# oresat-backplane-2u.net
KiCad netlist of a schematic drawn in EAGLE
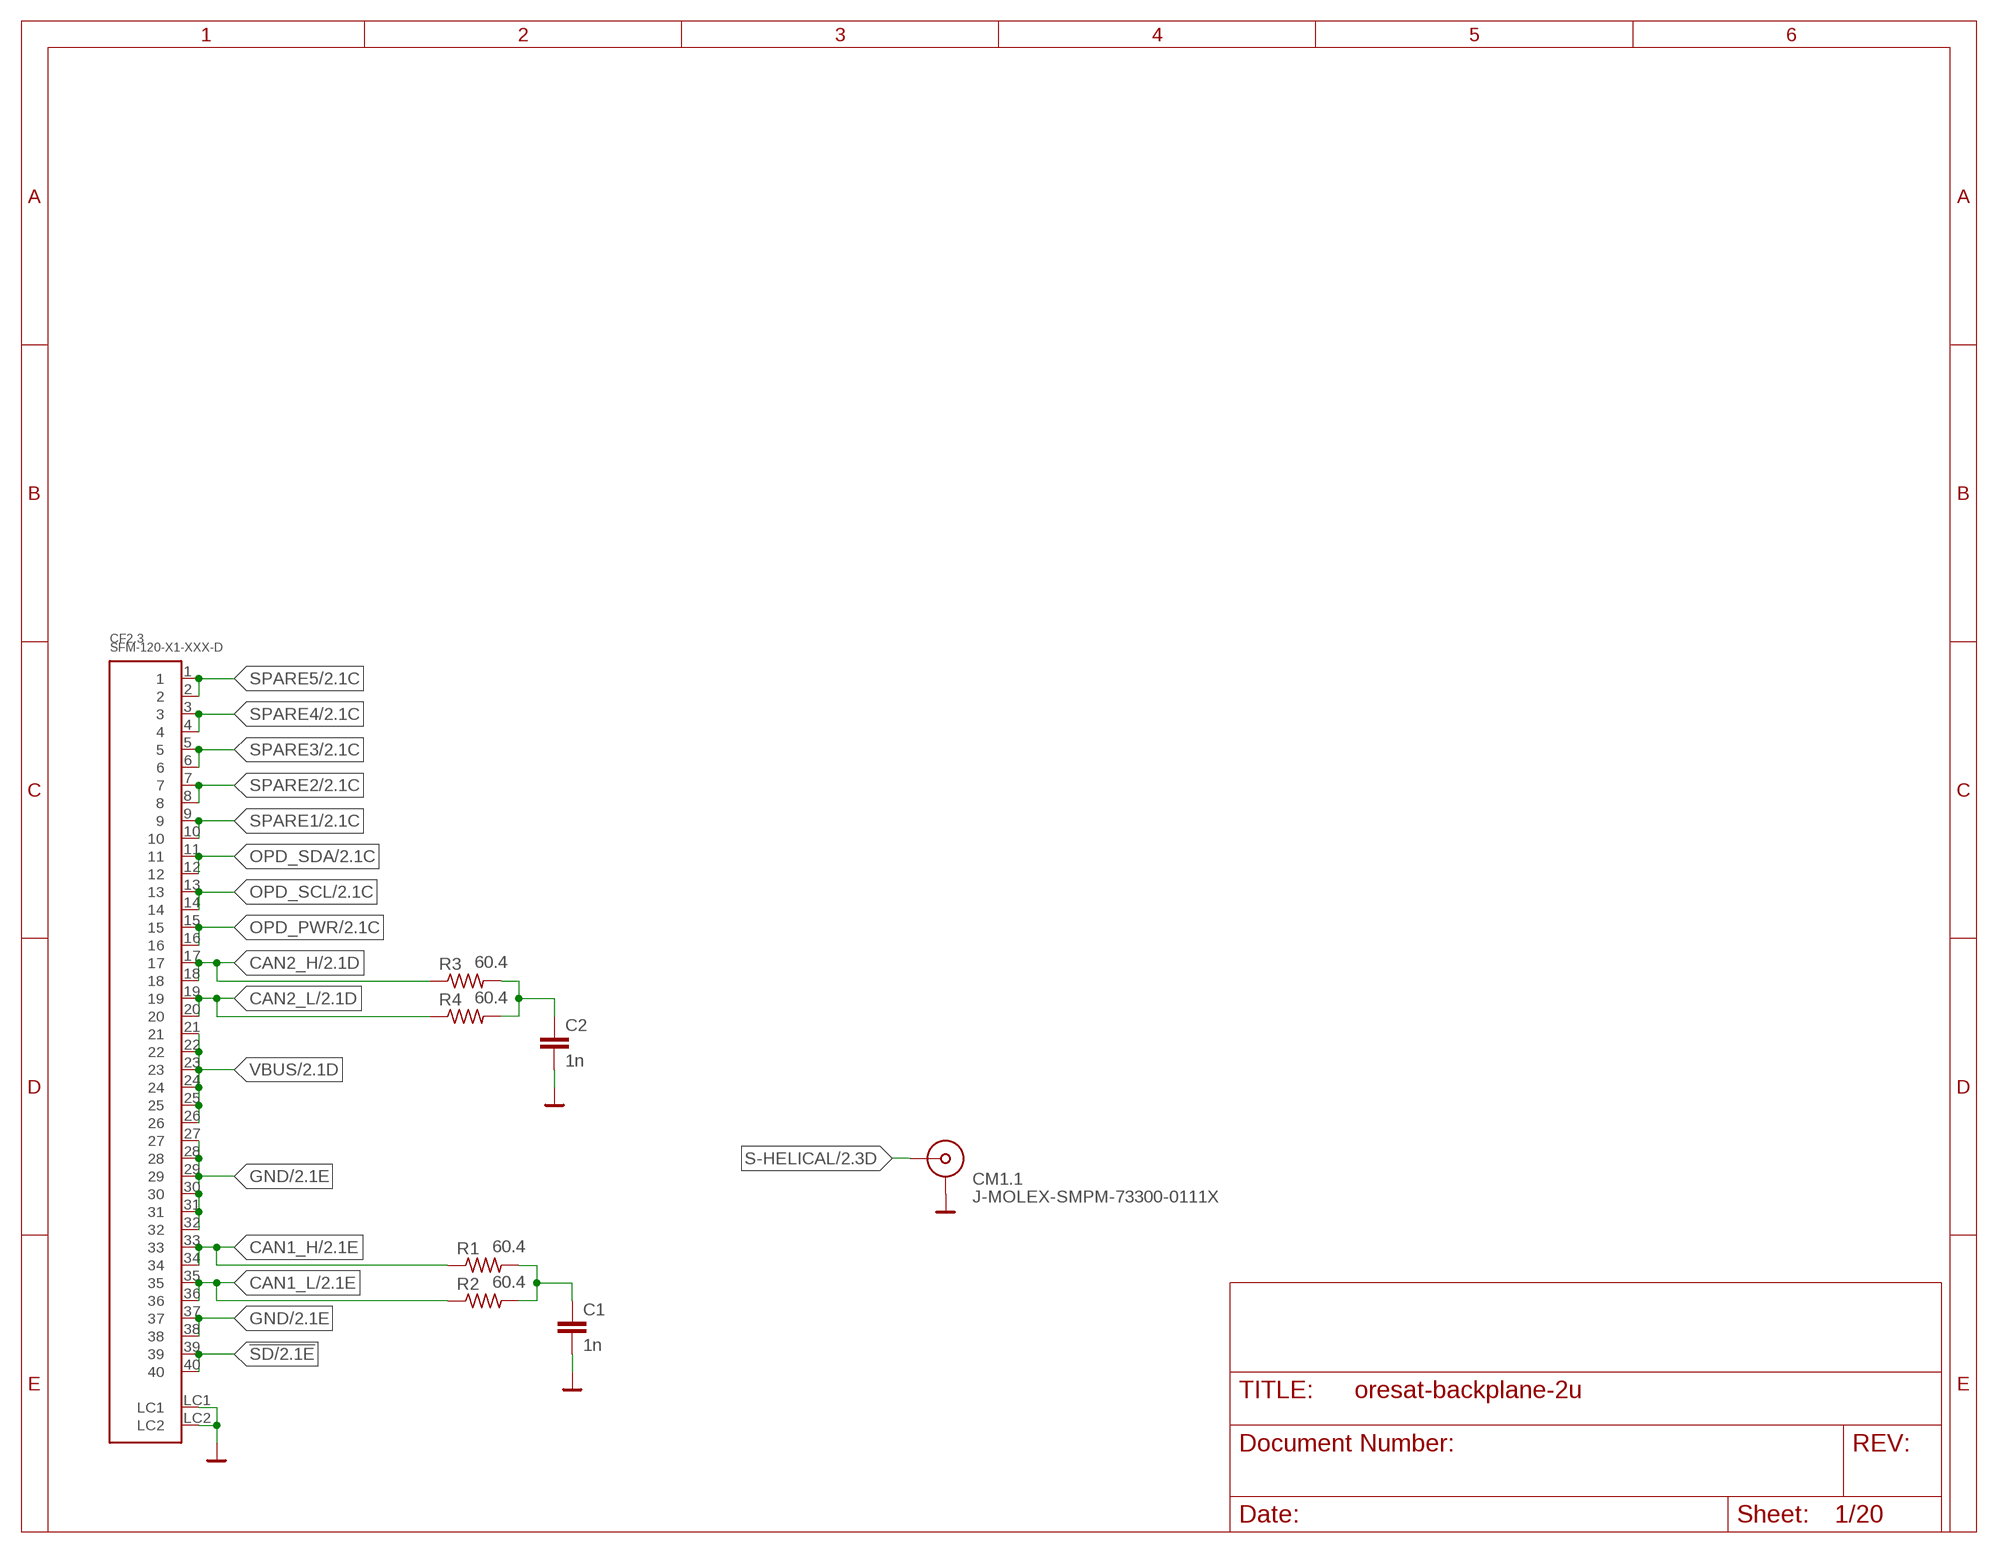
[diagram p0: schematic, sheet 1]
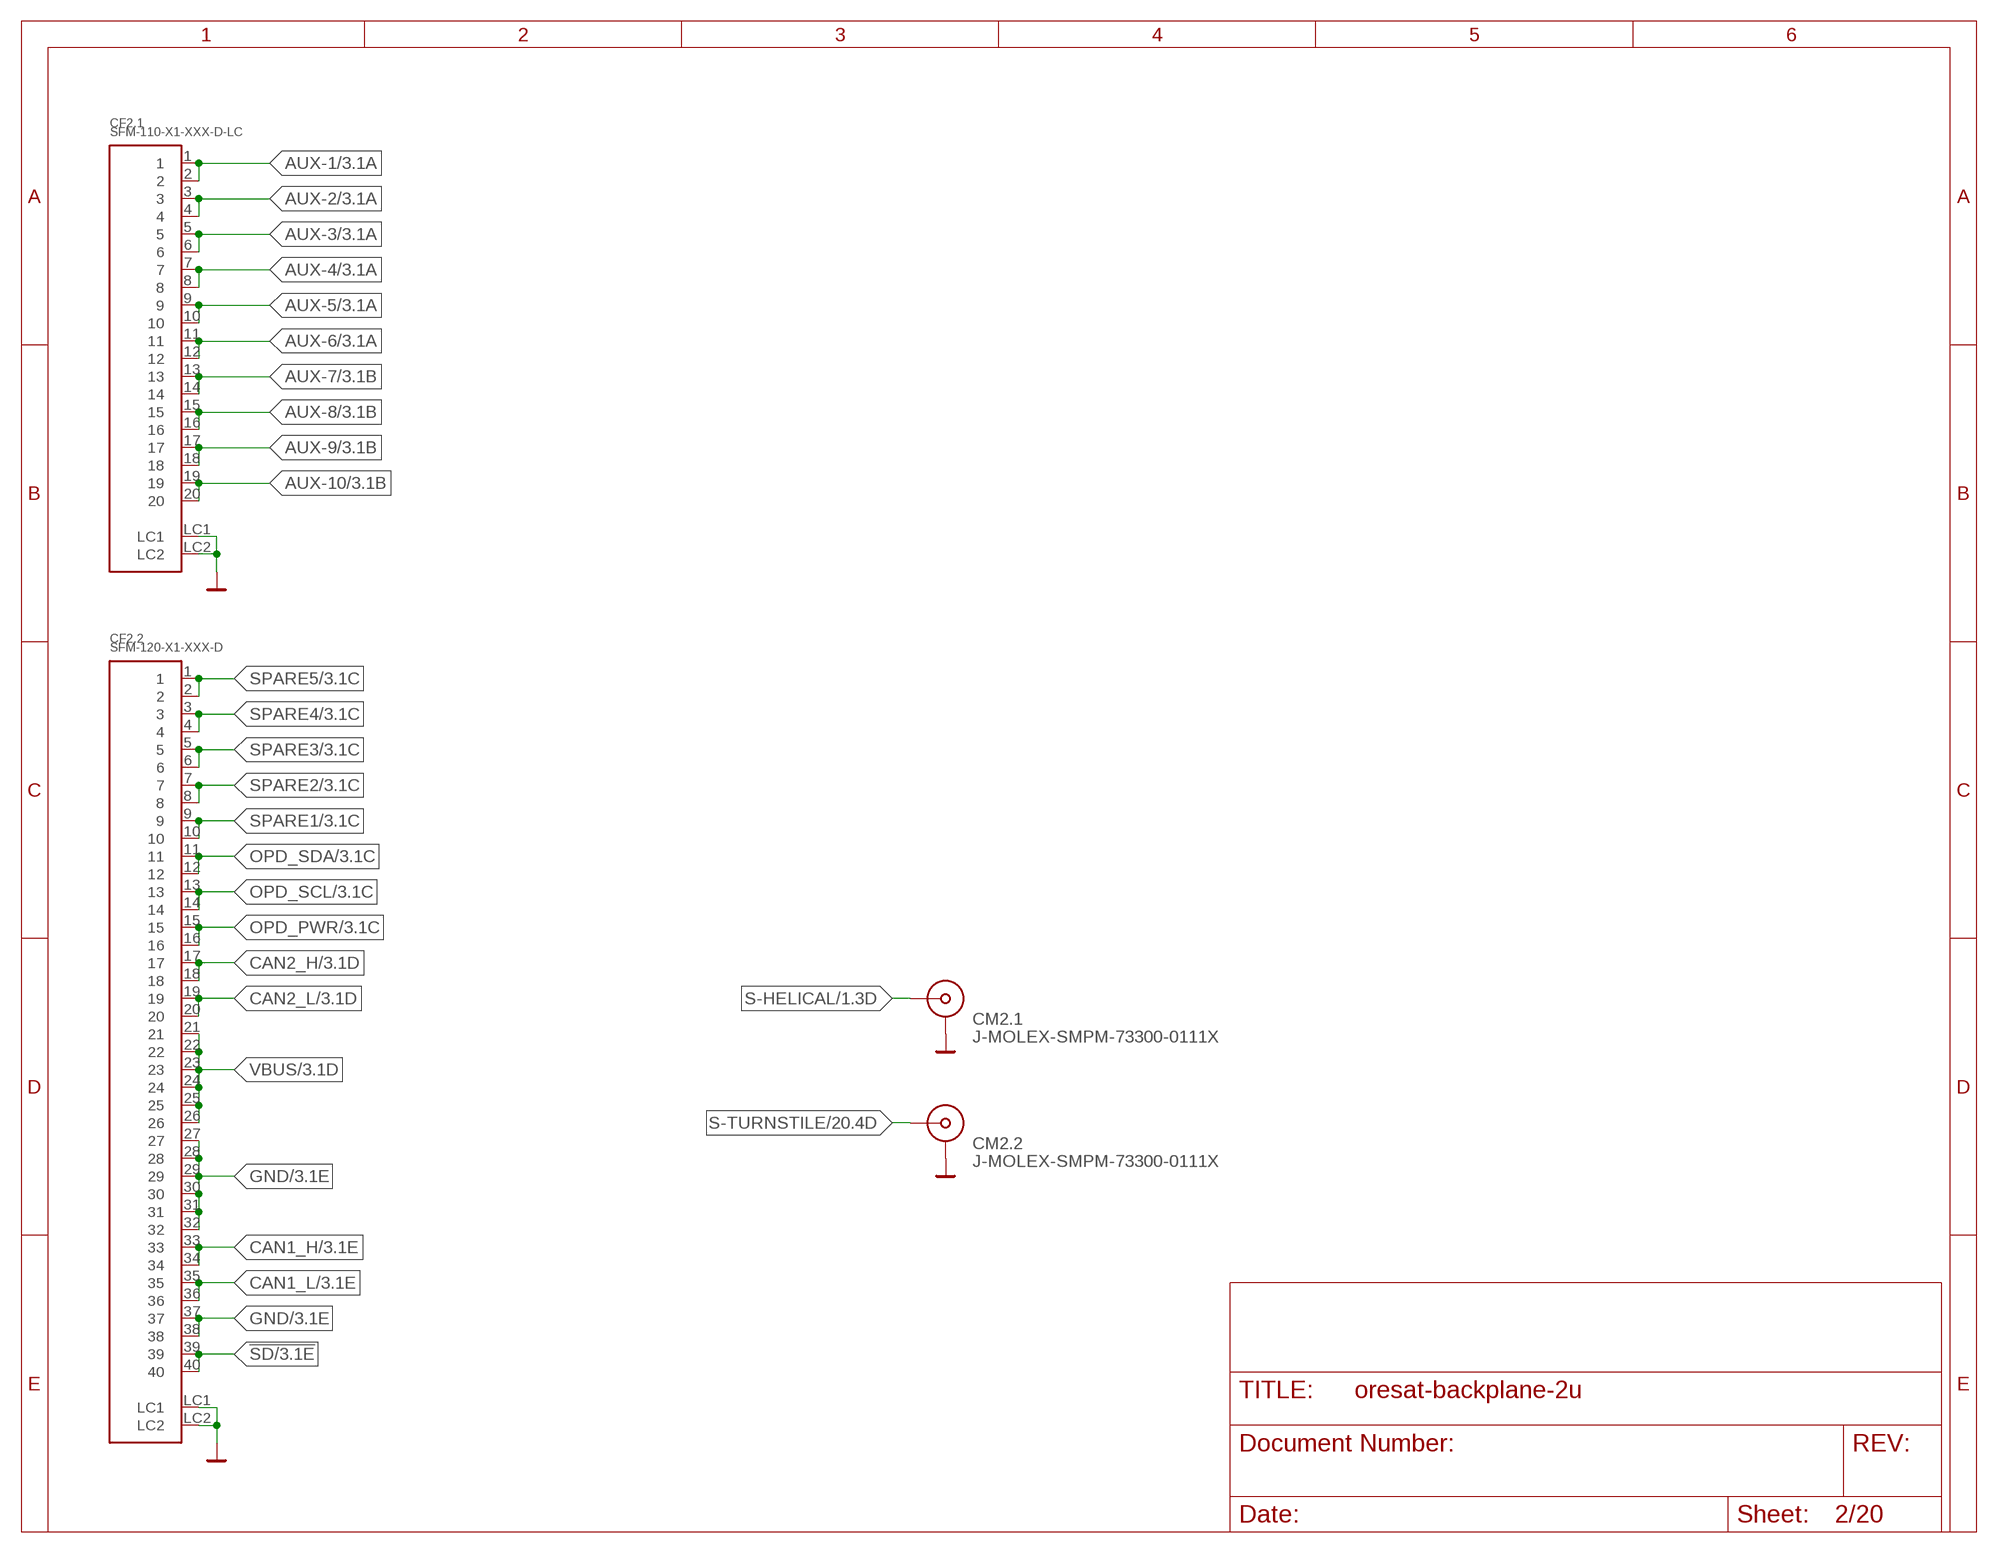
[diagram p1: schematic, sheet 2]
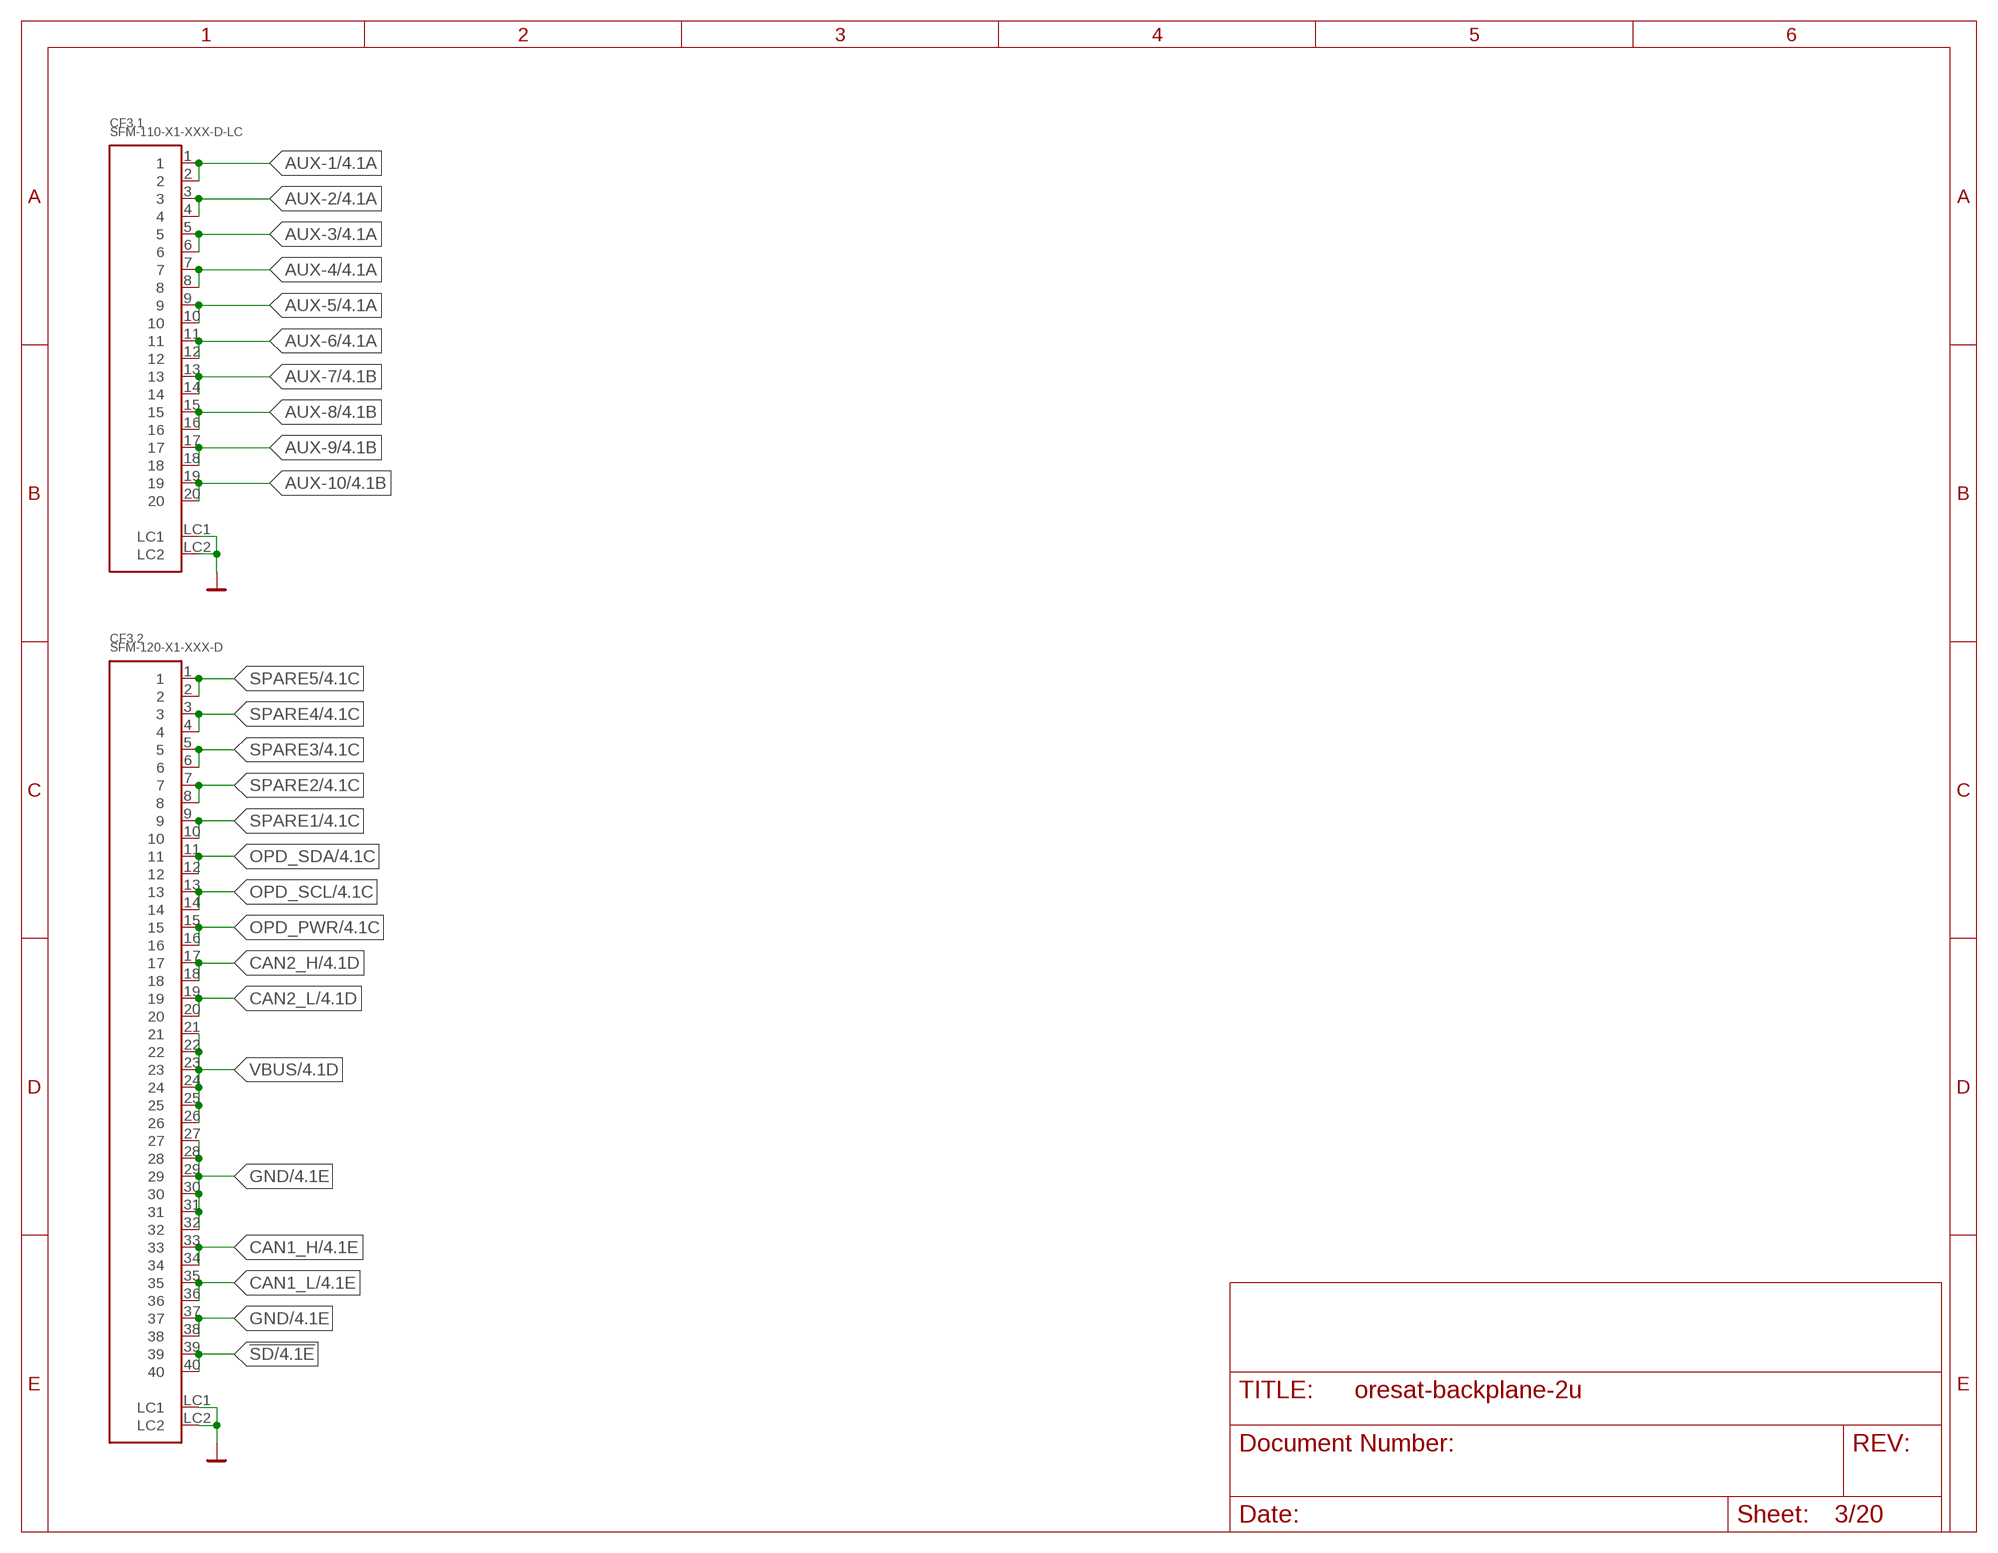
[diagram p2: schematic, sheet 3]
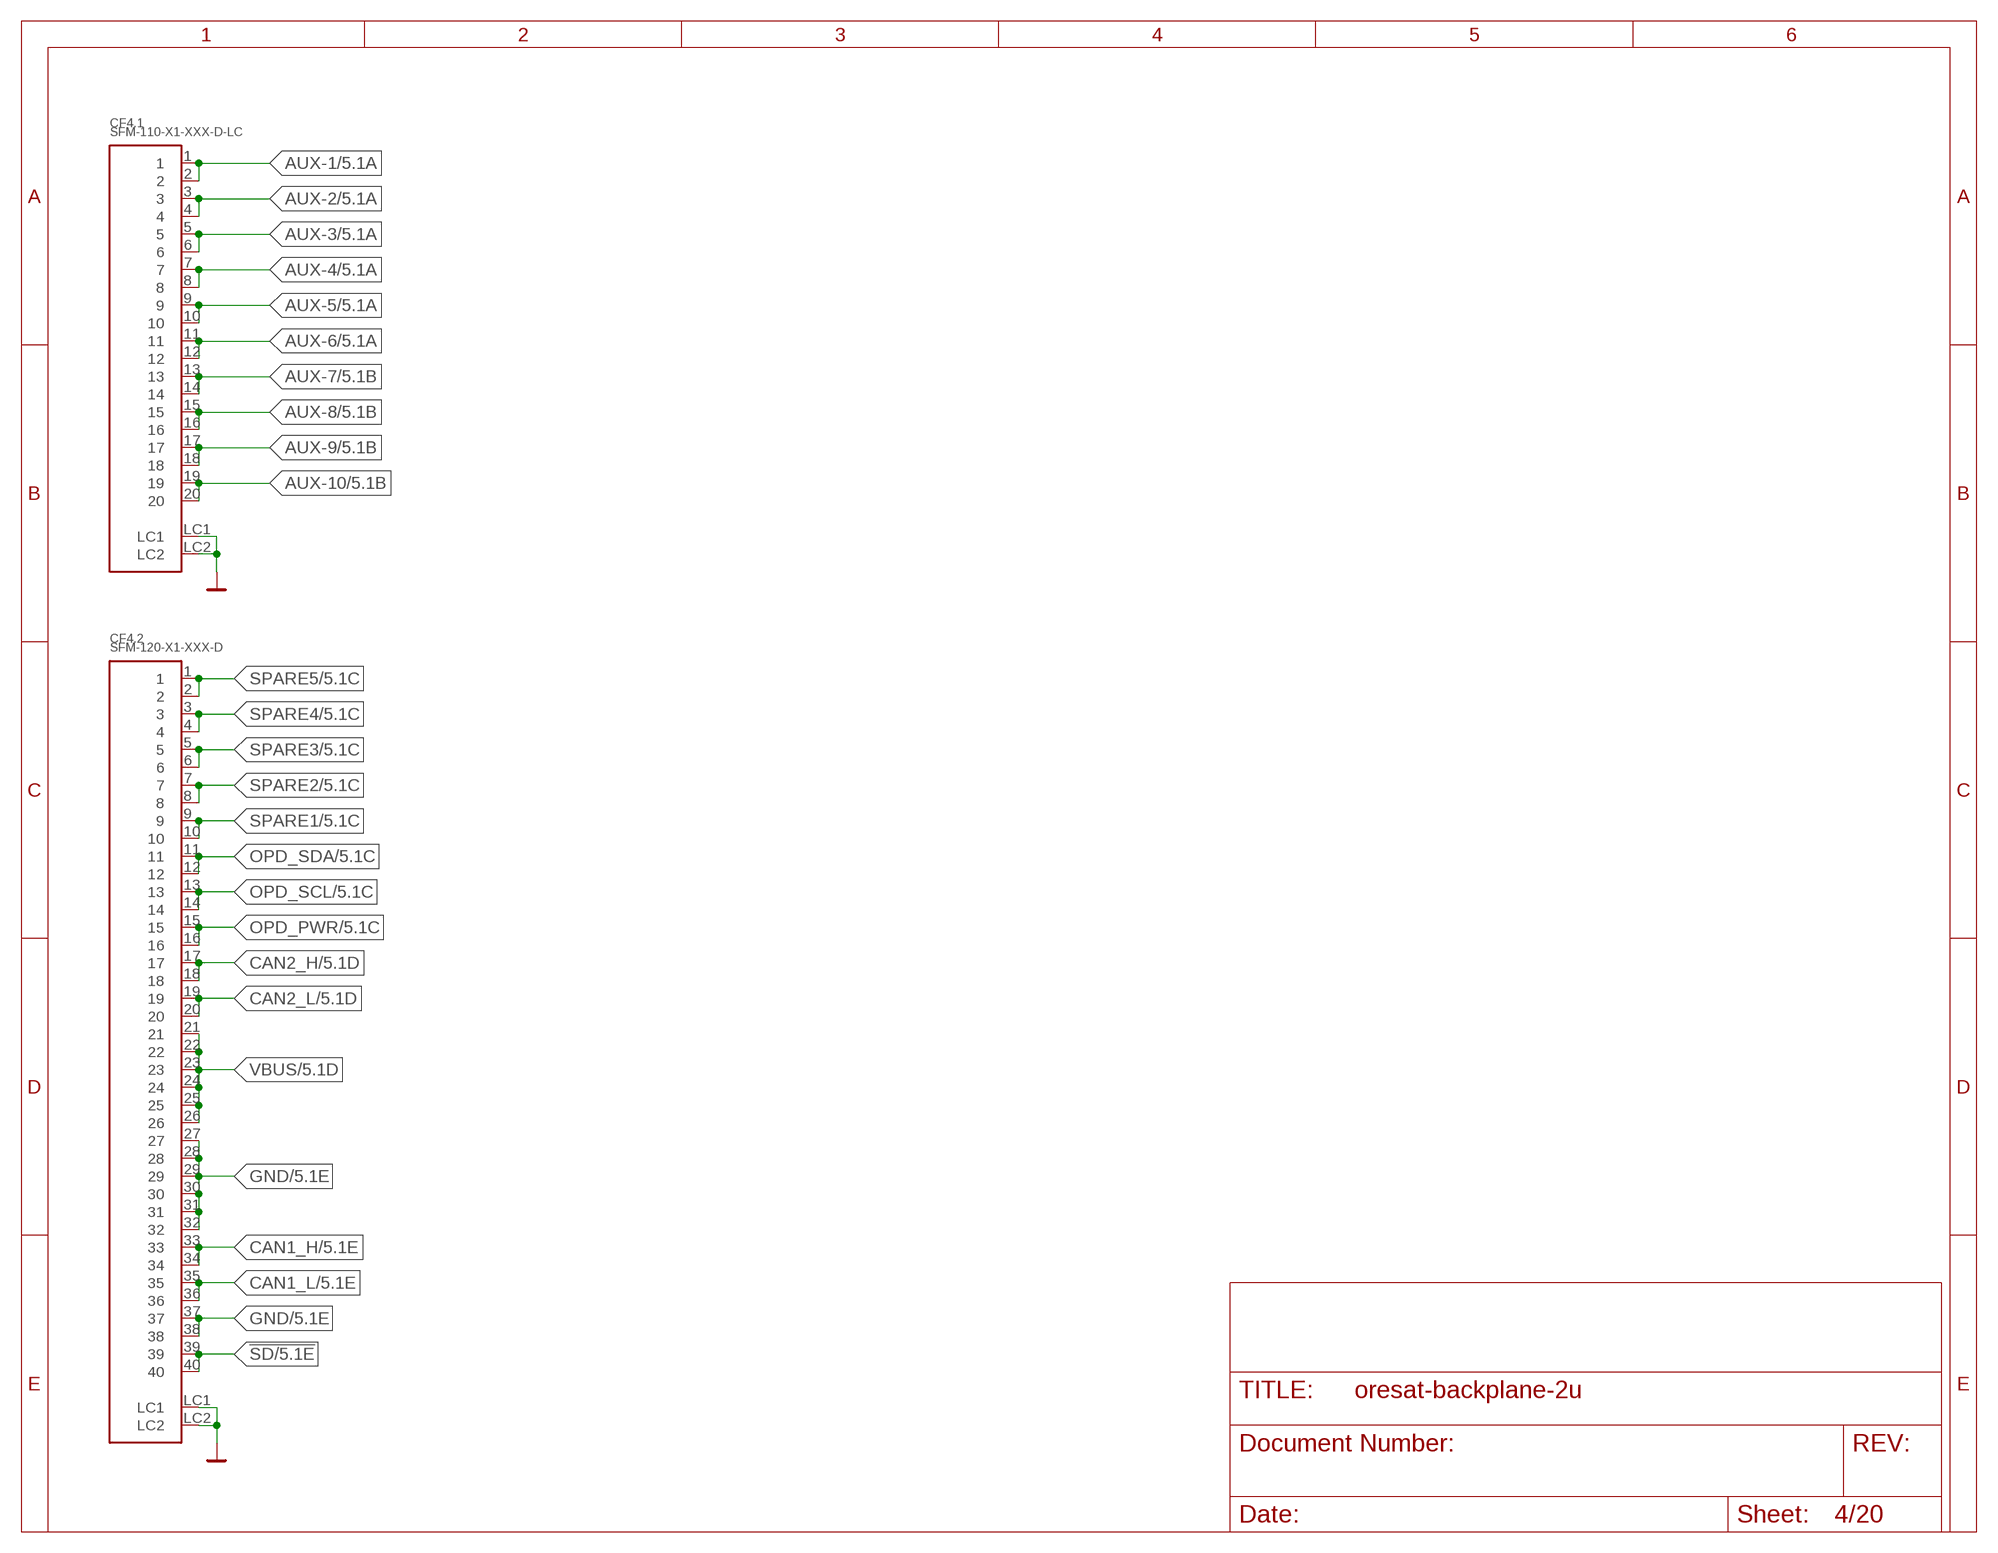
[diagram p3: schematic, sheet 4]
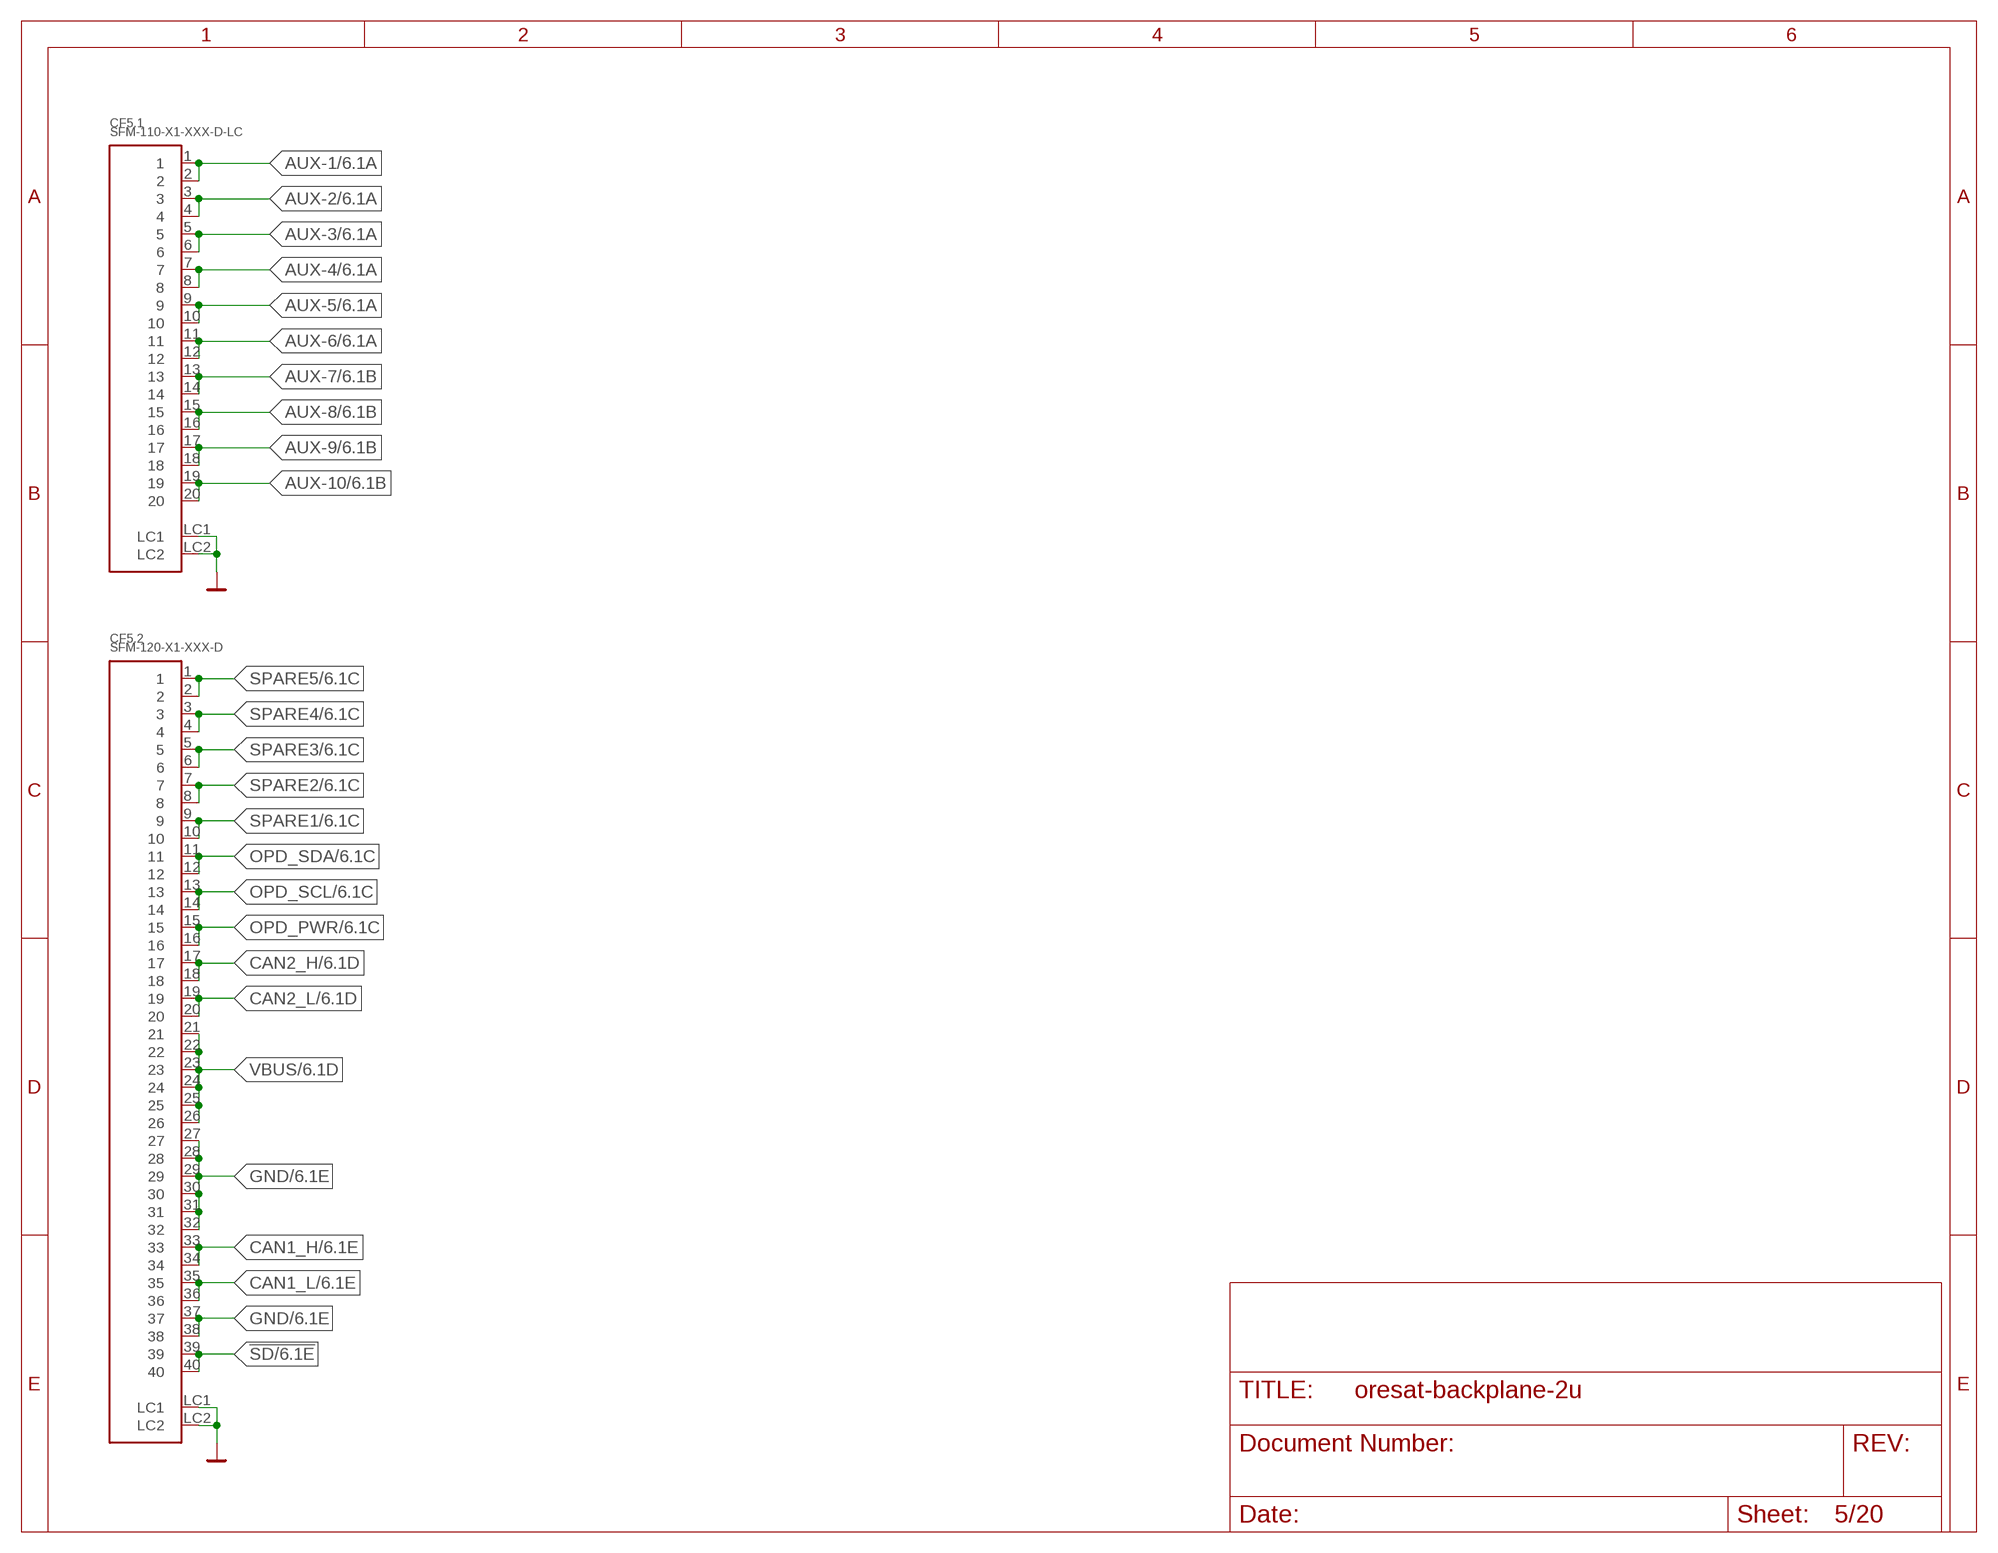
[diagram p4: schematic, sheet 5]
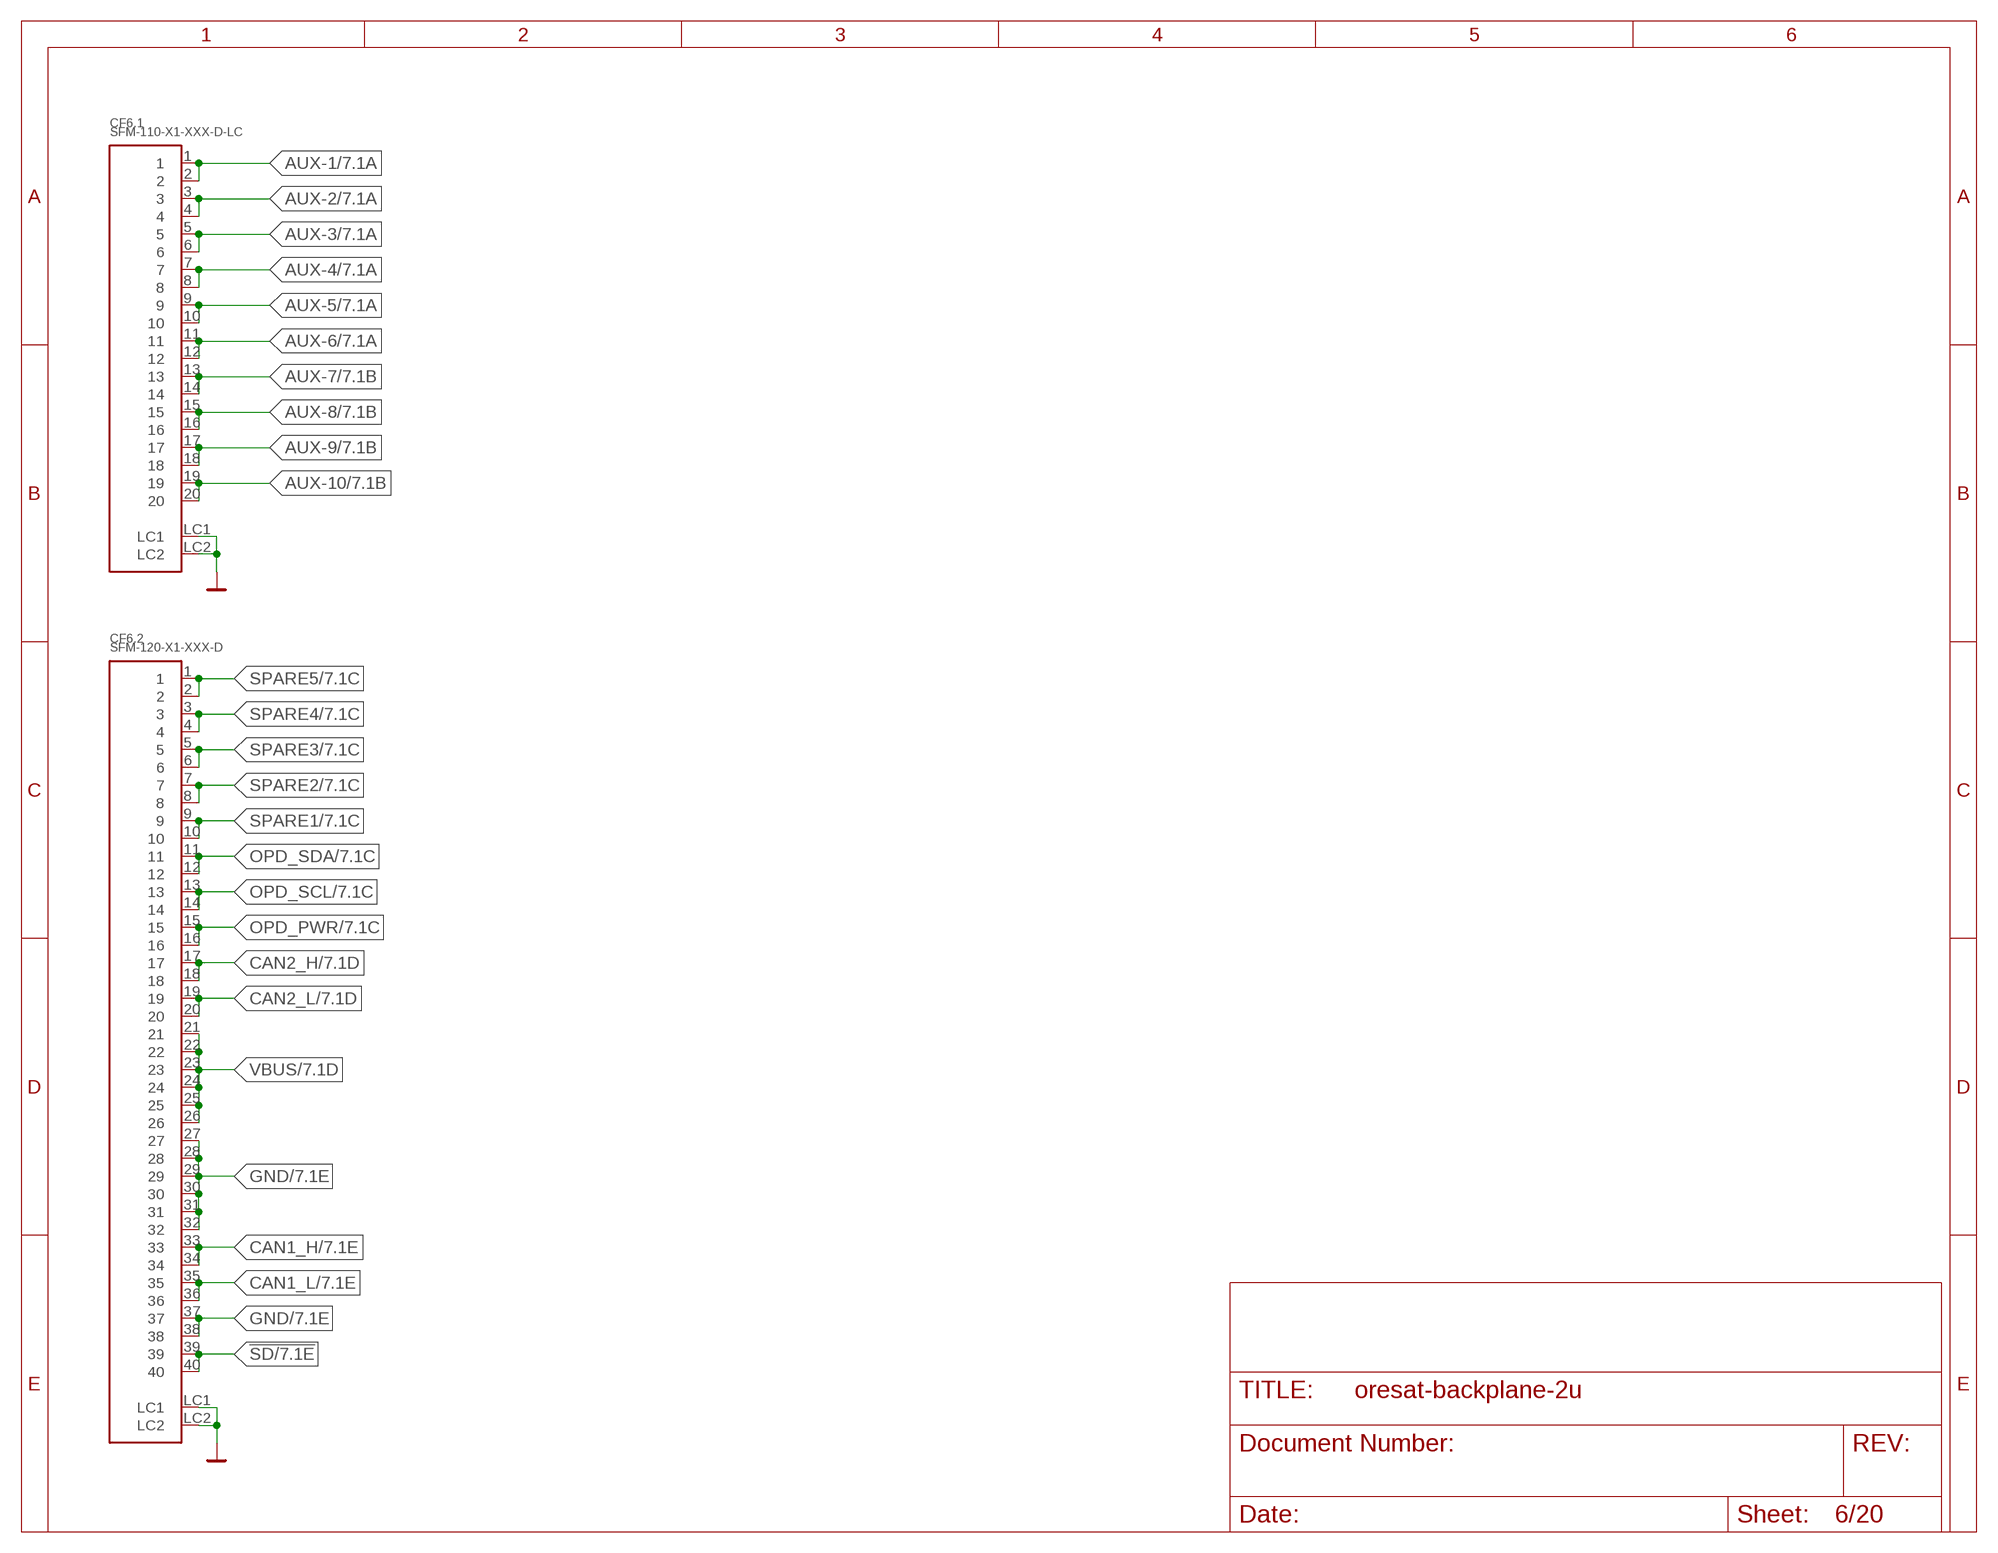
[diagram p5: schematic, sheet 6]
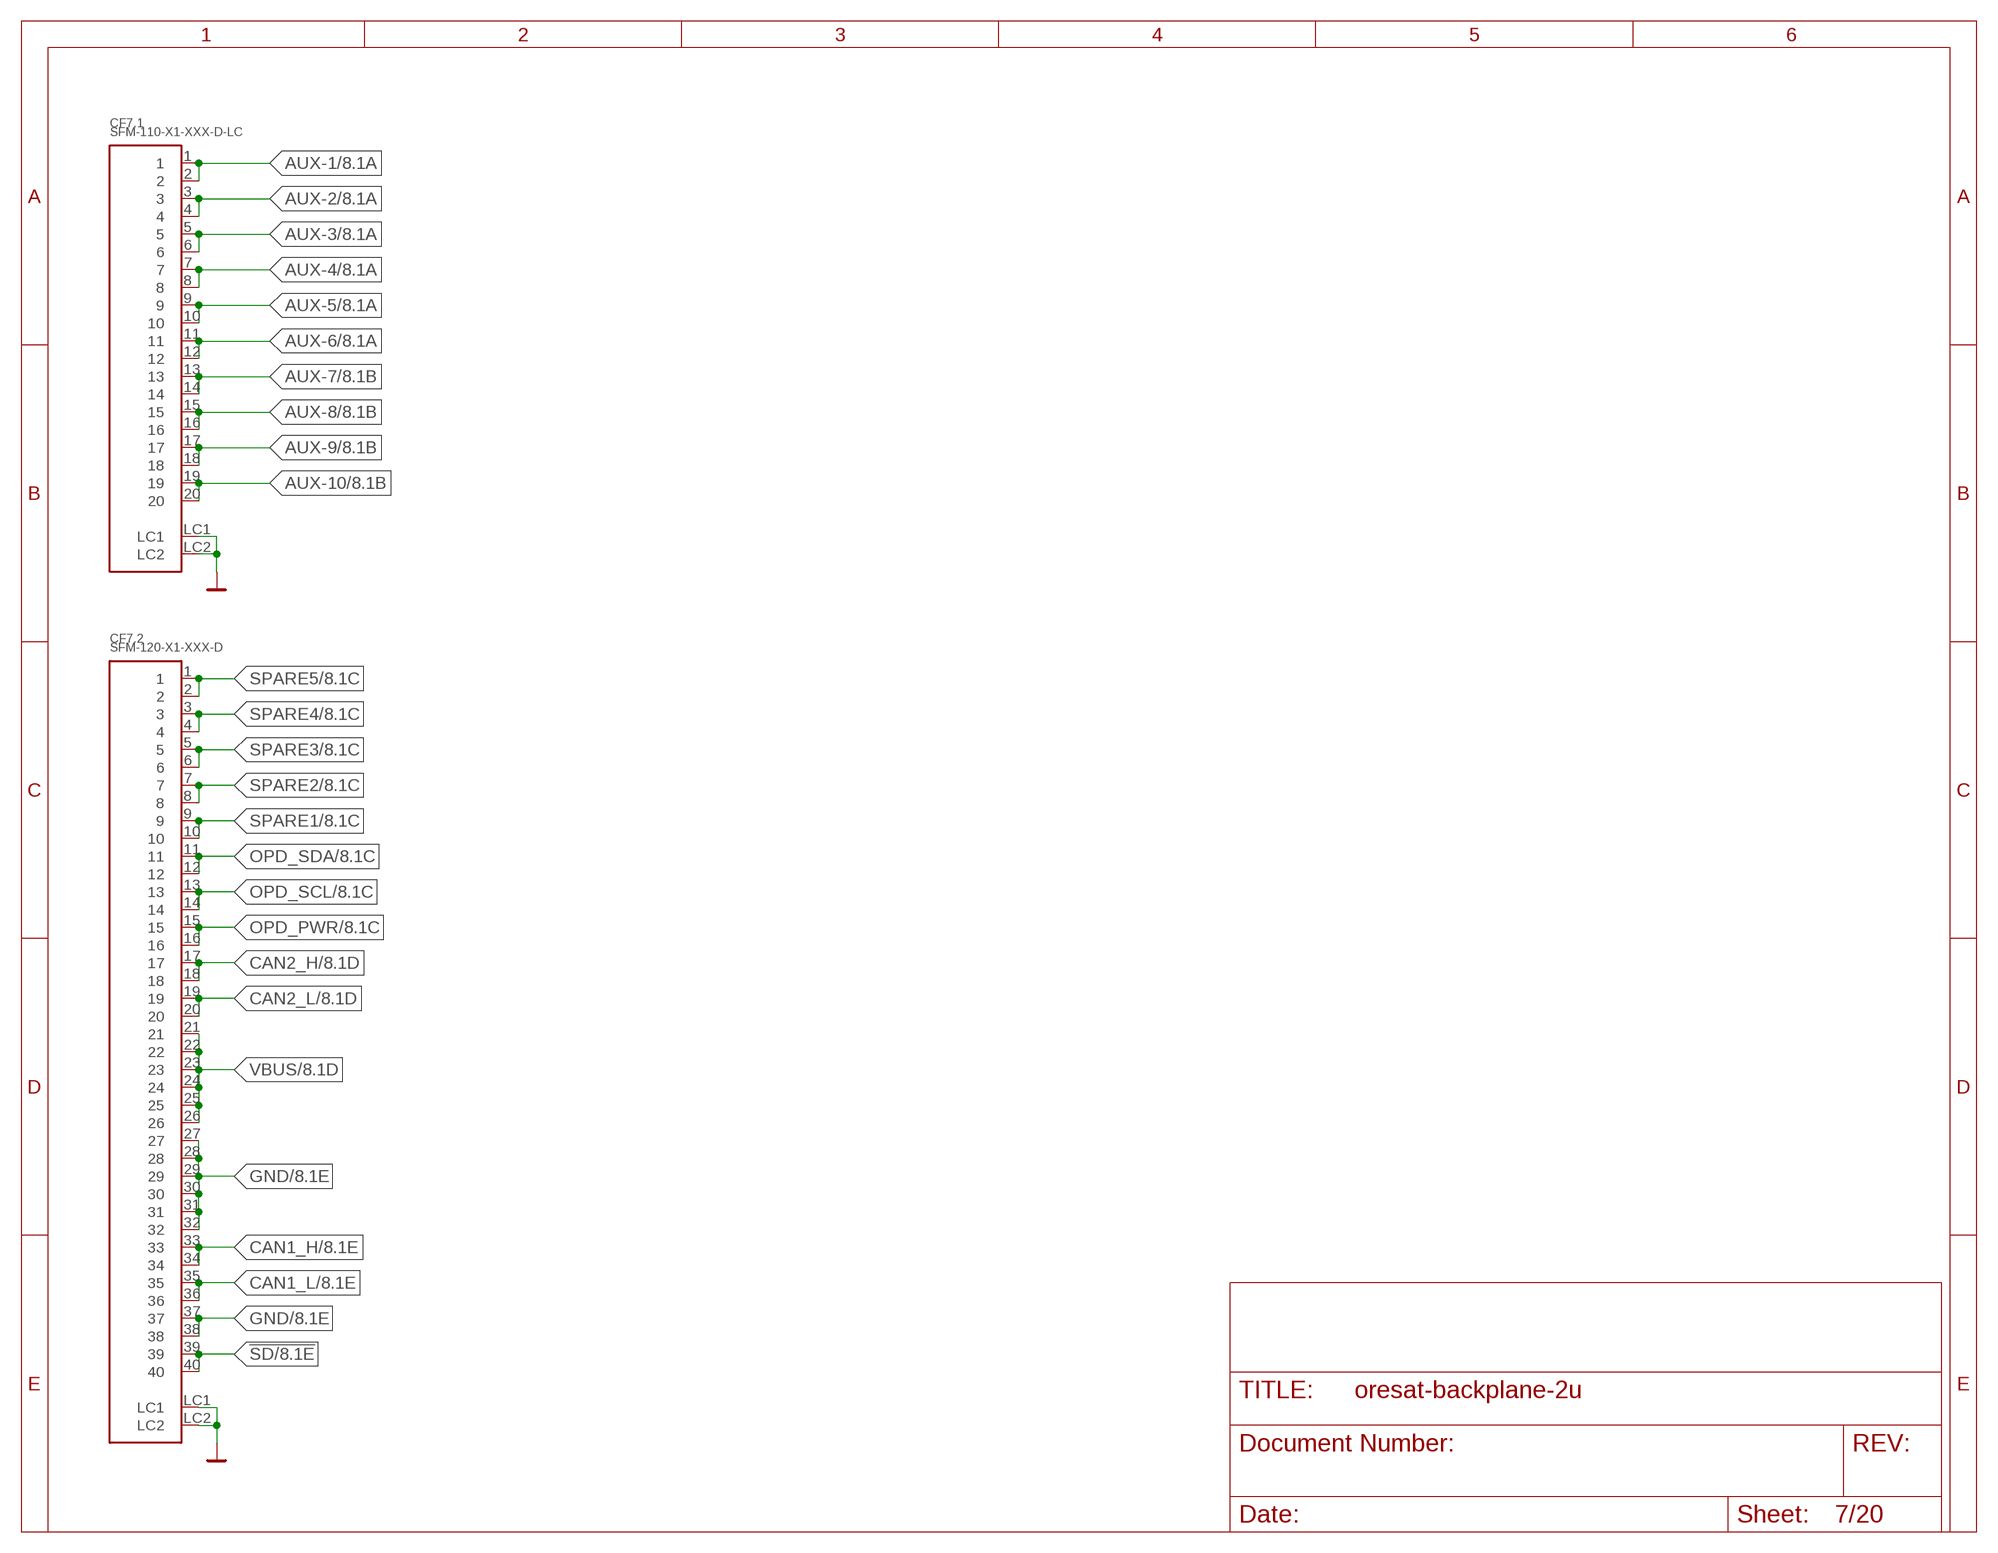
[diagram p6: schematic, sheet 7]
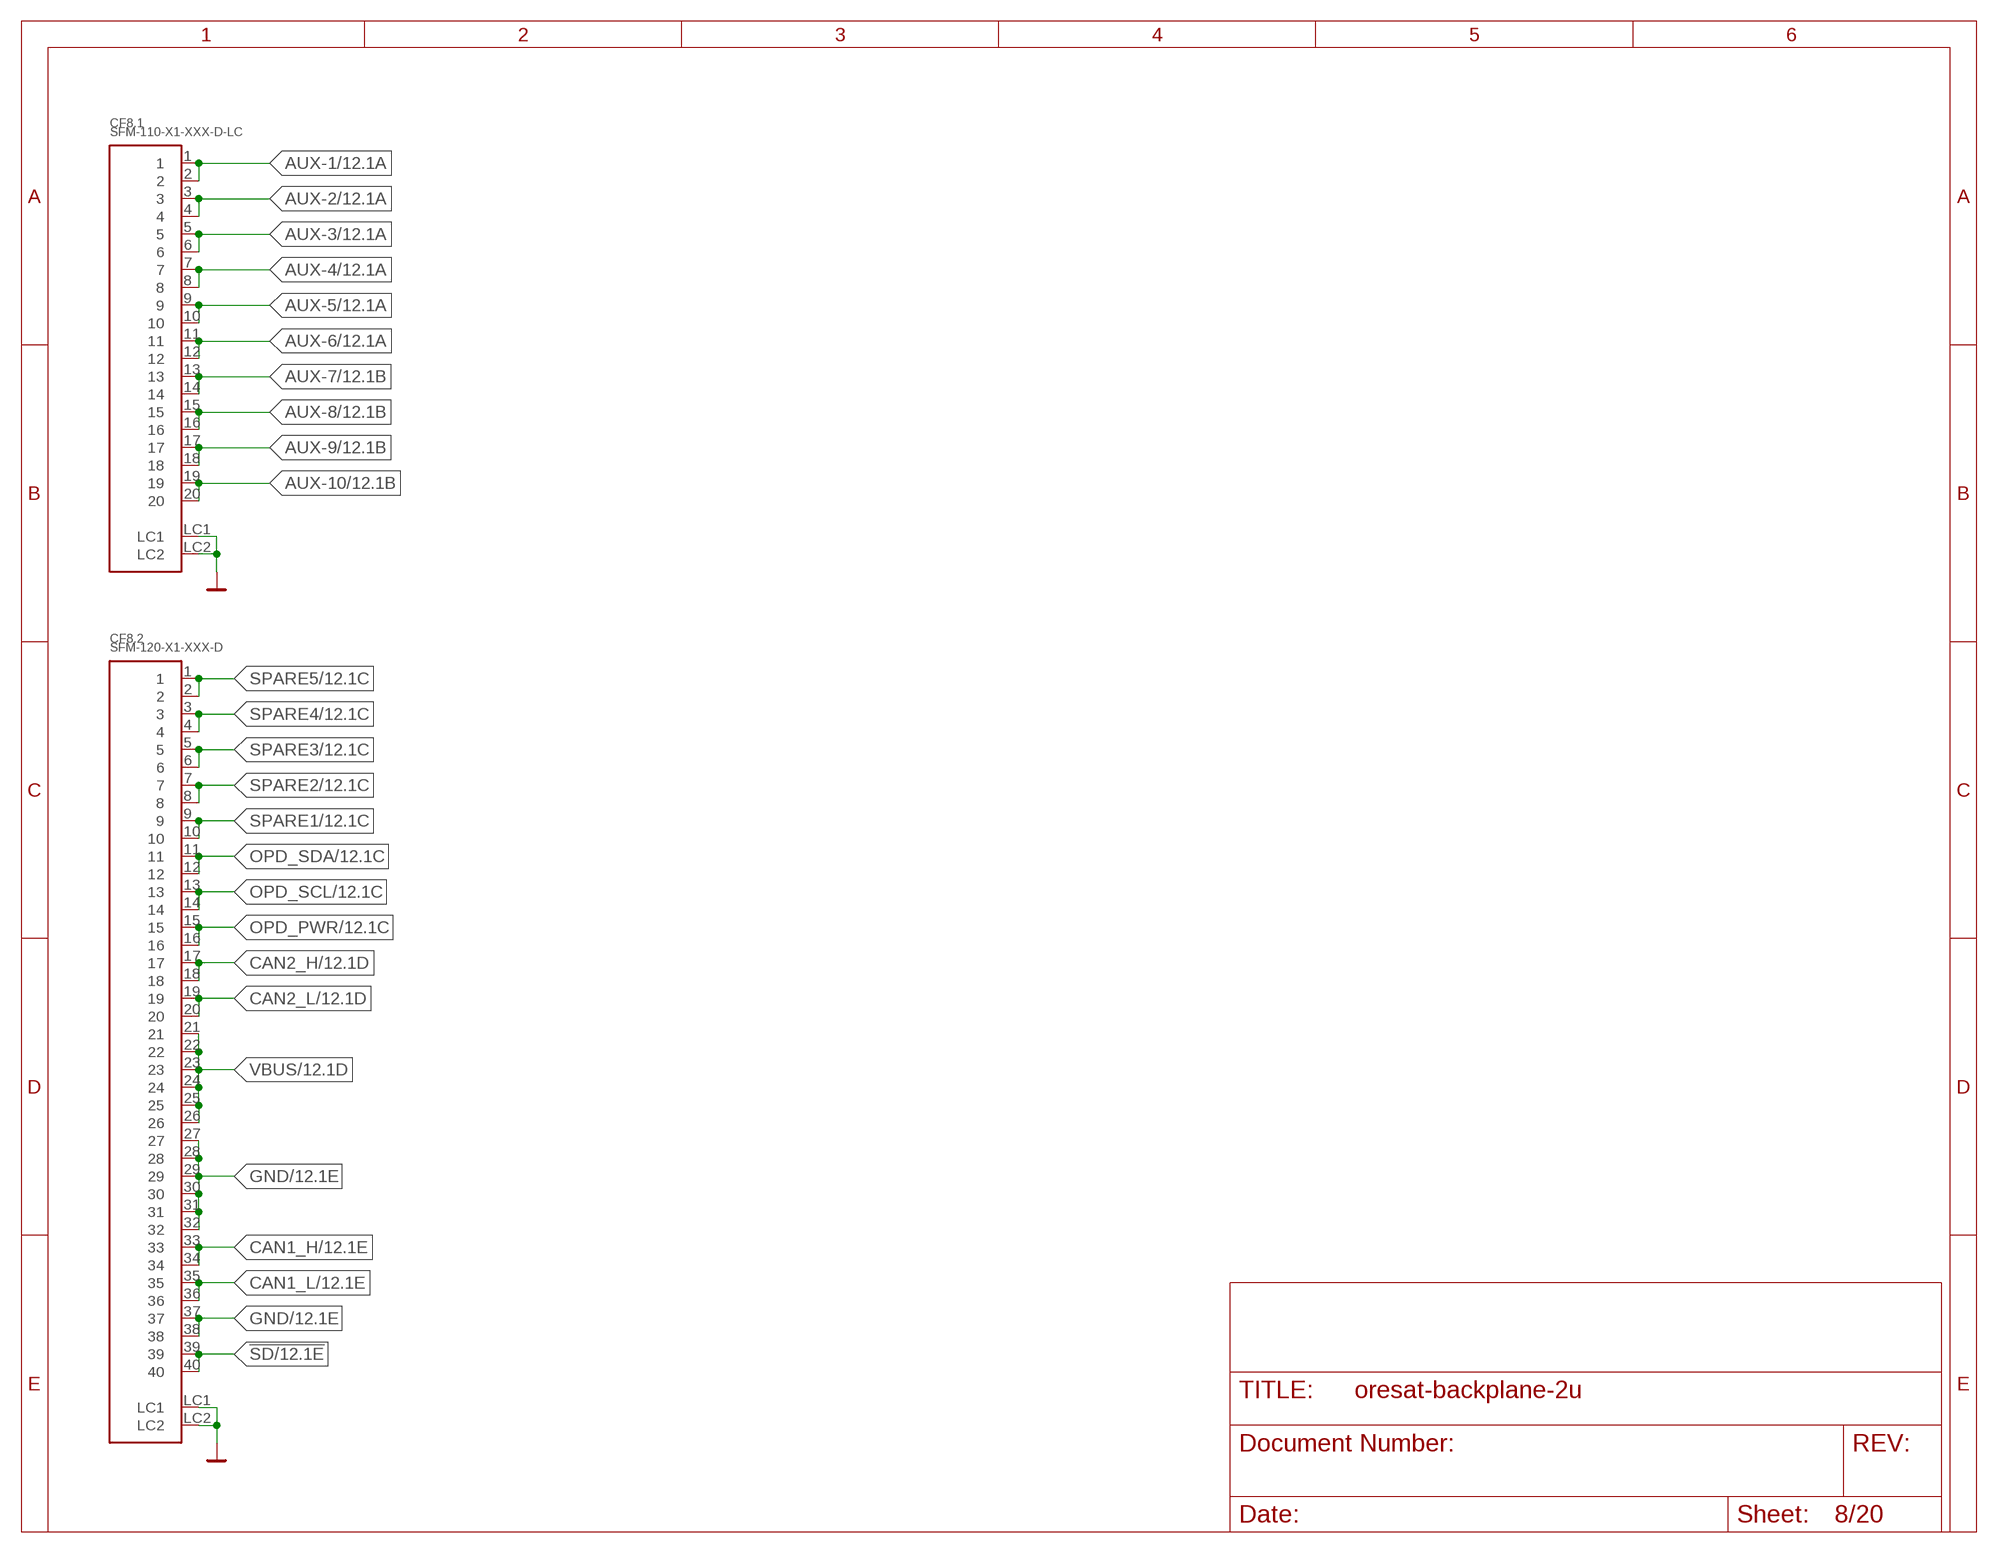
[diagram p7: schematic, sheet 8]
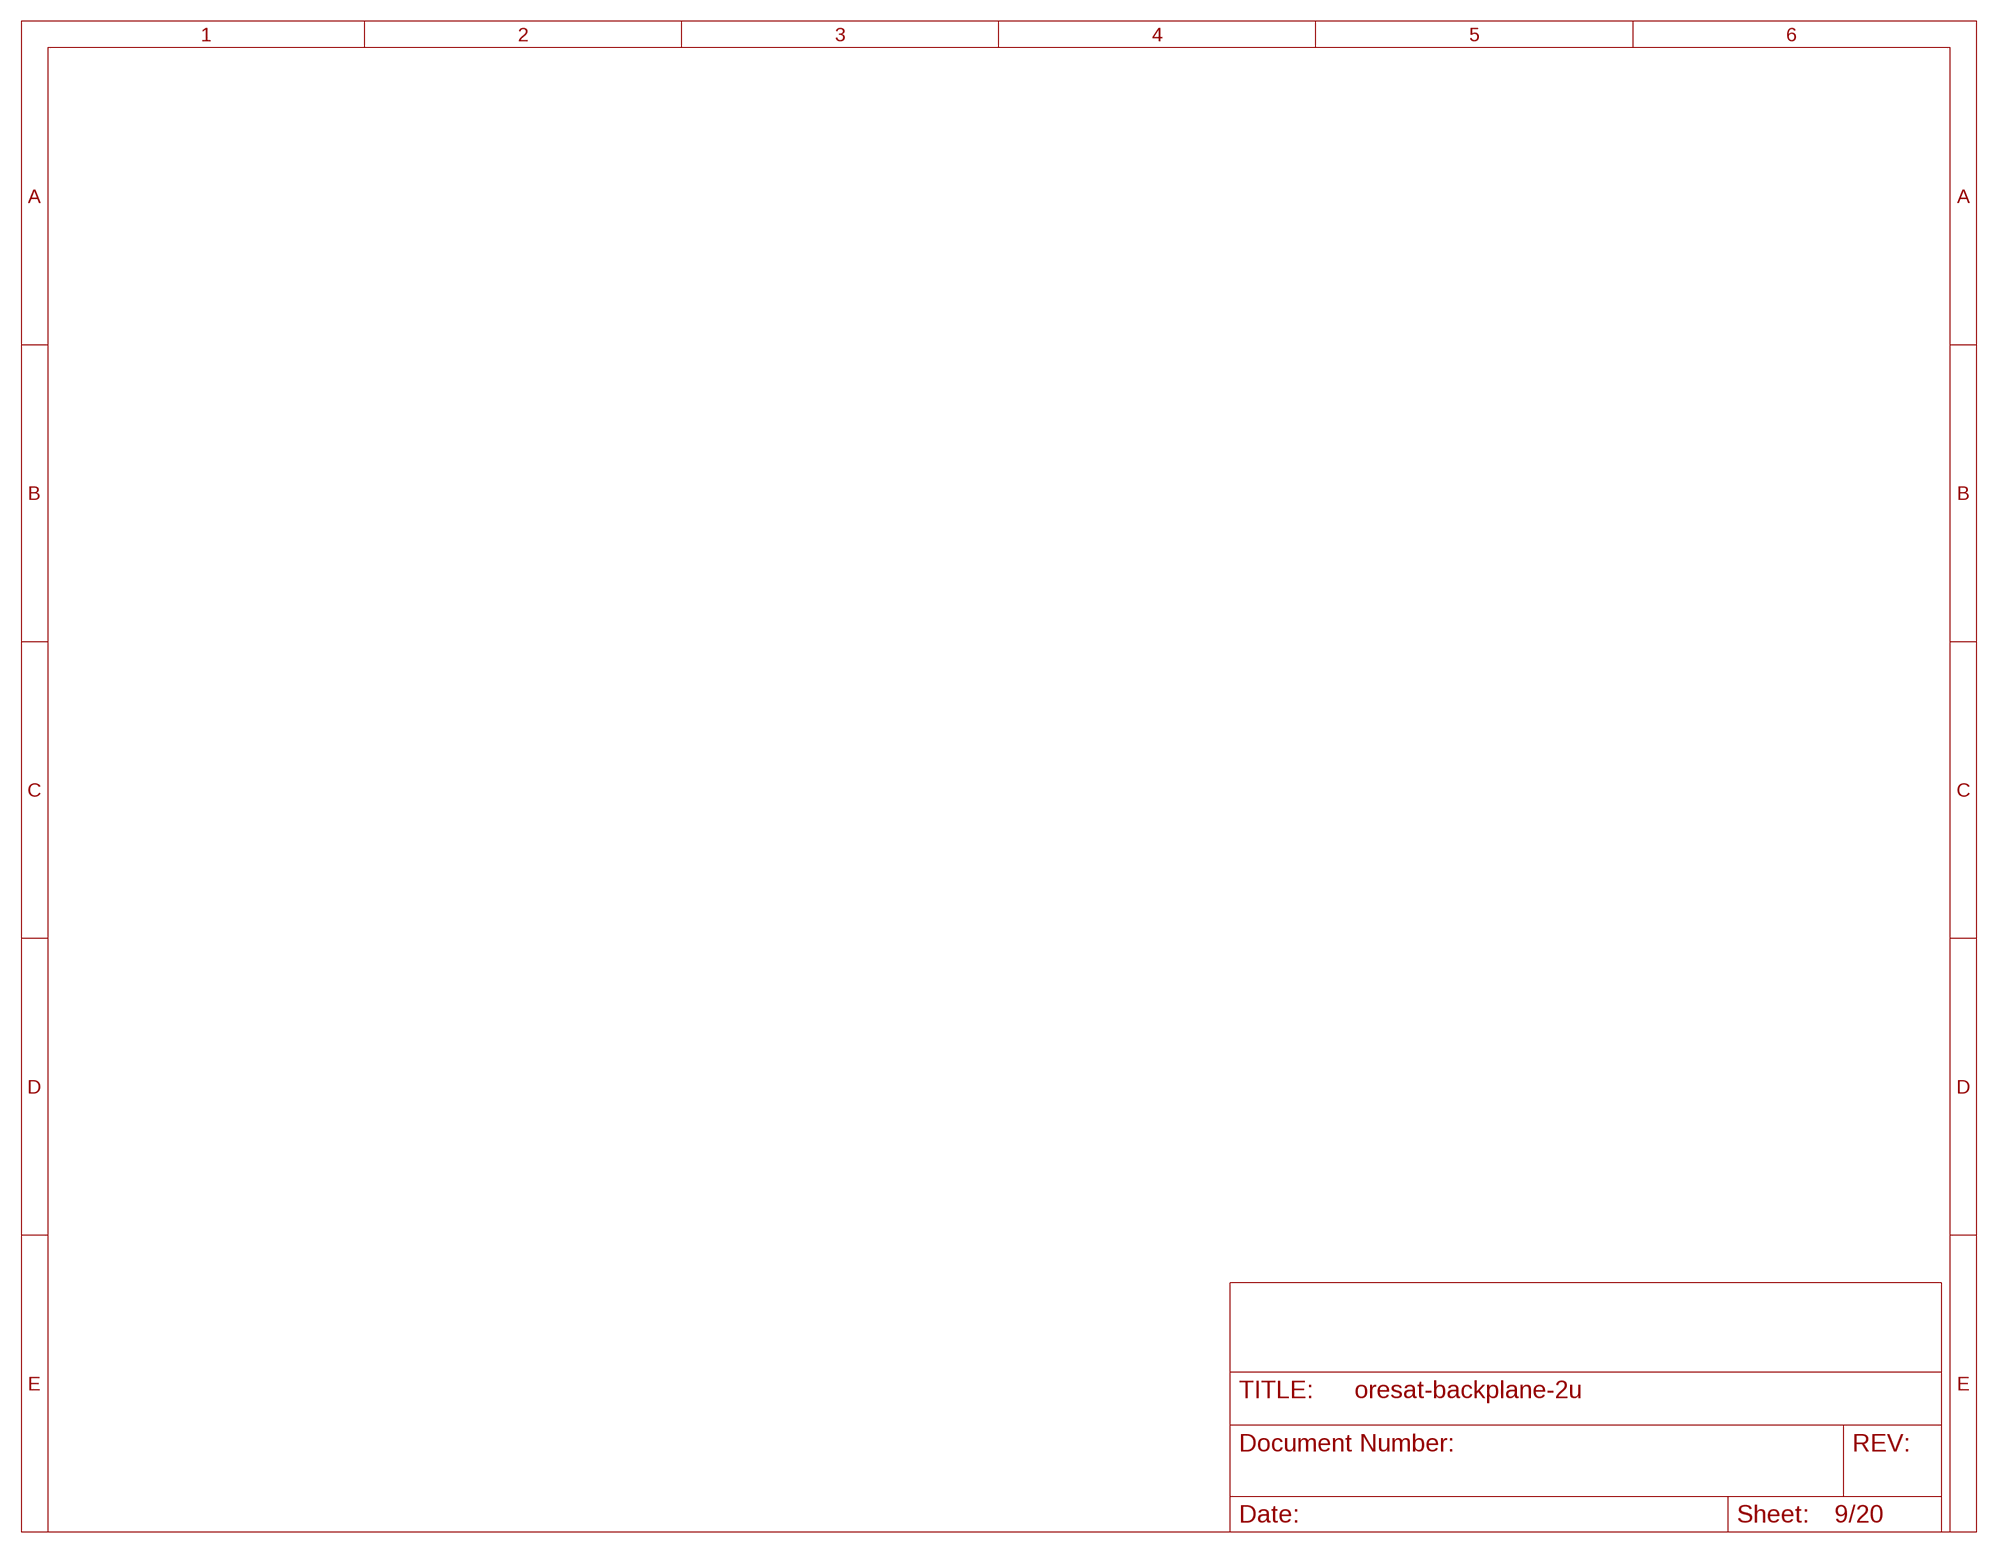
[diagram p8: schematic, sheet 9]
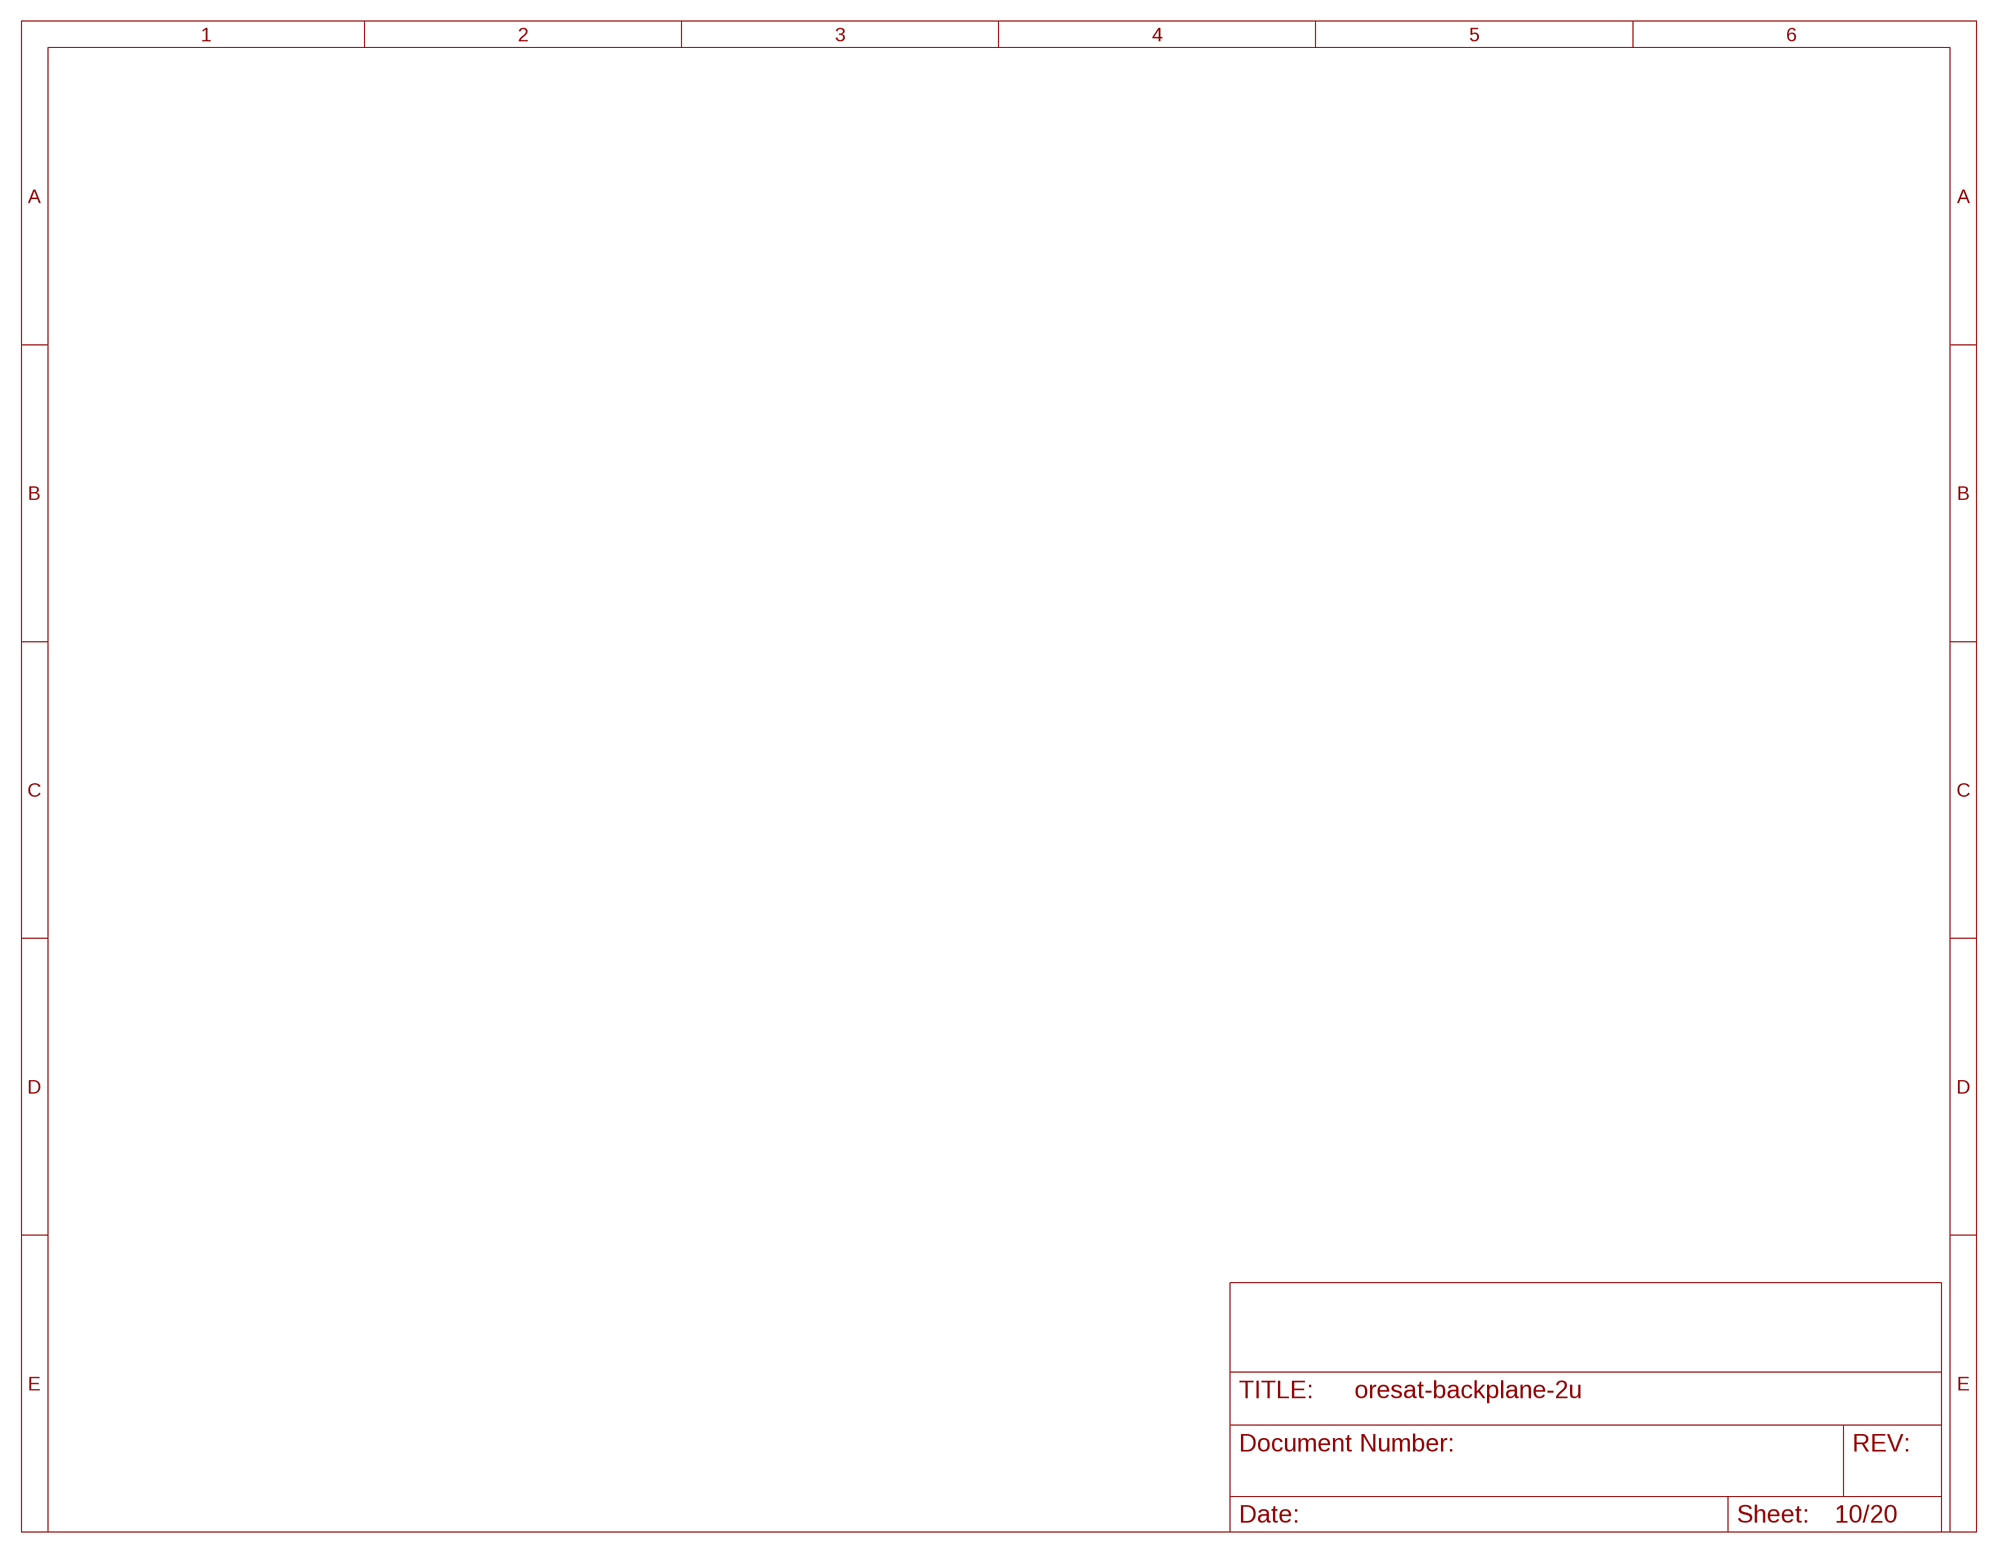
[diagram p9: schematic, sheet 10]
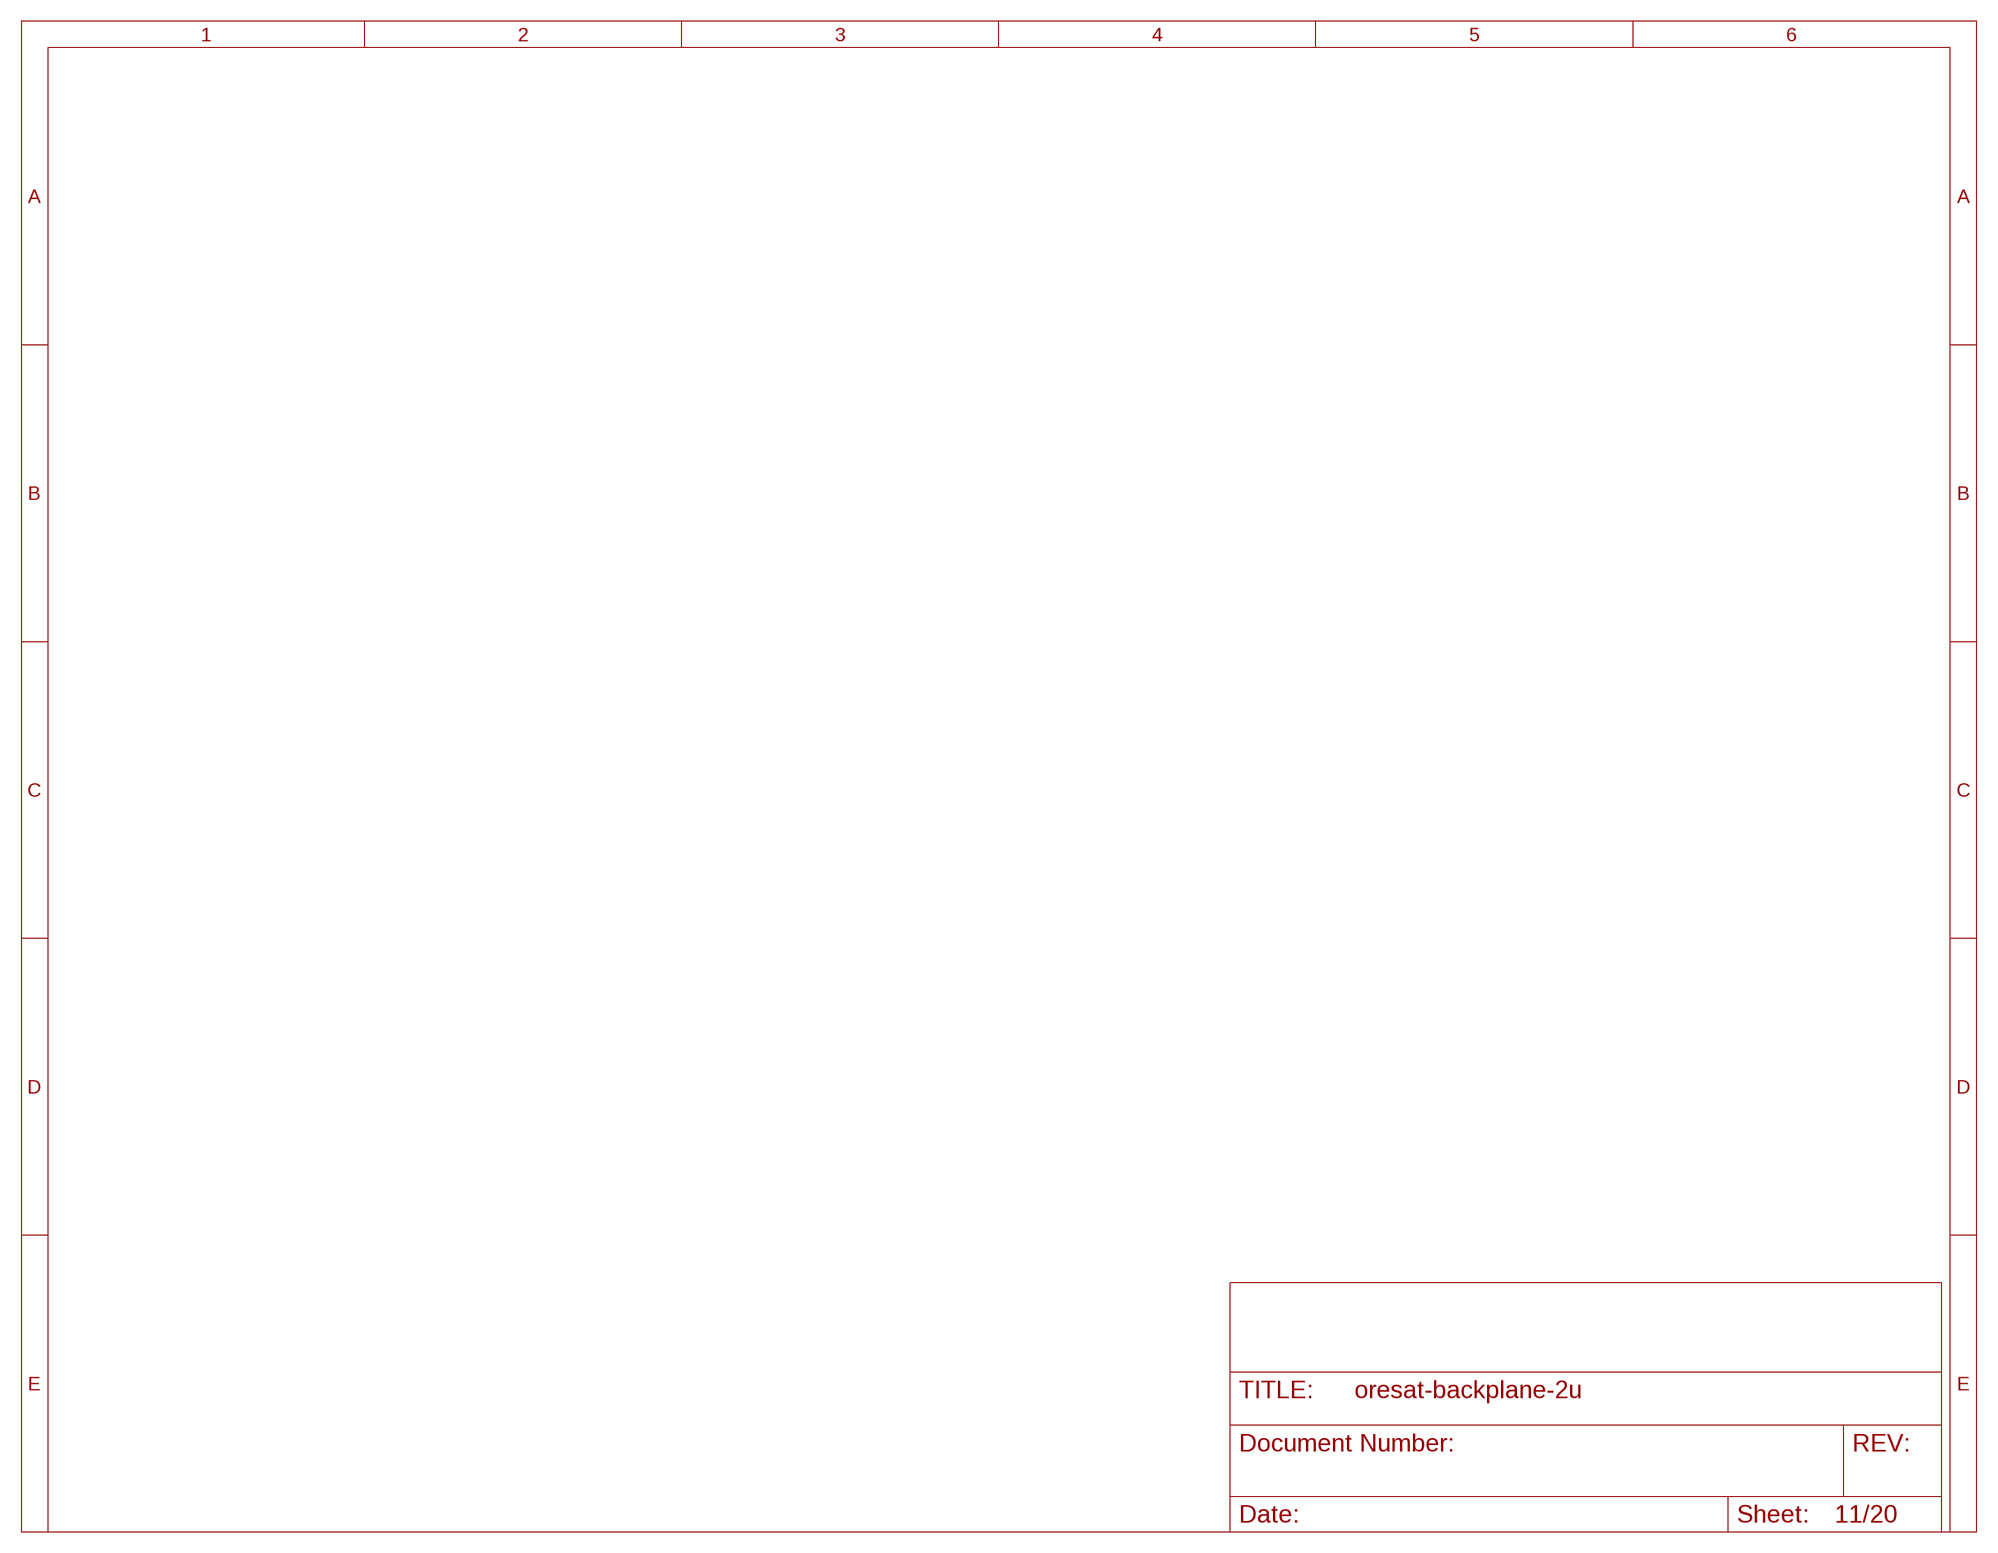
[diagram p10: schematic, sheet 11]
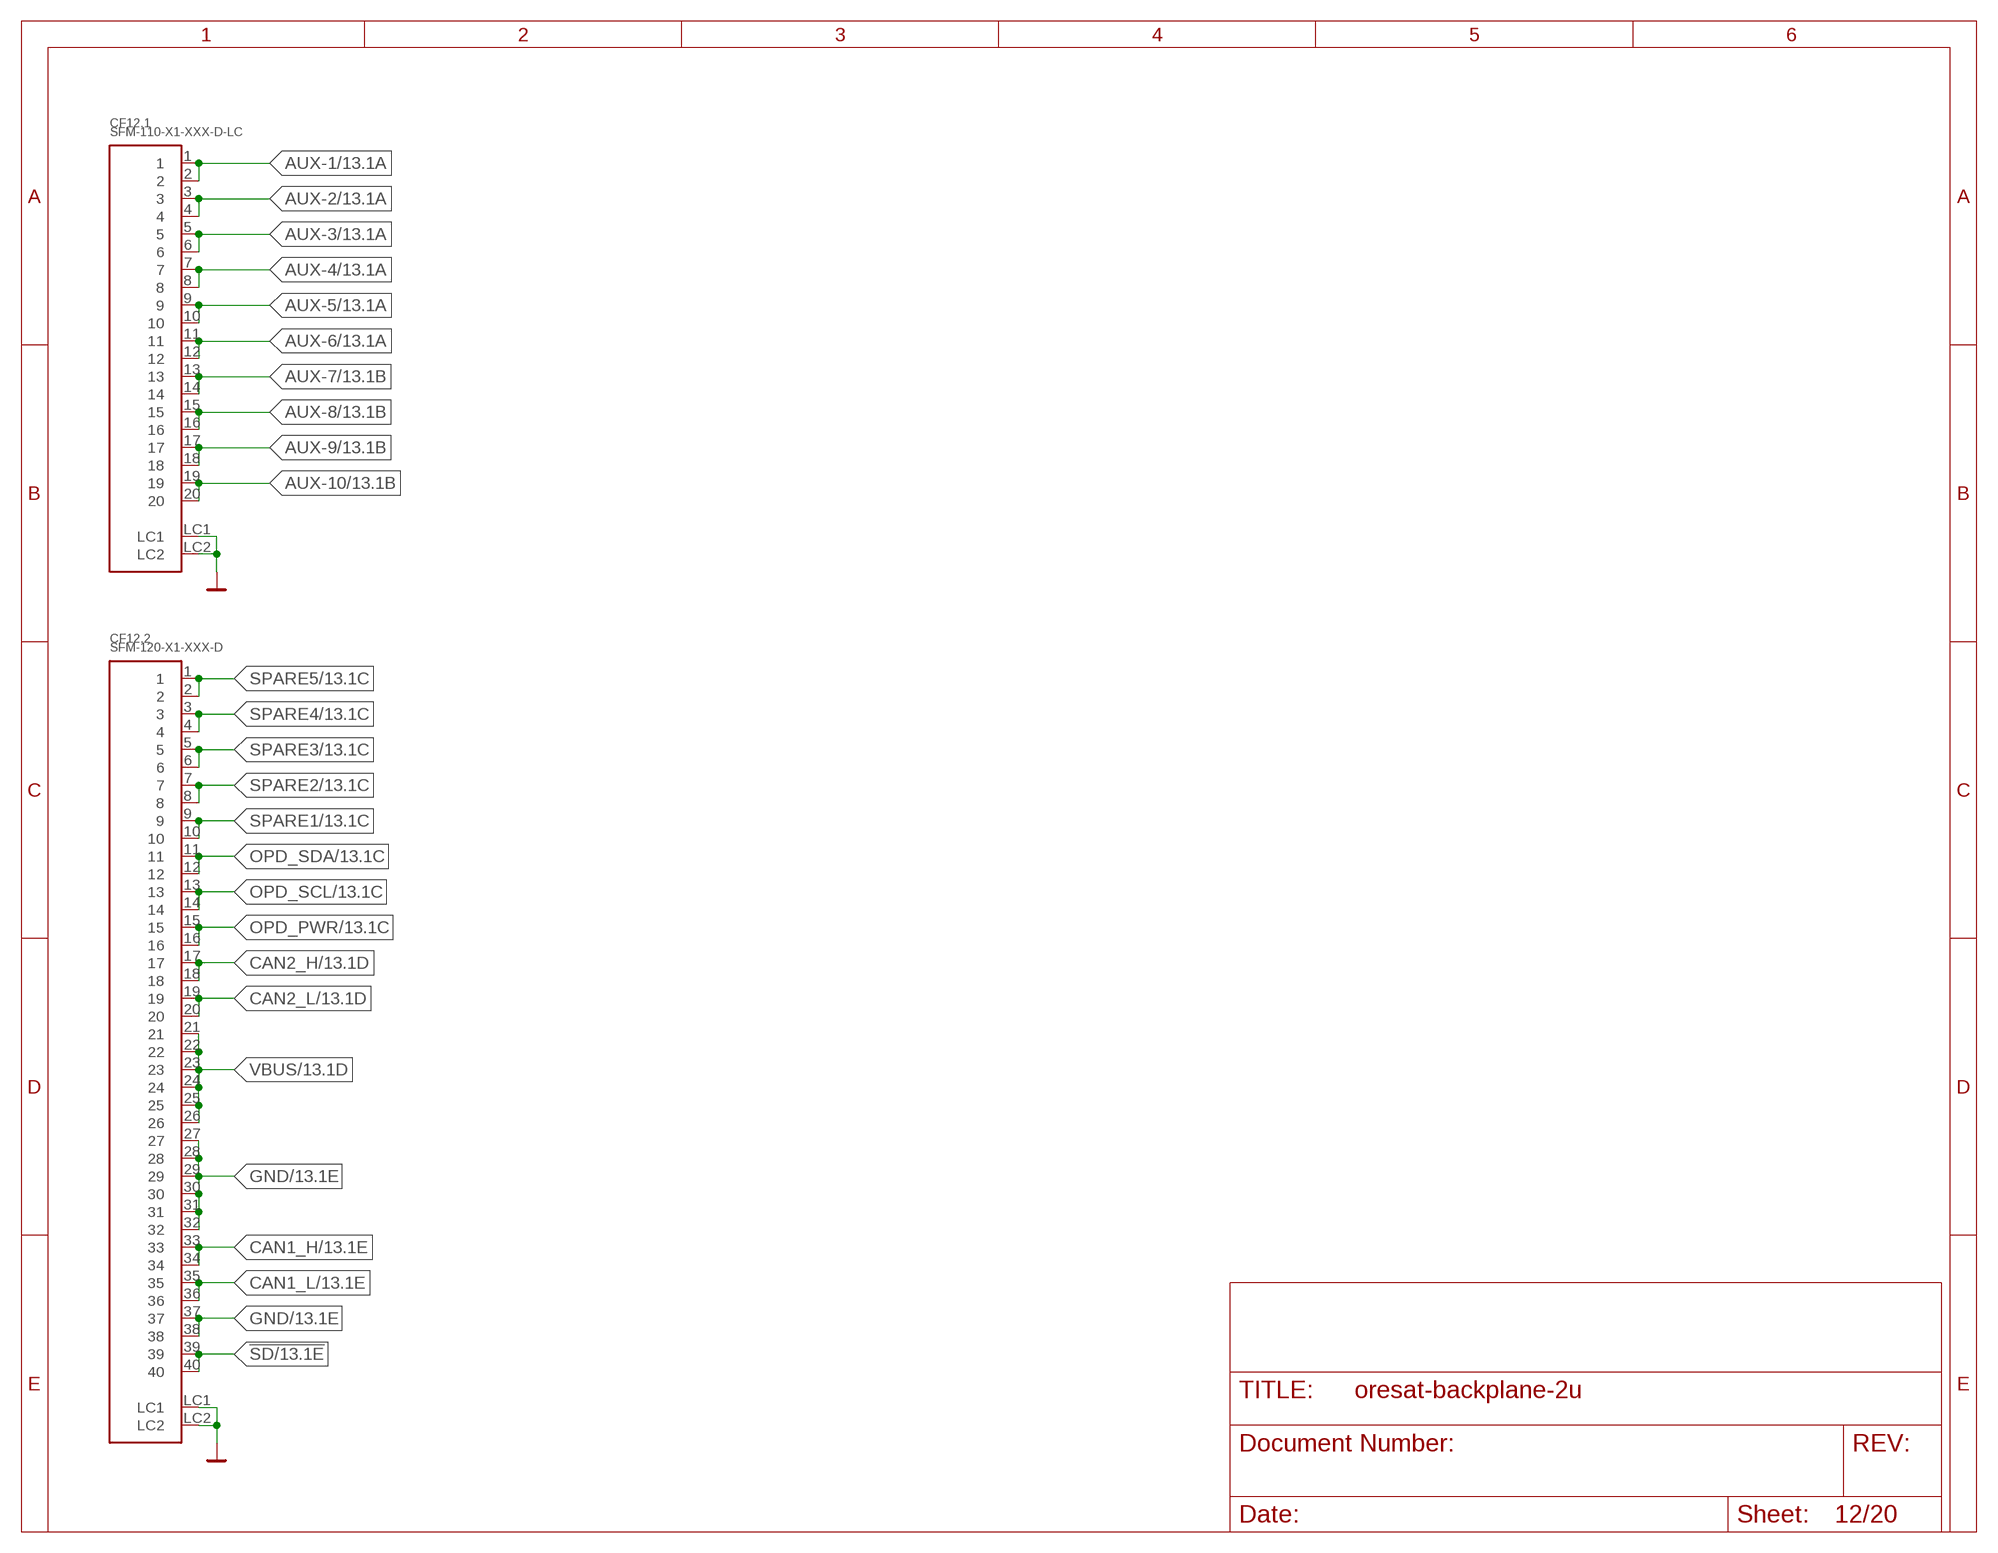
[diagram p11: schematic, sheet 12]
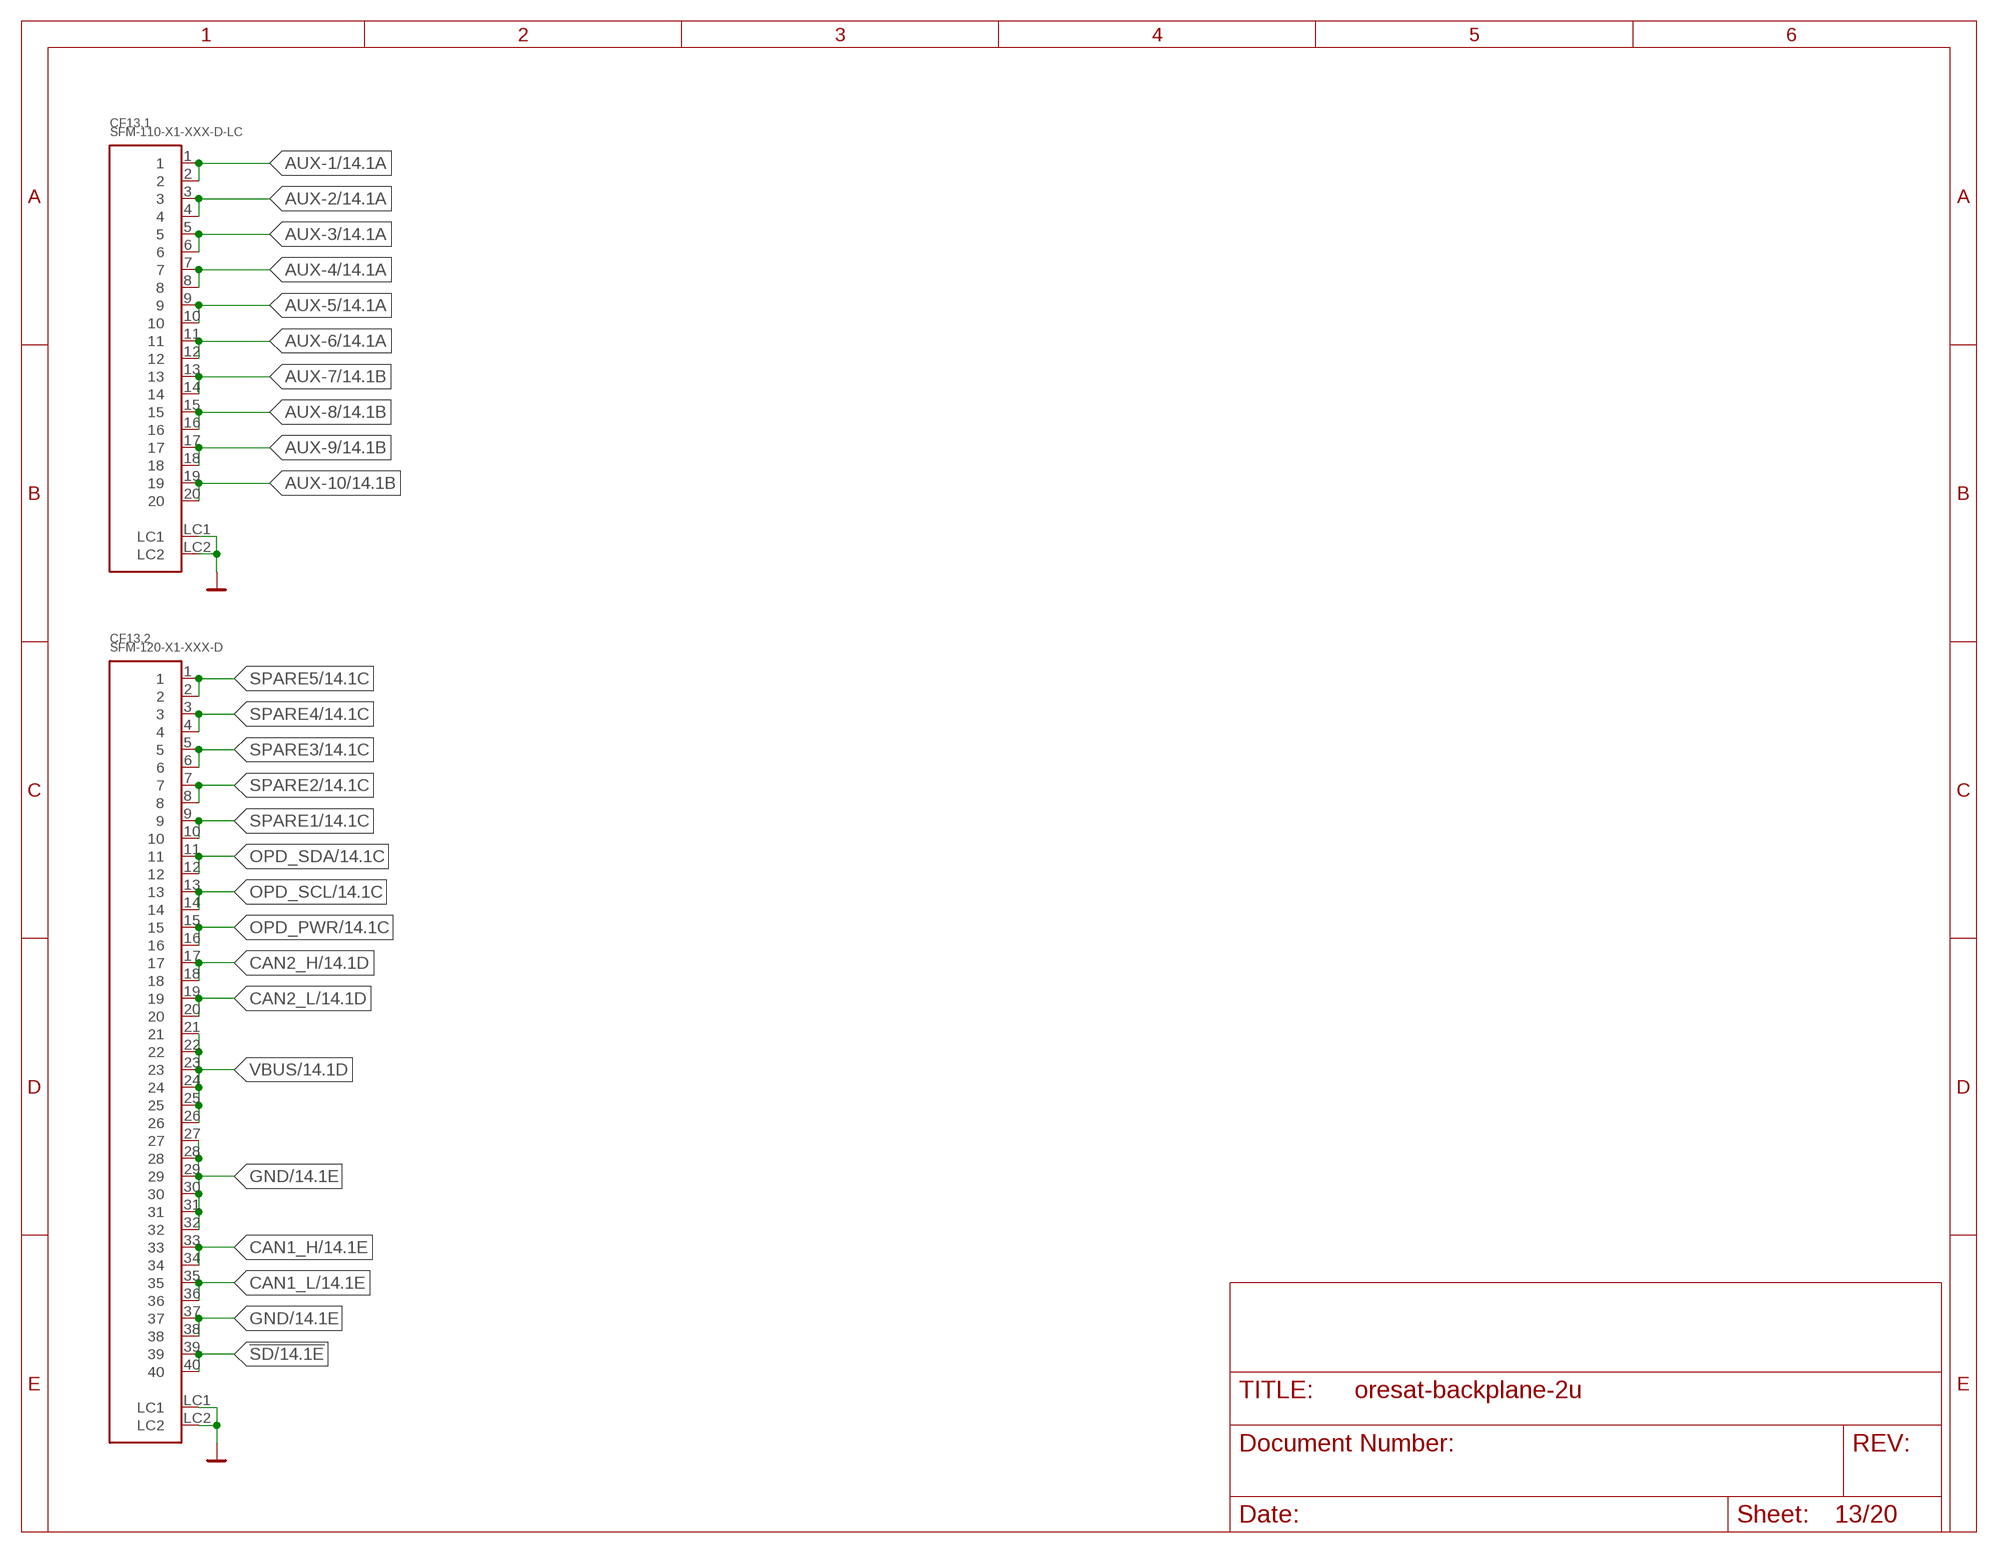
[diagram p12: schematic, sheet 13]
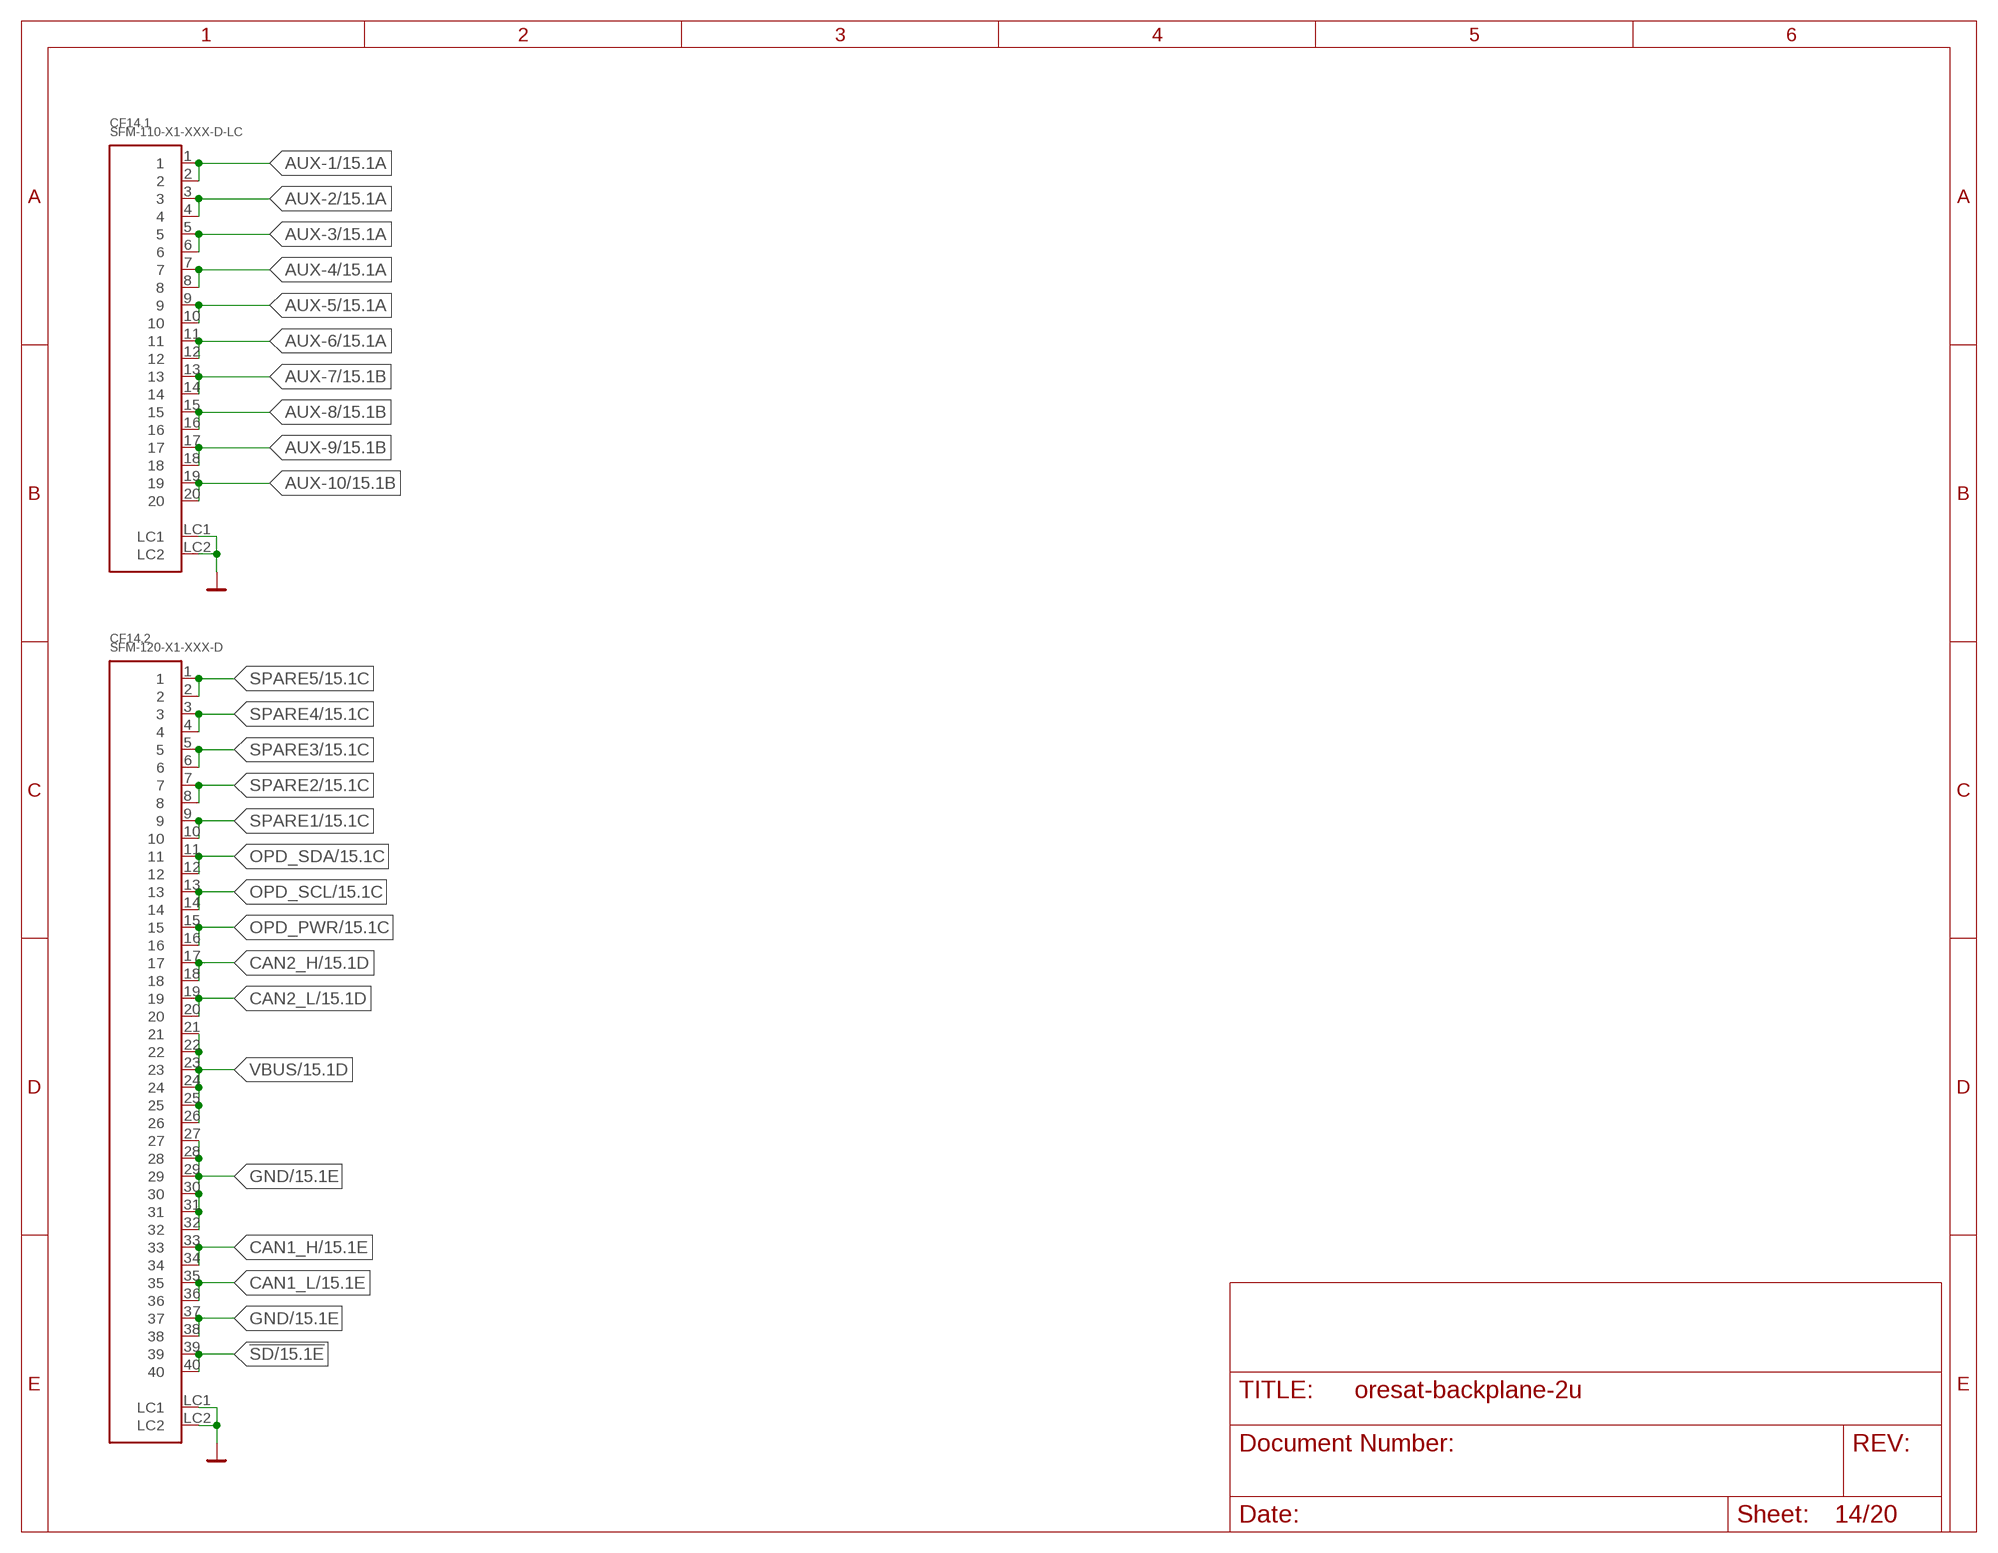
[diagram p13: schematic, sheet 14]
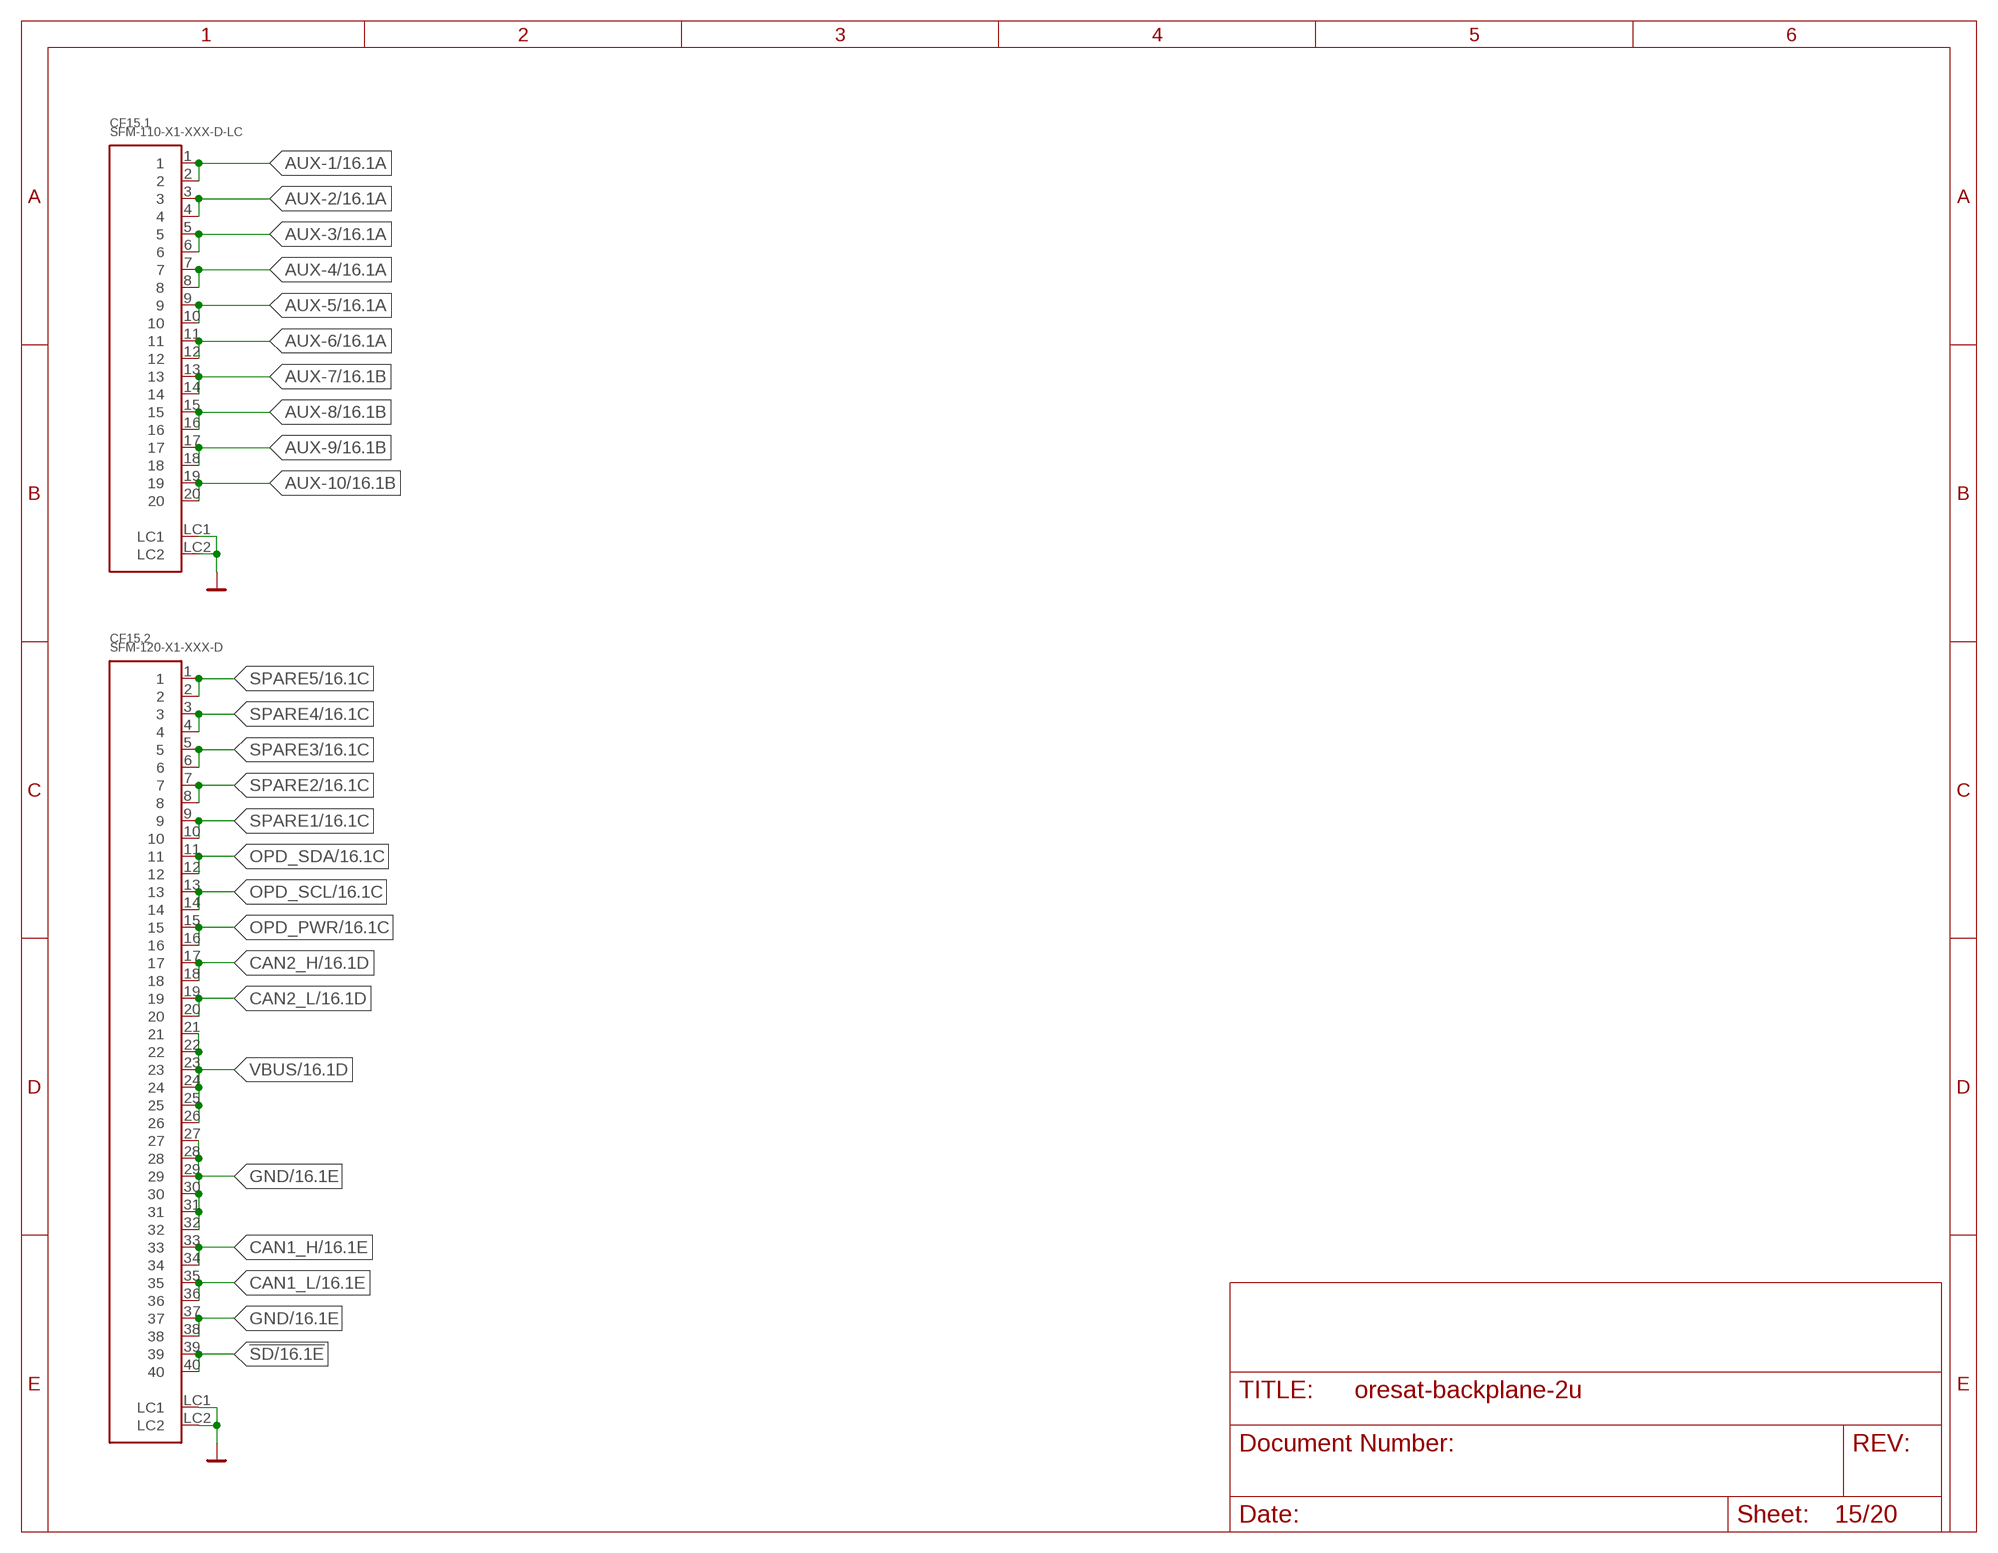
[diagram p14: schematic, sheet 15]
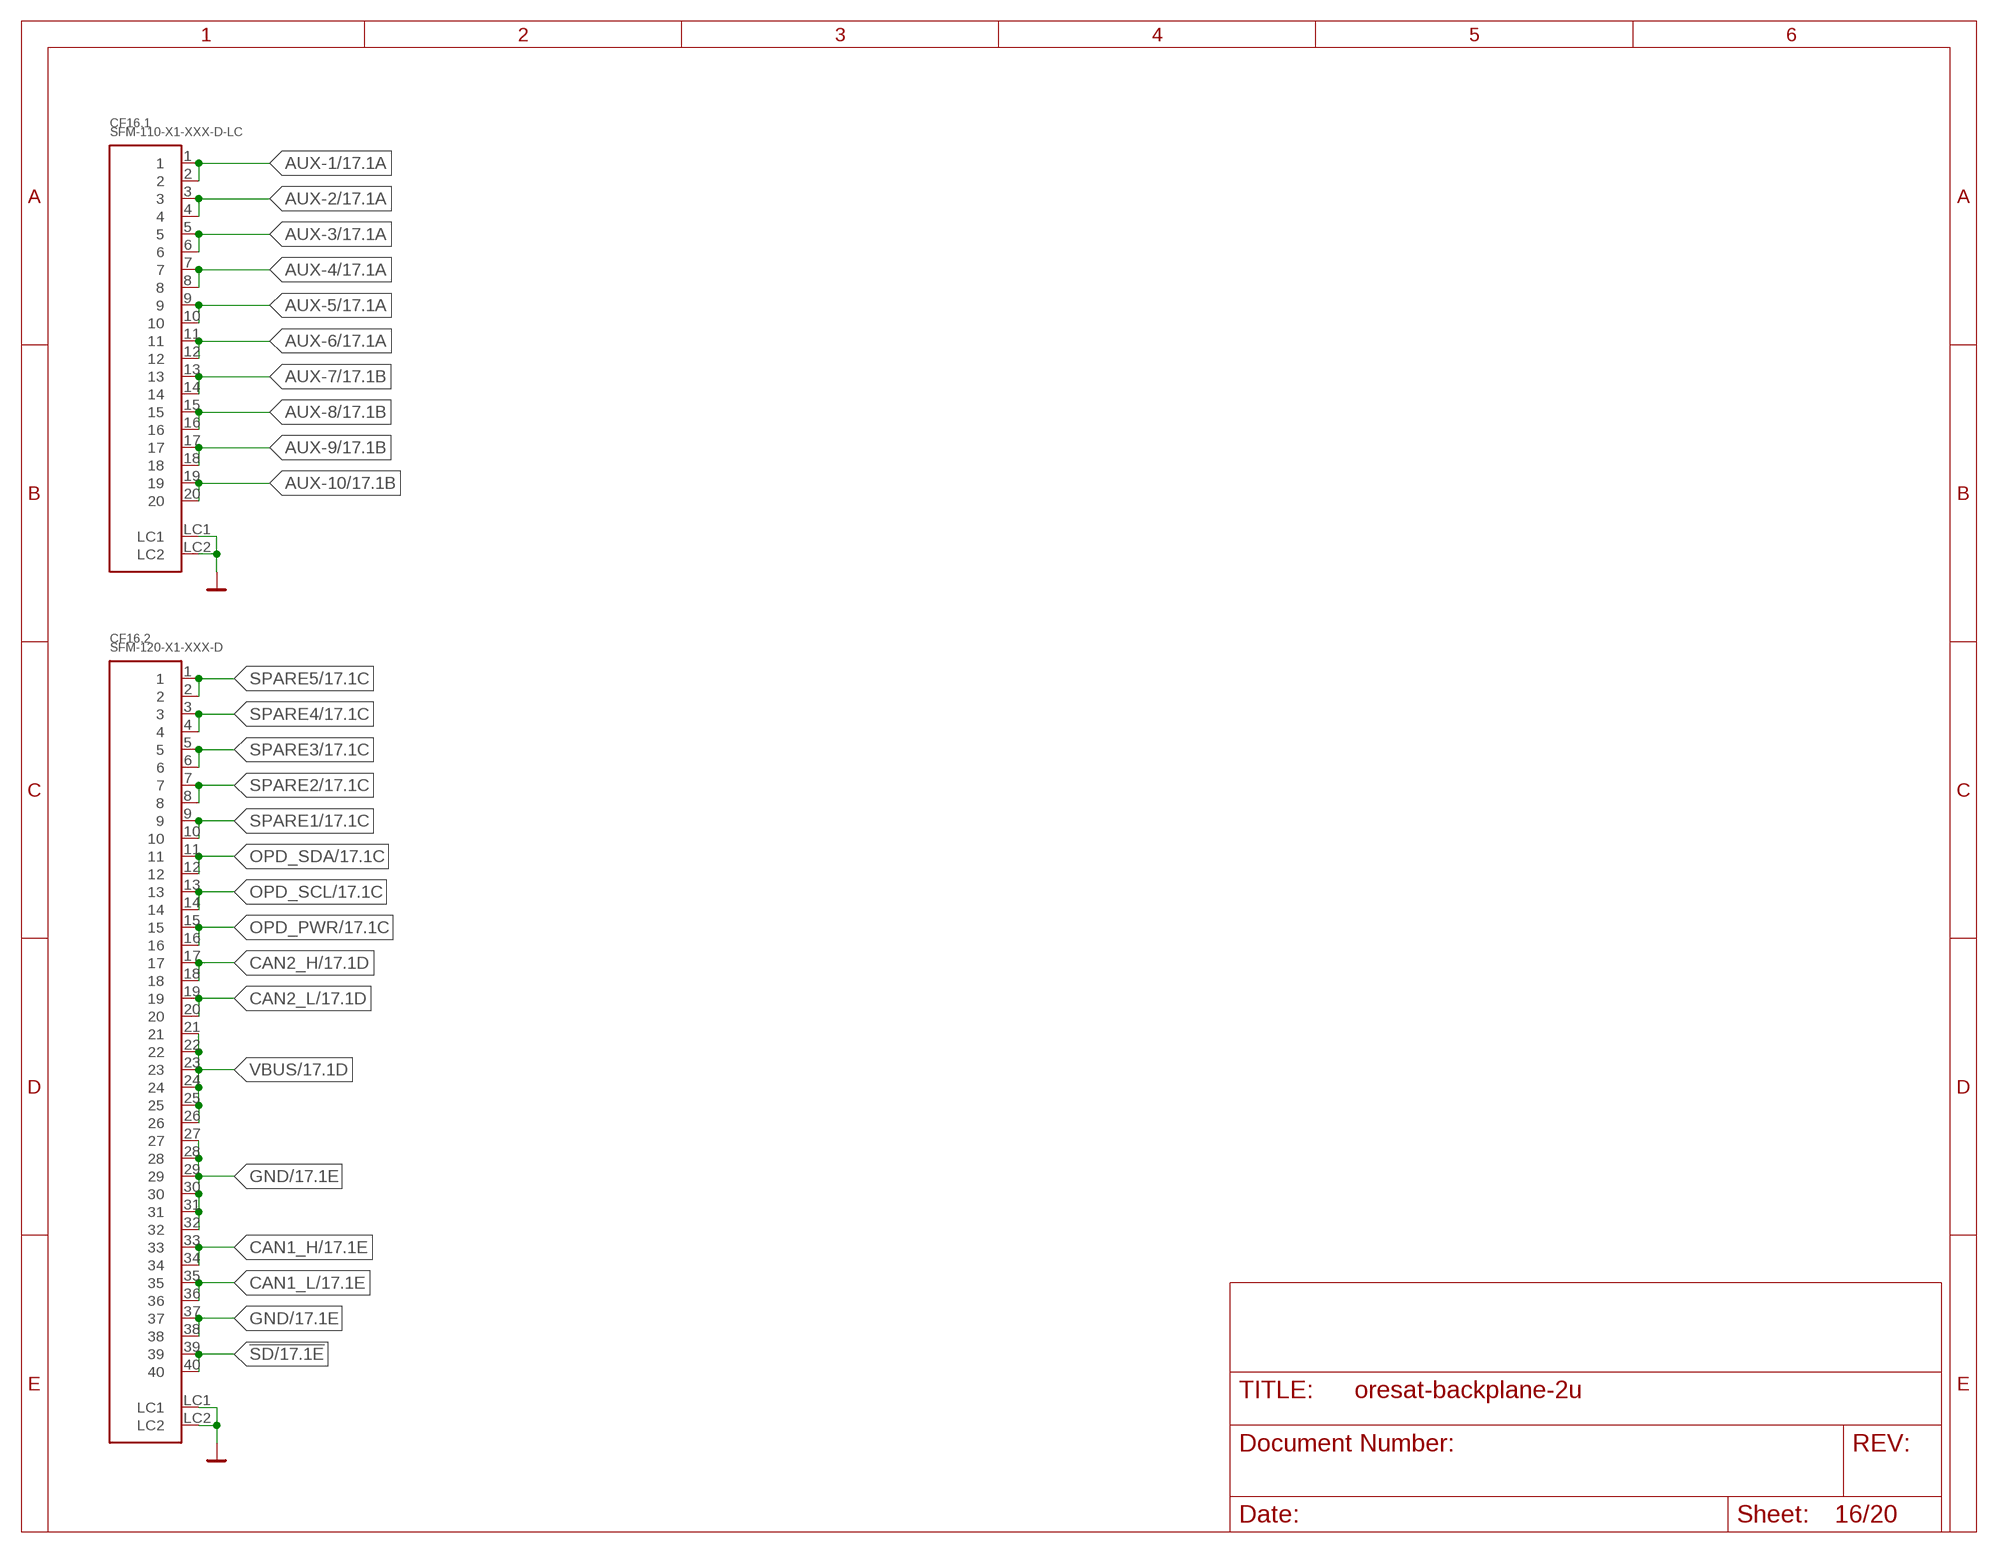
[diagram p15: schematic, sheet 16]
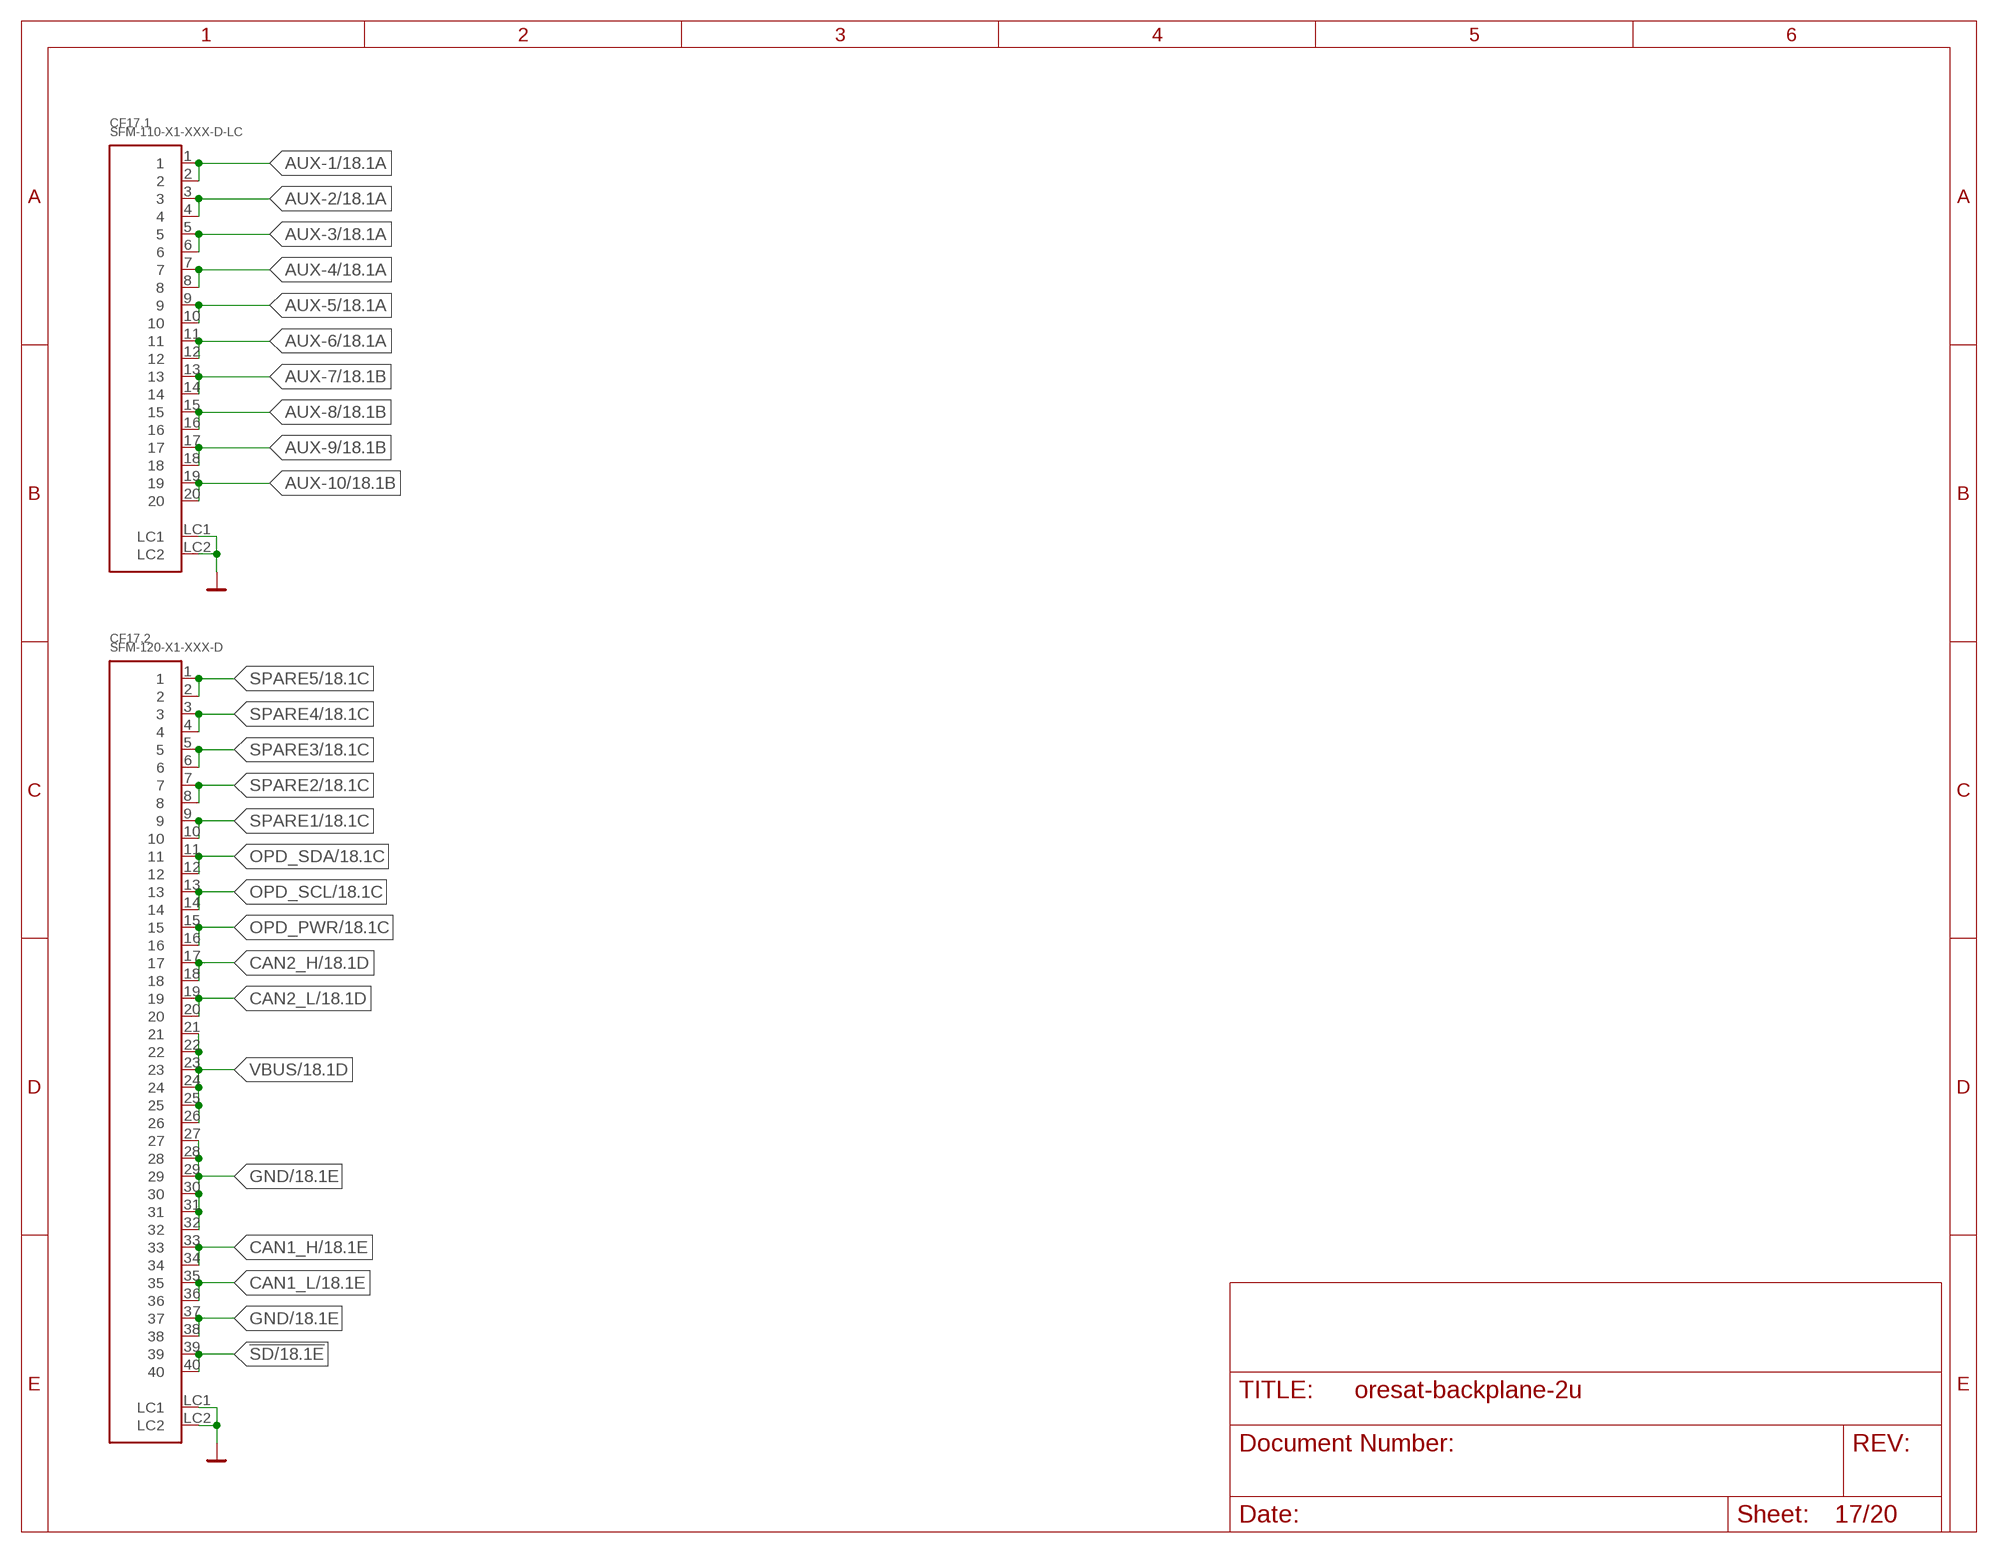
[diagram p16: schematic, sheet 17]
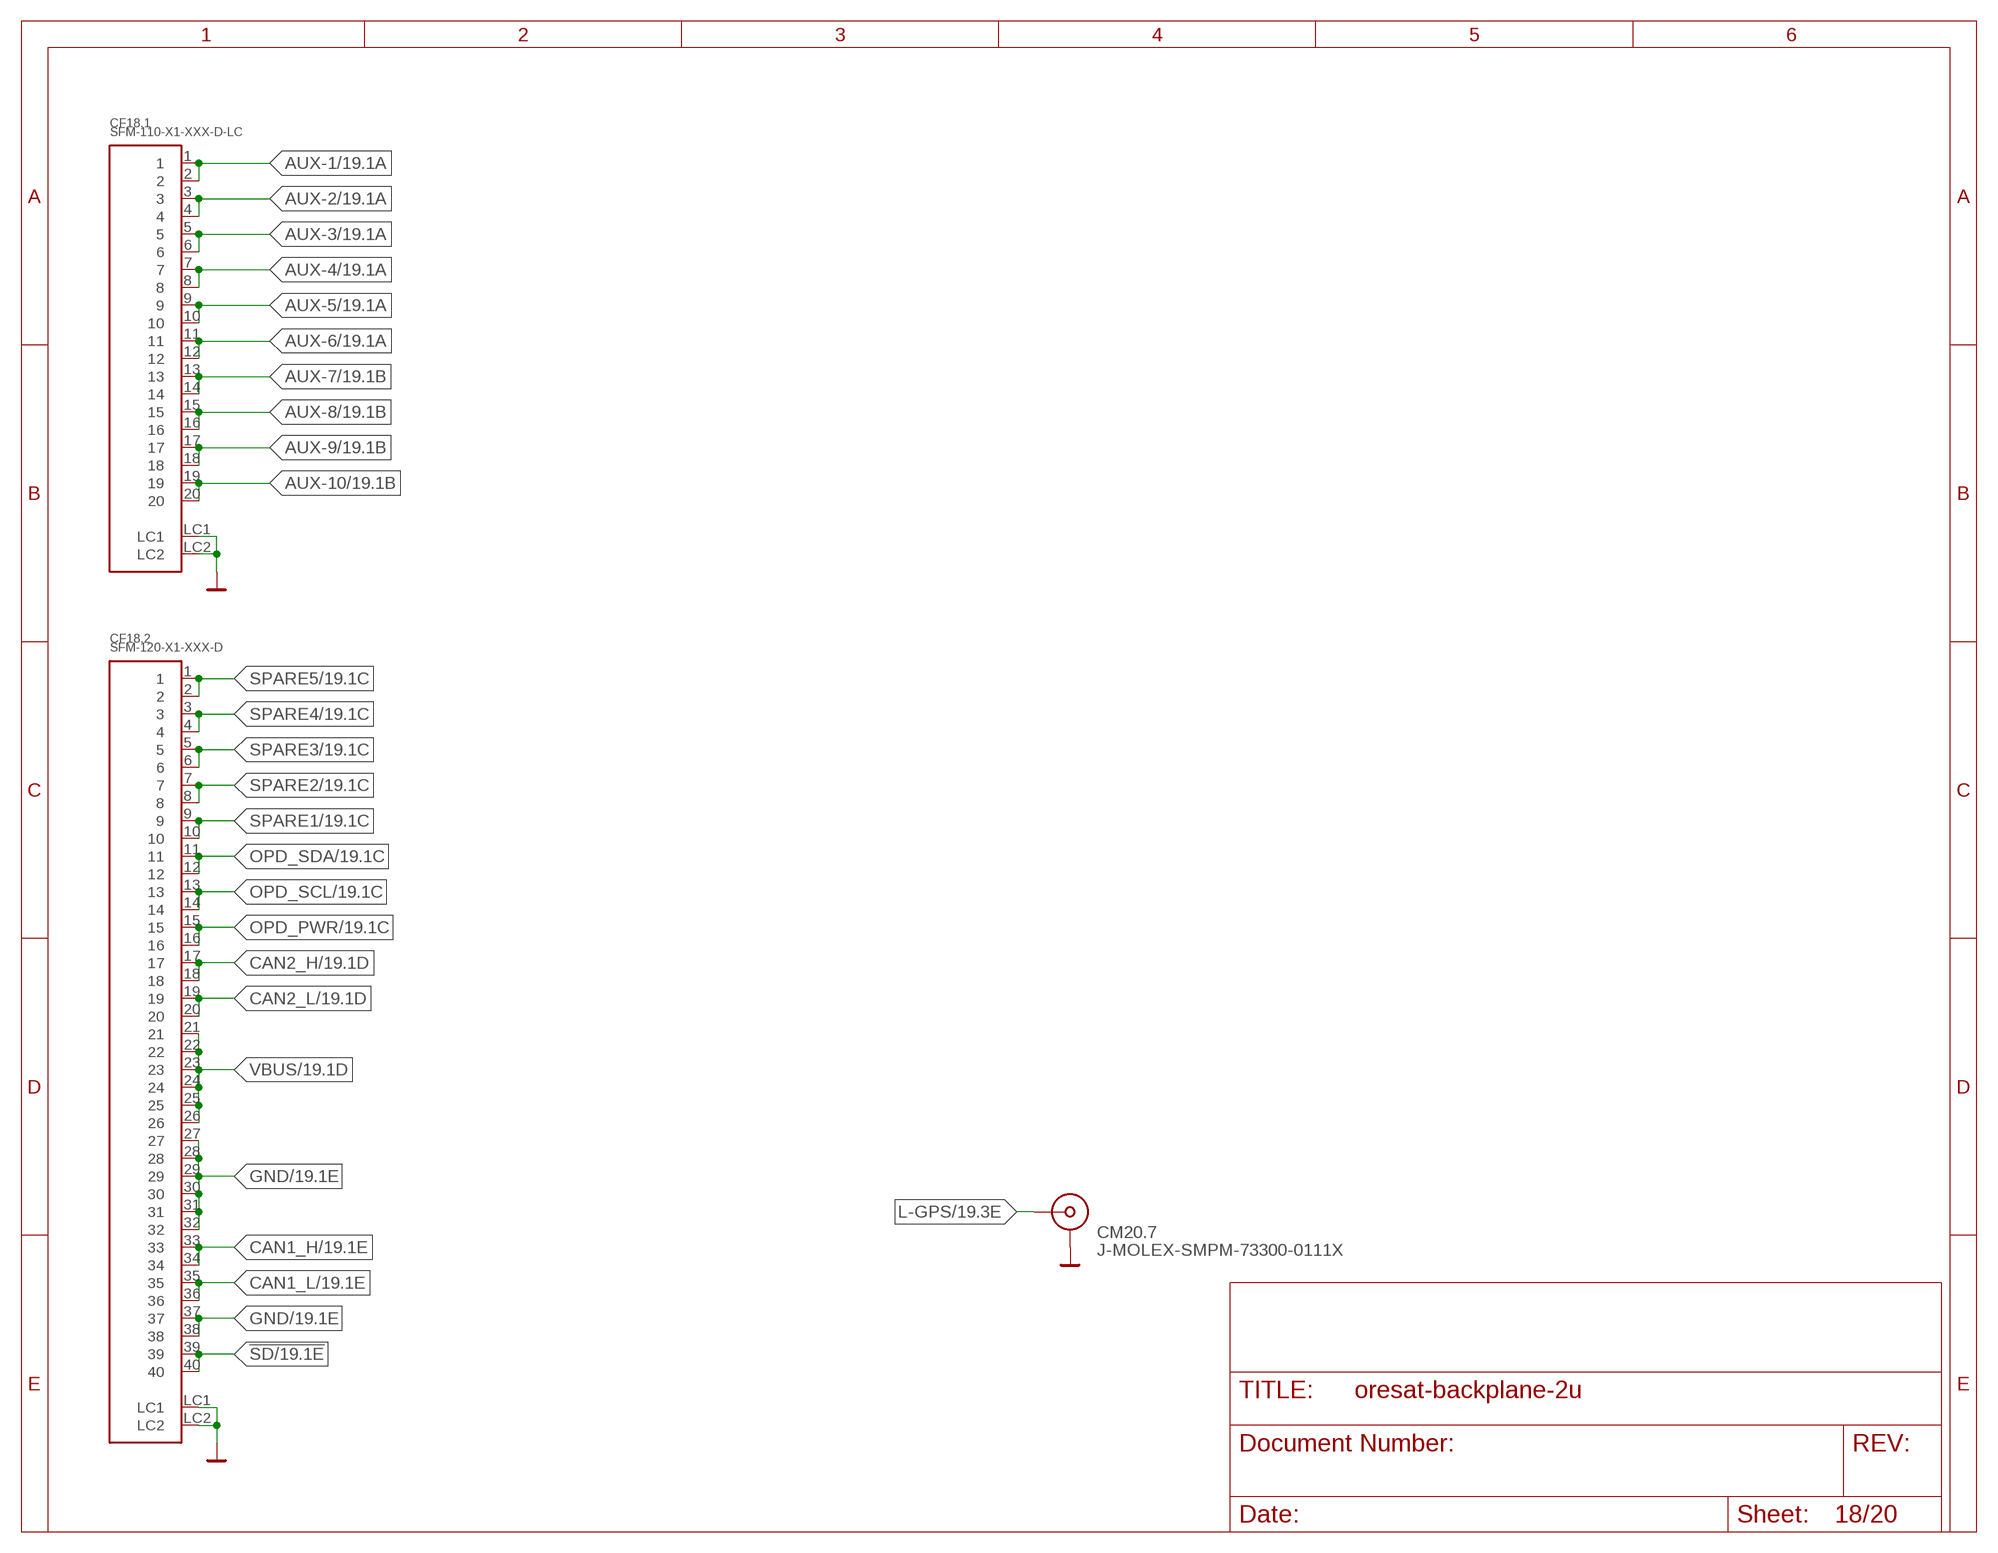
[diagram p17: schematic, sheet 18]
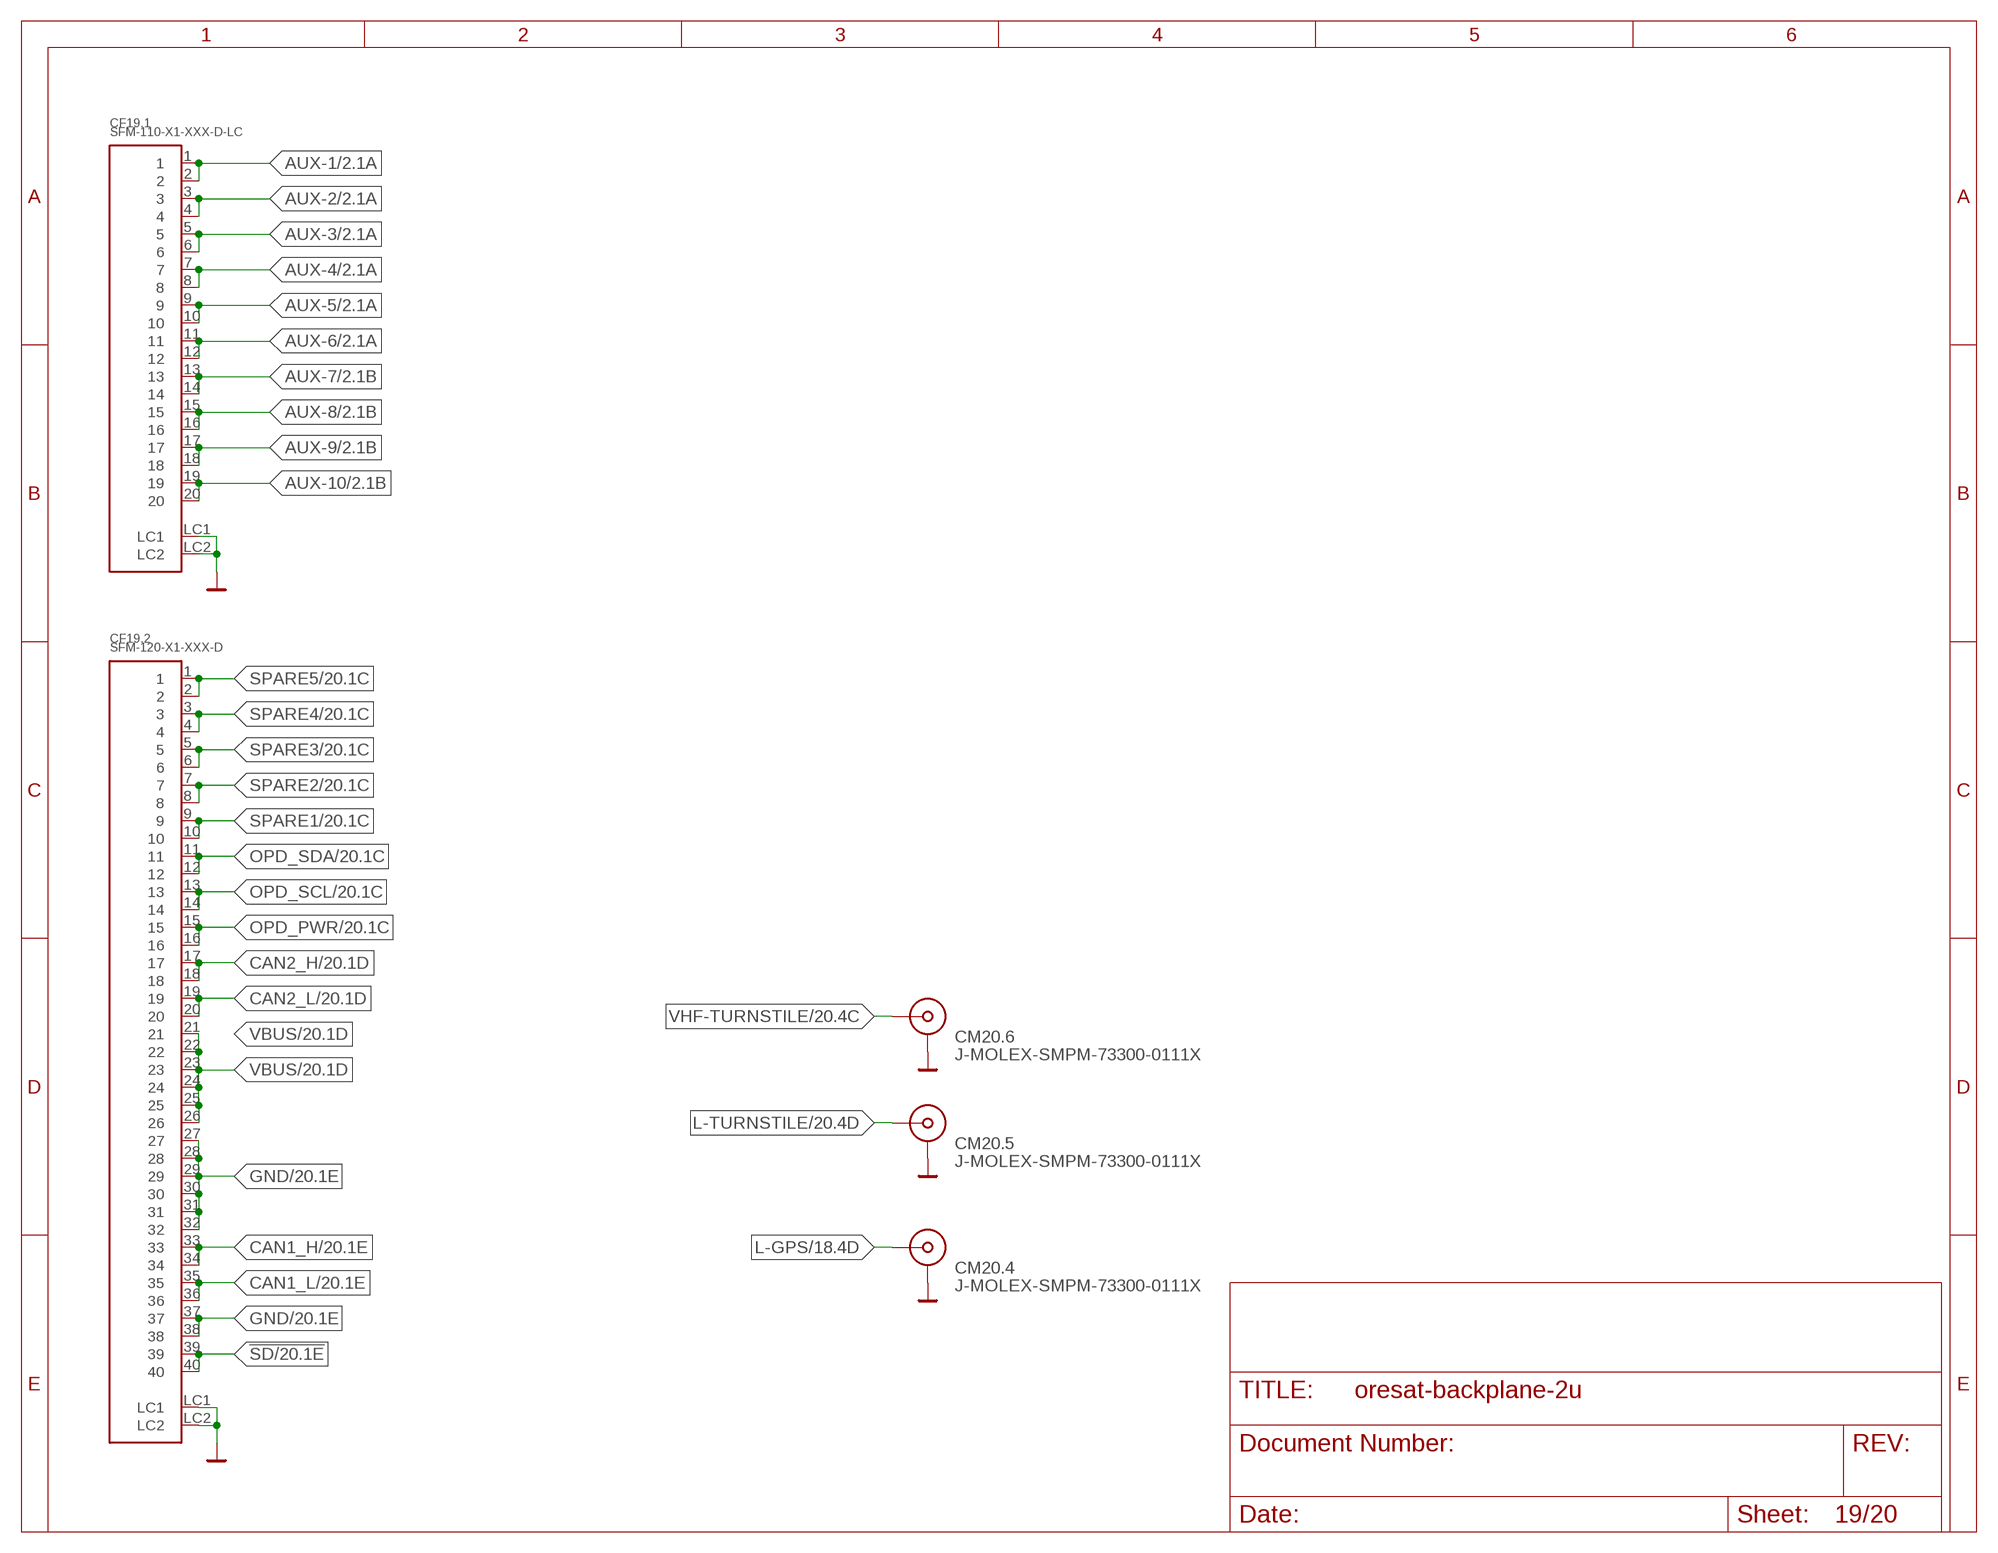
[diagram p18: schematic, sheet 19]
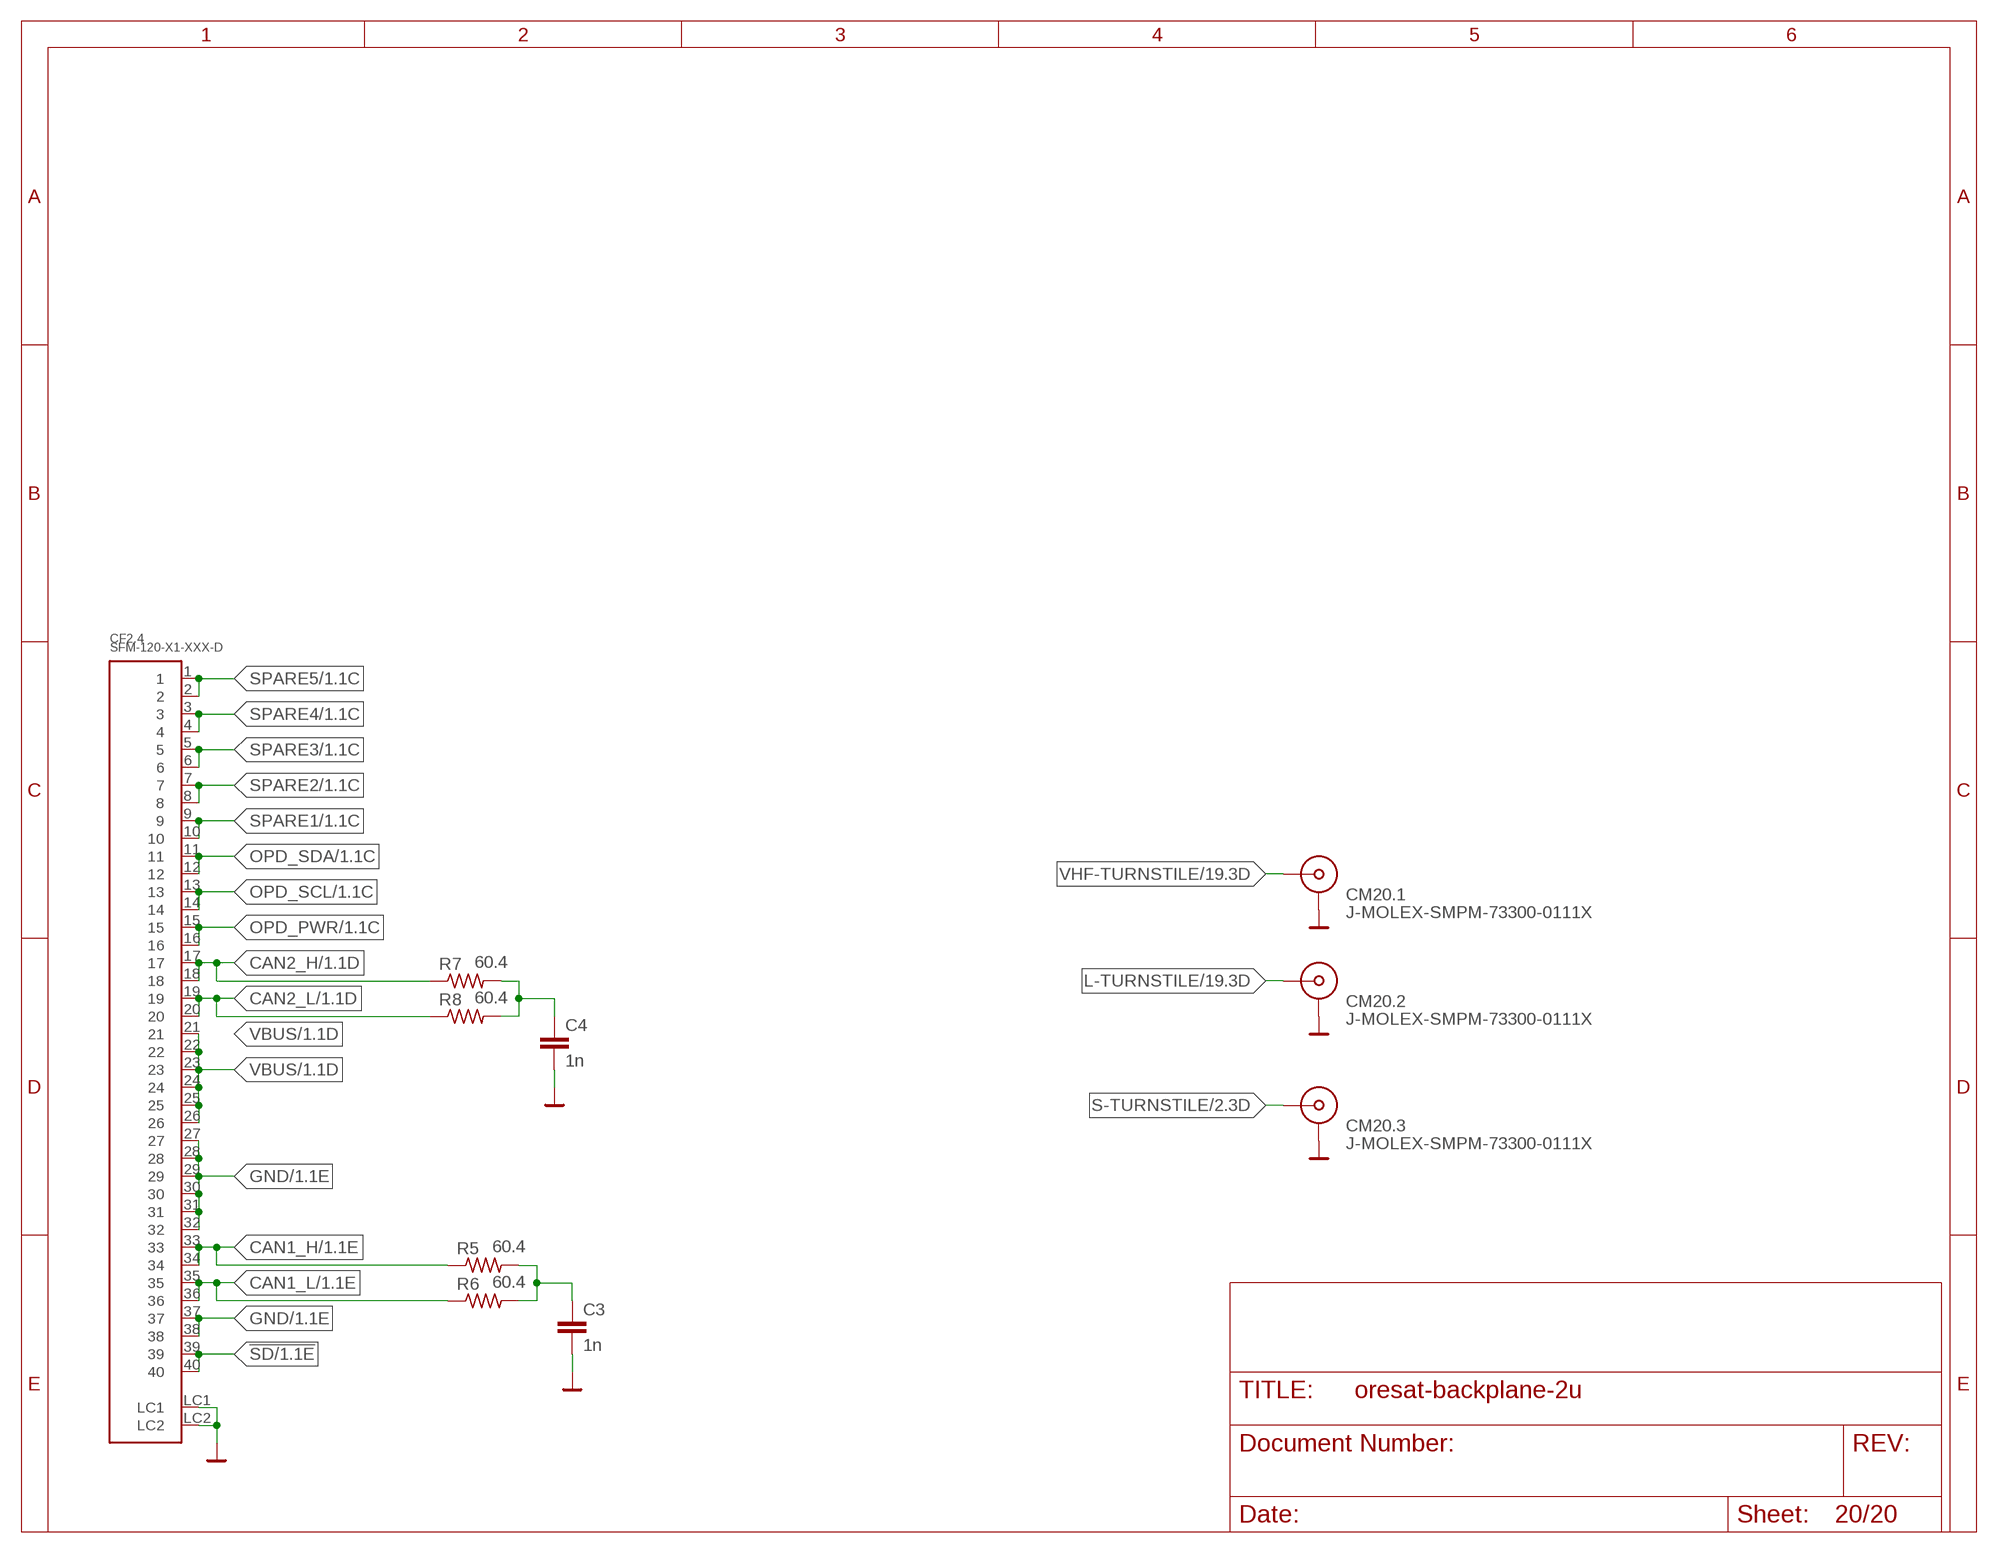
[diagram p19: schematic, sheet 20]

(export (version "E")
  (design (tool "Eeschema 10.0.6"))
  (components
    (comp (ref "CF4.1")
      (value "SFM-110-X1-XXX-D-LC")
      (footprint "eagle-import:SFM-110-X1-XXX-D-LC")
      (libsource (lib "eagle-import") (part "SFM-110-X1-XXX-D-LC"))
    )
    (comp (ref "CF4.2")
      (value "SFM-120-X1-XXX-D")
      (footprint "eagle-import:SFM-120-X1-XXX-D")
      (libsource (lib "eagle-import") (part "SFM-120-X1-XXX-D"))
    )
    (comp (ref "CF18.1")
      (value "SFM-110-X1-XXX-D-LC")
      (footprint "eagle-import:SFM-110-X1-XXX-D-LC")
      (libsource (lib "eagle-import") (part "SFM-110-X1-XXX-D-LC"))
    )
    (comp (ref "CF18.2")
      (value "SFM-120-X1-XXX-D")
      (footprint "eagle-import:SFM-120-X1-XXX-D")
      (libsource (lib "eagle-import") (part "SFM-120-X1-XXX-D"))
    )
    (comp (ref "CM20.7")
      (value "J-MOLEX-SMPM-73300-0111X")
      (footprint "eagle-import:J-MOLEX-SMPM-73300-0111X")
      (libsource (lib "eagle-import") (part "J-MOLEX-SMPM-73300-0111X"))
    )
    (comp (ref "CF17.1")
      (value "SFM-110-X1-XXX-D-LC")
      (footprint "eagle-import:SFM-110-X1-XXX-D-LC")
      (libsource (lib "eagle-import") (part "SFM-110-X1-XXX-D-LC"))
    )
    (comp (ref "CF17.2")
      (value "SFM-120-X1-XXX-D")
      (footprint "eagle-import:SFM-120-X1-XXX-D")
      (libsource (lib "eagle-import") (part "SFM-120-X1-XXX-D"))
    )
    (comp (ref "CF8.1")
      (value "SFM-110-X1-XXX-D-LC")
      (footprint "eagle-import:SFM-110-X1-XXX-D-LC")
      (libsource (lib "eagle-import") (part "SFM-110-X1-XXX-D-LC"))
    )
    (comp (ref "CF8.2")
      (value "SFM-120-X1-XXX-D")
      (footprint "eagle-import:SFM-120-X1-XXX-D")
      (libsource (lib "eagle-import") (part "SFM-120-X1-XXX-D"))
    )
    (comp (ref "CF16.1")
      (value "SFM-110-X1-XXX-D-LC")
      (footprint "eagle-import:SFM-110-X1-XXX-D-LC")
      (libsource (lib "eagle-import") (part "SFM-110-X1-XXX-D-LC"))
    )
    (comp (ref "CF16.2")
      (value "SFM-120-X1-XXX-D")
      (footprint "eagle-import:SFM-120-X1-XXX-D")
      (libsource (lib "eagle-import") (part "SFM-120-X1-XXX-D"))
    )
    (comp (ref "CF12.1")
      (value "SFM-110-X1-XXX-D-LC")
      (footprint "eagle-import:SFM-110-X1-XXX-D-LC")
      (libsource (lib "eagle-import") (part "SFM-110-X1-XXX-D-LC"))
    )
    (comp (ref "CF12.2")
      (value "SFM-120-X1-XXX-D")
      (footprint "eagle-import:SFM-120-X1-XXX-D")
      (libsource (lib "eagle-import") (part "SFM-120-X1-XXX-D"))
    )
    (comp (ref "CF15.1")
      (value "SFM-110-X1-XXX-D-LC")
      (footprint "eagle-import:SFM-110-X1-XXX-D-LC")
      (libsource (lib "eagle-import") (part "SFM-110-X1-XXX-D-LC"))
    )
    (comp (ref "CF15.2")
      (value "SFM-120-X1-XXX-D")
      (footprint "eagle-import:SFM-120-X1-XXX-D")
      (libsource (lib "eagle-import") (part "SFM-120-X1-XXX-D"))
    )
    (comp (ref "C1")
      (value "1n")
      (footprint "eagle-import:.0603-C-NOSILK")
      (libsource (lib "eagle-import") (part "C-EU0603-C-NOSILK"))
    )
    (comp (ref "C2")
      (value "1n")
      (footprint "eagle-import:.0603-C-NOSILK")
      (libsource (lib "eagle-import") (part "C-EU0603-C-NOSILK"))
    )
    (comp (ref "CF2.3")
      (value "SFM-120-X1-XXX-D")
      (footprint "eagle-import:SFM-120-X1-XXX-D")
      (libsource (lib "eagle-import") (part "SFM-120-X1-XXX-D"))
    )
    (comp (ref "CM1.1")
      (value "J-MOLEX-SMPM-73300-0111X")
      (footprint "eagle-import:J-MOLEX-SMPM-73300-0111X")
      (libsource (lib "eagle-import") (part "J-MOLEX-SMPM-73300-0111X"))
    )
    (comp (ref "R1")
      (value "60.4")
      (footprint "eagle-import:1206-C")
      (libsource (lib "eagle-import") (part "R-US_1206-C"))
    )
    (comp (ref "R2")
      (value "60.4")
      (footprint "eagle-import:1206-C")
      (libsource (lib "eagle-import") (part "R-US_1206-C"))
    )
    (comp (ref "R3")
      (value "60.4")
      (footprint "eagle-import:1206-C")
      (libsource (lib "eagle-import") (part "R-US_1206-C"))
    )
    (comp (ref "R4")
      (value "60.4")
      (footprint "eagle-import:1206-C")
      (libsource (lib "eagle-import") (part "R-US_1206-C"))
    )
    (comp (ref "CF13.1")
      (value "SFM-110-X1-XXX-D-LC")
      (footprint "eagle-import:SFM-110-X1-XXX-D-LC")
      (libsource (lib "eagle-import") (part "SFM-110-X1-XXX-D-LC"))
    )
    (comp (ref "CF13.2")
      (value "SFM-120-X1-XXX-D")
      (footprint "eagle-import:SFM-120-X1-XXX-D")
      (libsource (lib "eagle-import") (part "SFM-120-X1-XXX-D"))
    )
    (comp (ref "CF7.1")
      (value "SFM-110-X1-XXX-D-LC")
      (footprint "eagle-import:SFM-110-X1-XXX-D-LC")
      (libsource (lib "eagle-import") (part "SFM-110-X1-XXX-D-LC"))
    )
    (comp (ref "CF7.2")
      (value "SFM-120-X1-XXX-D")
      (footprint "eagle-import:SFM-120-X1-XXX-D")
      (libsource (lib "eagle-import") (part "SFM-120-X1-XXX-D"))
    )
    (comp (ref "C3")
      (value "1n")
      (footprint "eagle-import:.0603-C-NOSILK")
      (libsource (lib "eagle-import") (part "C-EU0603-C-NOSILK"))
    )
    (comp (ref "C4")
      (value "1n")
      (footprint "eagle-import:.0603-C-NOSILK")
      (libsource (lib "eagle-import") (part "C-EU0603-C-NOSILK"))
    )
    (comp (ref "CF2.4")
      (value "SFM-120-X1-XXX-D")
      (footprint "eagle-import:SFM-120-X1-XXX-D")
      (libsource (lib "eagle-import") (part "SFM-120-X1-XXX-D"))
    )
    (comp (ref "CM20.1")
      (value "J-MOLEX-SMPM-73300-0111X")
      (footprint "eagle-import:J-MOLEX-SMPM-73300-0111X")
      (libsource (lib "eagle-import") (part "J-MOLEX-SMPM-73300-0111X"))
    )
    (comp (ref "CM20.2")
      (value "J-MOLEX-SMPM-73300-0111X")
      (footprint "eagle-import:J-MOLEX-SMPM-73300-0111X")
      (libsource (lib "eagle-import") (part "J-MOLEX-SMPM-73300-0111X"))
    )
    (comp (ref "CM20.3")
      (value "J-MOLEX-SMPM-73300-0111X")
      (footprint "eagle-import:J-MOLEX-SMPM-73300-0111X")
      (libsource (lib "eagle-import") (part "J-MOLEX-SMPM-73300-0111X"))
    )
    (comp (ref "R5")
      (value "60.4")
      (footprint "eagle-import:1206-C")
      (libsource (lib "eagle-import") (part "R-US_1206-C"))
    )
    (comp (ref "R6")
      (value "60.4")
      (footprint "eagle-import:1206-C")
      (libsource (lib "eagle-import") (part "R-US_1206-C"))
    )
    (comp (ref "R7")
      (value "60.4")
      (footprint "eagle-import:1206-C")
      (libsource (lib "eagle-import") (part "R-US_1206-C"))
    )
    (comp (ref "R8")
      (value "60.4")
      (footprint "eagle-import:1206-C")
      (libsource (lib "eagle-import") (part "R-US_1206-C"))
    )
    (comp (ref "CF14.1")
      (value "SFM-110-X1-XXX-D-LC")
      (footprint "eagle-import:SFM-110-X1-XXX-D-LC")
      (libsource (lib "eagle-import") (part "SFM-110-X1-XXX-D-LC"))
    )
    (comp (ref "CF14.2")
      (value "SFM-120-X1-XXX-D")
      (footprint "eagle-import:SFM-120-X1-XXX-D")
      (libsource (lib "eagle-import") (part "SFM-120-X1-XXX-D"))
    )
    (comp (ref "CF3.1")
      (value "SFM-110-X1-XXX-D-LC")
      (footprint "eagle-import:SFM-110-X1-XXX-D-LC")
      (libsource (lib "eagle-import") (part "SFM-110-X1-XXX-D-LC"))
    )
    (comp (ref "CF3.2")
      (value "SFM-120-X1-XXX-D")
      (footprint "eagle-import:SFM-120-X1-XXX-D")
      (libsource (lib "eagle-import") (part "SFM-120-X1-XXX-D"))
    )
    (comp (ref "CF5.1")
      (value "SFM-110-X1-XXX-D-LC")
      (footprint "eagle-import:SFM-110-X1-XXX-D-LC")
      (libsource (lib "eagle-import") (part "SFM-110-X1-XXX-D-LC"))
    )
    (comp (ref "CF5.2")
      (value "SFM-120-X1-XXX-D")
      (footprint "eagle-import:SFM-120-X1-XXX-D")
      (libsource (lib "eagle-import") (part "SFM-120-X1-XXX-D"))
    )
    (comp (ref "CF19.1")
      (value "SFM-110-X1-XXX-D-LC")
      (footprint "eagle-import:SFM-110-X1-XXX-D-LC")
      (libsource (lib "eagle-import") (part "SFM-110-X1-XXX-D-LC"))
    )
    (comp (ref "CF19.2")
      (value "SFM-120-X1-XXX-D")
      (footprint "eagle-import:SFM-120-X1-XXX-D")
      (libsource (lib "eagle-import") (part "SFM-120-X1-XXX-D"))
    )
    (comp (ref "CM20.4")
      (value "J-MOLEX-SMPM-73300-0111X")
      (footprint "eagle-import:J-MOLEX-SMPM-73300-0111X")
      (libsource (lib "eagle-import") (part "J-MOLEX-SMPM-73300-0111X"))
    )
    (comp (ref "CM20.5")
      (value "J-MOLEX-SMPM-73300-0111X")
      (footprint "eagle-import:J-MOLEX-SMPM-73300-0111X")
      (libsource (lib "eagle-import") (part "J-MOLEX-SMPM-73300-0111X"))
    )
    (comp (ref "CM20.6")
      (value "J-MOLEX-SMPM-73300-0111X")
      (footprint "eagle-import:J-MOLEX-SMPM-73300-0111X")
      (libsource (lib "eagle-import") (part "J-MOLEX-SMPM-73300-0111X"))
    )
    (comp (ref "CF2.1")
      (value "SFM-110-X1-XXX-D-LC")
      (footprint "eagle-import:SFM-110-X1-XXX-D-LC")
      (libsource (lib "eagle-import") (part "SFM-110-X1-XXX-D-LC"))
    )
    (comp (ref "CF2.2")
      (value "SFM-120-X1-XXX-D")
      (footprint "eagle-import:SFM-120-X1-XXX-D")
      (libsource (lib "eagle-import") (part "SFM-120-X1-XXX-D"))
    )
    (comp (ref "CM2.1")
      (value "J-MOLEX-SMPM-73300-0111X")
      (footprint "eagle-import:J-MOLEX-SMPM-73300-0111X")
      (libsource (lib "eagle-import") (part "J-MOLEX-SMPM-73300-0111X"))
    )
    (comp (ref "CM2.2")
      (value "J-MOLEX-SMPM-73300-0111X")
      (footprint "eagle-import:J-MOLEX-SMPM-73300-0111X")
      (libsource (lib "eagle-import") (part "J-MOLEX-SMPM-73300-0111X"))
    )
    (comp (ref "CF6.1")
      (value "SFM-110-X1-XXX-D-LC")
      (footprint "eagle-import:SFM-110-X1-XXX-D-LC")
      (libsource (lib "eagle-import") (part "SFM-110-X1-XXX-D-LC"))
    )
    (comp (ref "CF6.2")
      (value "SFM-120-X1-XXX-D")
      (footprint "eagle-import:SFM-120-X1-XXX-D")
      (libsource (lib "eagle-import") (part "SFM-120-X1-XXX-D"))
    )
  )
  (nets
    (net (code "1") (name "AUX-1") (class "Default")
      (node (ref "CF12.1") (pin "1") (pinfunction "1_1") (pintype "passive"))
      (node (ref "CF12.1") (pin "2") (pinfunction "2_2") (pintype "passive"))
      (node (ref "CF13.1") (pin "1") (pinfunction "1_1") (pintype "passive"))
      (node (ref "CF13.1") (pin "2") (pinfunction "2_2") (pintype "passive"))
      (node (ref "CF14.1") (pin "1") (pinfunction "1_1") (pintype "passive"))
      (node (ref "CF14.1") (pin "2") (pinfunction "2_2") (pintype "passive"))
      (node (ref "CF15.1") (pin "1") (pinfunction "1_1") (pintype "passive"))
      (node (ref "CF15.1") (pin "2") (pinfunction "2_2") (pintype "passive"))
      (node (ref "CF16.1") (pin "1") (pinfunction "1_1") (pintype "passive"))
      (node (ref "CF16.1") (pin "2") (pinfunction "2_2") (pintype "passive"))
      (node (ref "CF17.1") (pin "1") (pinfunction "1_1") (pintype "passive"))
      (node (ref "CF17.1") (pin "2") (pinfunction "2_2") (pintype "passive"))
      (node (ref "CF18.1") (pin "1") (pinfunction "1_1") (pintype "passive"))
      (node (ref "CF18.1") (pin "2") (pinfunction "2_2") (pintype "passive"))
      (node (ref "CF19.1") (pin "1") (pinfunction "1_1") (pintype "passive"))
      (node (ref "CF19.1") (pin "2") (pinfunction "2_2") (pintype "passive"))
      (node (ref "CF2.1") (pin "1") (pinfunction "1_1") (pintype "passive"))
      (node (ref "CF2.1") (pin "2") (pinfunction "2_2") (pintype "passive"))
      (node (ref "CF3.1") (pin "1") (pinfunction "1_1") (pintype "passive"))
      (node (ref "CF3.1") (pin "2") (pinfunction "2_2") (pintype "passive"))
      (node (ref "CF4.1") (pin "1") (pinfunction "1_1") (pintype "passive"))
      (node (ref "CF4.1") (pin "2") (pinfunction "2_2") (pintype "passive"))
      (node (ref "CF5.1") (pin "1") (pinfunction "1_1") (pintype "passive"))
      (node (ref "CF5.1") (pin "2") (pinfunction "2_2") (pintype "passive"))
      (node (ref "CF6.1") (pin "1") (pinfunction "1_1") (pintype "passive"))
      (node (ref "CF6.1") (pin "2") (pinfunction "2_2") (pintype "passive"))
      (node (ref "CF7.1") (pin "1") (pinfunction "1_1") (pintype "passive"))
      (node (ref "CF7.1") (pin "2") (pinfunction "2_2") (pintype "passive"))
      (node (ref "CF8.1") (pin "1") (pinfunction "1_1") (pintype "passive"))
      (node (ref "CF8.1") (pin "2") (pinfunction "2_2") (pintype "passive"))
    )
    (net (code "2") (name "AUX-2") (class "Default")
      (node (ref "CF12.1") (pin "3") (pinfunction "3_3") (pintype "passive"))
      (node (ref "CF12.1") (pin "4") (pinfunction "4_4") (pintype "passive"))
      (node (ref "CF13.1") (pin "3") (pinfunction "3_3") (pintype "passive"))
      (node (ref "CF13.1") (pin "4") (pinfunction "4_4") (pintype "passive"))
      (node (ref "CF14.1") (pin "3") (pinfunction "3_3") (pintype "passive"))
      (node (ref "CF14.1") (pin "4") (pinfunction "4_4") (pintype "passive"))
      (node (ref "CF15.1") (pin "3") (pinfunction "3_3") (pintype "passive"))
      (node (ref "CF15.1") (pin "4") (pinfunction "4_4") (pintype "passive"))
      (node (ref "CF16.1") (pin "3") (pinfunction "3_3") (pintype "passive"))
      (node (ref "CF16.1") (pin "4") (pinfunction "4_4") (pintype "passive"))
      (node (ref "CF17.1") (pin "3") (pinfunction "3_3") (pintype "passive"))
      (node (ref "CF17.1") (pin "4") (pinfunction "4_4") (pintype "passive"))
      (node (ref "CF18.1") (pin "3") (pinfunction "3_3") (pintype "passive"))
      (node (ref "CF18.1") (pin "4") (pinfunction "4_4") (pintype "passive"))
      (node (ref "CF19.1") (pin "3") (pinfunction "3_3") (pintype "passive"))
      (node (ref "CF19.1") (pin "4") (pinfunction "4_4") (pintype "passive"))
      (node (ref "CF2.1") (pin "3") (pinfunction "3_3") (pintype "passive"))
      (node (ref "CF2.1") (pin "4") (pinfunction "4_4") (pintype "passive"))
      (node (ref "CF3.1") (pin "3") (pinfunction "3_3") (pintype "passive"))
      (node (ref "CF3.1") (pin "4") (pinfunction "4_4") (pintype "passive"))
      (node (ref "CF4.1") (pin "3") (pinfunction "3_3") (pintype "passive"))
      (node (ref "CF4.1") (pin "4") (pinfunction "4_4") (pintype "passive"))
      (node (ref "CF5.1") (pin "3") (pinfunction "3_3") (pintype "passive"))
      (node (ref "CF5.1") (pin "4") (pinfunction "4_4") (pintype "passive"))
      (node (ref "CF6.1") (pin "3") (pinfunction "3_3") (pintype "passive"))
      (node (ref "CF6.1") (pin "4") (pinfunction "4_4") (pintype "passive"))
      (node (ref "CF7.1") (pin "3") (pinfunction "3_3") (pintype "passive"))
      (node (ref "CF7.1") (pin "4") (pinfunction "4_4") (pintype "passive"))
      (node (ref "CF8.1") (pin "3") (pinfunction "3_3") (pintype "passive"))
      (node (ref "CF8.1") (pin "4") (pinfunction "4_4") (pintype "passive"))
    )
    (net (code "3") (name "AUX-3") (class "Default")
      (node (ref "CF12.1") (pin "5") (pinfunction "5_5") (pintype "passive"))
      (node (ref "CF12.1") (pin "6") (pinfunction "6_6") (pintype "passive"))
      (node (ref "CF13.1") (pin "5") (pinfunction "5_5") (pintype "passive"))
      (node (ref "CF13.1") (pin "6") (pinfunction "6_6") (pintype "passive"))
      (node (ref "CF14.1") (pin "5") (pinfunction "5_5") (pintype "passive"))
      (node (ref "CF14.1") (pin "6") (pinfunction "6_6") (pintype "passive"))
      (node (ref "CF15.1") (pin "5") (pinfunction "5_5") (pintype "passive"))
      (node (ref "CF15.1") (pin "6") (pinfunction "6_6") (pintype "passive"))
      (node (ref "CF16.1") (pin "5") (pinfunction "5_5") (pintype "passive"))
      (node (ref "CF16.1") (pin "6") (pinfunction "6_6") (pintype "passive"))
      (node (ref "CF17.1") (pin "5") (pinfunction "5_5") (pintype "passive"))
      (node (ref "CF17.1") (pin "6") (pinfunction "6_6") (pintype "passive"))
      (node (ref "CF18.1") (pin "5") (pinfunction "5_5") (pintype "passive"))
      (node (ref "CF18.1") (pin "6") (pinfunction "6_6") (pintype "passive"))
      (node (ref "CF19.1") (pin "5") (pinfunction "5_5") (pintype "passive"))
      (node (ref "CF19.1") (pin "6") (pinfunction "6_6") (pintype "passive"))
      (node (ref "CF2.1") (pin "5") (pinfunction "5_5") (pintype "passive"))
      (node (ref "CF2.1") (pin "6") (pinfunction "6_6") (pintype "passive"))
      (node (ref "CF3.1") (pin "5") (pinfunction "5_5") (pintype "passive"))
      (node (ref "CF3.1") (pin "6") (pinfunction "6_6") (pintype "passive"))
      (node (ref "CF4.1") (pin "5") (pinfunction "5_5") (pintype "passive"))
      (node (ref "CF4.1") (pin "6") (pinfunction "6_6") (pintype "passive"))
      (node (ref "CF5.1") (pin "5") (pinfunction "5_5") (pintype "passive"))
      (node (ref "CF5.1") (pin "6") (pinfunction "6_6") (pintype "passive"))
      (node (ref "CF6.1") (pin "5") (pinfunction "5_5") (pintype "passive"))
      (node (ref "CF6.1") (pin "6") (pinfunction "6_6") (pintype "passive"))
      (node (ref "CF7.1") (pin "5") (pinfunction "5_5") (pintype "passive"))
      (node (ref "CF7.1") (pin "6") (pinfunction "6_6") (pintype "passive"))
      (node (ref "CF8.1") (pin "5") (pinfunction "5_5") (pintype "passive"))
      (node (ref "CF8.1") (pin "6") (pinfunction "6_6") (pintype "passive"))
    )
    (net (code "4") (name "AUX-4") (class "Default")
      (node (ref "CF12.1") (pin "7") (pinfunction "7_7") (pintype "passive"))
      (node (ref "CF12.1") (pin "8") (pinfunction "8_8") (pintype "passive"))
      (node (ref "CF13.1") (pin "7") (pinfunction "7_7") (pintype "passive"))
      (node (ref "CF13.1") (pin "8") (pinfunction "8_8") (pintype "passive"))
      (node (ref "CF14.1") (pin "7") (pinfunction "7_7") (pintype "passive"))
      (node (ref "CF14.1") (pin "8") (pinfunction "8_8") (pintype "passive"))
      (node (ref "CF15.1") (pin "7") (pinfunction "7_7") (pintype "passive"))
      (node (ref "CF15.1") (pin "8") (pinfunction "8_8") (pintype "passive"))
      (node (ref "CF16.1") (pin "7") (pinfunction "7_7") (pintype "passive"))
      (node (ref "CF16.1") (pin "8") (pinfunction "8_8") (pintype "passive"))
      (node (ref "CF17.1") (pin "7") (pinfunction "7_7") (pintype "passive"))
      (node (ref "CF17.1") (pin "8") (pinfunction "8_8") (pintype "passive"))
      (node (ref "CF18.1") (pin "7") (pinfunction "7_7") (pintype "passive"))
      (node (ref "CF18.1") (pin "8") (pinfunction "8_8") (pintype "passive"))
      (node (ref "CF19.1") (pin "7") (pinfunction "7_7") (pintype "passive"))
      (node (ref "CF19.1") (pin "8") (pinfunction "8_8") (pintype "passive"))
      (node (ref "CF2.1") (pin "7") (pinfunction "7_7") (pintype "passive"))
      (node (ref "CF2.1") (pin "8") (pinfunction "8_8") (pintype "passive"))
      (node (ref "CF3.1") (pin "7") (pinfunction "7_7") (pintype "passive"))
      (node (ref "CF3.1") (pin "8") (pinfunction "8_8") (pintype "passive"))
      (node (ref "CF4.1") (pin "7") (pinfunction "7_7") (pintype "passive"))
      (node (ref "CF4.1") (pin "8") (pinfunction "8_8") (pintype "passive"))
      (node (ref "CF5.1") (pin "7") (pinfunction "7_7") (pintype "passive"))
      (node (ref "CF5.1") (pin "8") (pinfunction "8_8") (pintype "passive"))
      (node (ref "CF6.1") (pin "7") (pinfunction "7_7") (pintype "passive"))
      (node (ref "CF6.1") (pin "8") (pinfunction "8_8") (pintype "passive"))
      (node (ref "CF7.1") (pin "7") (pinfunction "7_7") (pintype "passive"))
      (node (ref "CF7.1") (pin "8") (pinfunction "8_8") (pintype "passive"))
      (node (ref "CF8.1") (pin "7") (pinfunction "7_7") (pintype "passive"))
      (node (ref "CF8.1") (pin "8") (pinfunction "8_8") (pintype "passive"))
    )
    (net (code "5") (name "AUX-5") (class "Default")
      (node (ref "CF12.1") (pin "10") (pinfunction "10_10") (pintype "passive"))
      (node (ref "CF12.1") (pin "9") (pinfunction "9_9") (pintype "passive"))
      (node (ref "CF13.1") (pin "10") (pinfunction "10_10") (pintype "passive"))
      (node (ref "CF13.1") (pin "9") (pinfunction "9_9") (pintype "passive"))
      (node (ref "CF14.1") (pin "10") (pinfunction "10_10") (pintype "passive"))
      (node (ref "CF14.1") (pin "9") (pinfunction "9_9") (pintype "passive"))
      (node (ref "CF15.1") (pin "10") (pinfunction "10_10") (pintype "passive"))
      (node (ref "CF15.1") (pin "9") (pinfunction "9_9") (pintype "passive"))
      (node (ref "CF16.1") (pin "10") (pinfunction "10_10") (pintype "passive"))
      (node (ref "CF16.1") (pin "9") (pinfunction "9_9") (pintype "passive"))
      (node (ref "CF17.1") (pin "10") (pinfunction "10_10") (pintype "passive"))
      (node (ref "CF17.1") (pin "9") (pinfunction "9_9") (pintype "passive"))
      (node (ref "CF18.1") (pin "10") (pinfunction "10_10") (pintype "passive"))
      (node (ref "CF18.1") (pin "9") (pinfunction "9_9") (pintype "passive"))
      (node (ref "CF19.1") (pin "10") (pinfunction "10_10") (pintype "passive"))
      (node (ref "CF19.1") (pin "9") (pinfunction "9_9") (pintype "passive"))
      (node (ref "CF2.1") (pin "10") (pinfunction "10_10") (pintype "passive"))
      (node (ref "CF2.1") (pin "9") (pinfunction "9_9") (pintype "passive"))
      (node (ref "CF3.1") (pin "10") (pinfunction "10_10") (pintype "passive"))
      (node (ref "CF3.1") (pin "9") (pinfunction "9_9") (pintype "passive"))
      (node (ref "CF4.1") (pin "10") (pinfunction "10_10") (pintype "passive"))
      (node (ref "CF4.1") (pin "9") (pinfunction "9_9") (pintype "passive"))
      (node (ref "CF5.1") (pin "10") (pinfunction "10_10") (pintype "passive"))
      (node (ref "CF5.1") (pin "9") (pinfunction "9_9") (pintype "passive"))
      (node (ref "CF6.1") (pin "10") (pinfunction "10_10") (pintype "passive"))
      (node (ref "CF6.1") (pin "9") (pinfunction "9_9") (pintype "passive"))
      (node (ref "CF7.1") (pin "10") (pinfunction "10_10") (pintype "passive"))
      (node (ref "CF7.1") (pin "9") (pinfunction "9_9") (pintype "passive"))
      (node (ref "CF8.1") (pin "10") (pinfunction "10_10") (pintype "passive"))
      (node (ref "CF8.1") (pin "9") (pinfunction "9_9") (pintype "passive"))
    )
    (net (code "6") (name "AUX-6") (class "Default")
      (node (ref "CF12.1") (pin "11") (pinfunction "11_11") (pintype "passive"))
      (node (ref "CF12.1") (pin "12") (pinfunction "12_12") (pintype "passive"))
      (node (ref "CF13.1") (pin "11") (pinfunction "11_11") (pintype "passive"))
      (node (ref "CF13.1") (pin "12") (pinfunction "12_12") (pintype "passive"))
      (node (ref "CF14.1") (pin "11") (pinfunction "11_11") (pintype "passive"))
      (node (ref "CF14.1") (pin "12") (pinfunction "12_12") (pintype "passive"))
      (node (ref "CF15.1") (pin "11") (pinfunction "11_11") (pintype "passive"))
      (node (ref "CF15.1") (pin "12") (pinfunction "12_12") (pintype "passive"))
      (node (ref "CF16.1") (pin "11") (pinfunction "11_11") (pintype "passive"))
      (node (ref "CF16.1") (pin "12") (pinfunction "12_12") (pintype "passive"))
      (node (ref "CF17.1") (pin "11") (pinfunction "11_11") (pintype "passive"))
      (node (ref "CF17.1") (pin "12") (pinfunction "12_12") (pintype "passive"))
      (node (ref "CF18.1") (pin "11") (pinfunction "11_11") (pintype "passive"))
      (node (ref "CF18.1") (pin "12") (pinfunction "12_12") (pintype "passive"))
      (node (ref "CF19.1") (pin "11") (pinfunction "11_11") (pintype "passive"))
      (node (ref "CF19.1") (pin "12") (pinfunction "12_12") (pintype "passive"))
      (node (ref "CF2.1") (pin "11") (pinfunction "11_11") (pintype "passive"))
      (node (ref "CF2.1") (pin "12") (pinfunction "12_12") (pintype "passive"))
      (node (ref "CF3.1") (pin "11") (pinfunction "11_11") (pintype "passive"))
      (node (ref "CF3.1") (pin "12") (pinfunction "12_12") (pintype "passive"))
      (node (ref "CF4.1") (pin "11") (pinfunction "11_11") (pintype "passive"))
      (node (ref "CF4.1") (pin "12") (pinfunction "12_12") (pintype "passive"))
      (node (ref "CF5.1") (pin "11") (pinfunction "11_11") (pintype "passive"))
      (node (ref "CF5.1") (pin "12") (pinfunction "12_12") (pintype "passive"))
      (node (ref "CF6.1") (pin "11") (pinfunction "11_11") (pintype "passive"))
      (node (ref "CF6.1") (pin "12") (pinfunction "12_12") (pintype "passive"))
      (node (ref "CF7.1") (pin "11") (pinfunction "11_11") (pintype "passive"))
      (node (ref "CF7.1") (pin "12") (pinfunction "12_12") (pintype "passive"))
      (node (ref "CF8.1") (pin "11") (pinfunction "11_11") (pintype "passive"))
      (node (ref "CF8.1") (pin "12") (pinfunction "12_12") (pintype "passive"))
    )
    (net (code "7") (name "AUX-7") (class "Default")
      (node (ref "CF12.1") (pin "13") (pinfunction "13_13") (pintype "passive"))
      (node (ref "CF12.1") (pin "14") (pinfunction "14_14") (pintype "passive"))
      (node (ref "CF13.1") (pin "13") (pinfunction "13_13") (pintype "passive"))
      (node (ref "CF13.1") (pin "14") (pinfunction "14_14") (pintype "passive"))
      (node (ref "CF14.1") (pin "13") (pinfunction "13_13") (pintype "passive"))
      (node (ref "CF14.1") (pin "14") (pinfunction "14_14") (pintype "passive"))
      (node (ref "CF15.1") (pin "13") (pinfunction "13_13") (pintype "passive"))
      (node (ref "CF15.1") (pin "14") (pinfunction "14_14") (pintype "passive"))
      (node (ref "CF16.1") (pin "13") (pinfunction "13_13") (pintype "passive"))
      (node (ref "CF16.1") (pin "14") (pinfunction "14_14") (pintype "passive"))
      (node (ref "CF17.1") (pin "13") (pinfunction "13_13") (pintype "passive"))
      (node (ref "CF17.1") (pin "14") (pinfunction "14_14") (pintype "passive"))
      (node (ref "CF18.1") (pin "13") (pinfunction "13_13") (pintype "passive"))
      (node (ref "CF18.1") (pin "14") (pinfunction "14_14") (pintype "passive"))
      (node (ref "CF19.1") (pin "13") (pinfunction "13_13") (pintype "passive"))
      (node (ref "CF19.1") (pin "14") (pinfunction "14_14") (pintype "passive"))
      (node (ref "CF2.1") (pin "13") (pinfunction "13_13") (pintype "passive"))
      (node (ref "CF2.1") (pin "14") (pinfunction "14_14") (pintype "passive"))
      (node (ref "CF3.1") (pin "13") (pinfunction "13_13") (pintype "passive"))
      (node (ref "CF3.1") (pin "14") (pinfunction "14_14") (pintype "passive"))
      (node (ref "CF4.1") (pin "13") (pinfunction "13_13") (pintype "passive"))
      (node (ref "CF4.1") (pin "14") (pinfunction "14_14") (pintype "passive"))
      (node (ref "CF5.1") (pin "13") (pinfunction "13_13") (pintype "passive"))
      (node (ref "CF5.1") (pin "14") (pinfunction "14_14") (pintype "passive"))
      (node (ref "CF6.1") (pin "13") (pinfunction "13_13") (pintype "passive"))
      (node (ref "CF6.1") (pin "14") (pinfunction "14_14") (pintype "passive"))
      (node (ref "CF7.1") (pin "13") (pinfunction "13_13") (pintype "passive"))
      (node (ref "CF7.1") (pin "14") (pinfunction "14_14") (pintype "passive"))
      (node (ref "CF8.1") (pin "13") (pinfunction "13_13") (pintype "passive"))
      (node (ref "CF8.1") (pin "14") (pinfunction "14_14") (pintype "passive"))
    )
    (net (code "8") (name "AUX-8") (class "Default")
      (node (ref "CF12.1") (pin "15") (pinfunction "15_15") (pintype "passive"))
      (node (ref "CF12.1") (pin "16") (pinfunction "16_16") (pintype "passive"))
      (node (ref "CF13.1") (pin "15") (pinfunction "15_15") (pintype "passive"))
      (node (ref "CF13.1") (pin "16") (pinfunction "16_16") (pintype "passive"))
      (node (ref "CF14.1") (pin "15") (pinfunction "15_15") (pintype "passive"))
      (node (ref "CF14.1") (pin "16") (pinfunction "16_16") (pintype "passive"))
      (node (ref "CF15.1") (pin "15") (pinfunction "15_15") (pintype "passive"))
      (node (ref "CF15.1") (pin "16") (pinfunction "16_16") (pintype "passive"))
      (node (ref "CF16.1") (pin "15") (pinfunction "15_15") (pintype "passive"))
      (node (ref "CF16.1") (pin "16") (pinfunction "16_16") (pintype "passive"))
      (node (ref "CF17.1") (pin "15") (pinfunction "15_15") (pintype "passive"))
      (node (ref "CF17.1") (pin "16") (pinfunction "16_16") (pintype "passive"))
      (node (ref "CF18.1") (pin "15") (pinfunction "15_15") (pintype "passive"))
      (node (ref "CF18.1") (pin "16") (pinfunction "16_16") (pintype "passive"))
      (node (ref "CF19.1") (pin "15") (pinfunction "15_15") (pintype "passive"))
      (node (ref "CF19.1") (pin "16") (pinfunction "16_16") (pintype "passive"))
      (node (ref "CF2.1") (pin "15") (pinfunction "15_15") (pintype "passive"))
      (node (ref "CF2.1") (pin "16") (pinfunction "16_16") (pintype "passive"))
      (node (ref "CF3.1") (pin "15") (pinfunction "15_15") (pintype "passive"))
      (node (ref "CF3.1") (pin "16") (pinfunction "16_16") (pintype "passive"))
      (node (ref "CF4.1") (pin "15") (pinfunction "15_15") (pintype "passive"))
      (node (ref "CF4.1") (pin "16") (pinfunction "16_16") (pintype "passive"))
      (node (ref "CF5.1") (pin "15") (pinfunction "15_15") (pintype "passive"))
      (node (ref "CF5.1") (pin "16") (pinfunction "16_16") (pintype "passive"))
      (node (ref "CF6.1") (pin "15") (pinfunction "15_15") (pintype "passive"))
      (node (ref "CF6.1") (pin "16") (pinfunction "16_16") (pintype "passive"))
      (node (ref "CF7.1") (pin "15") (pinfunction "15_15") (pintype "passive"))
      (node (ref "CF7.1") (pin "16") (pinfunction "16_16") (pintype "passive"))
      (node (ref "CF8.1") (pin "15") (pinfunction "15_15") (pintype "passive"))
      (node (ref "CF8.1") (pin "16") (pinfunction "16_16") (pintype "passive"))
    )
    (net (code "9") (name "AUX-9") (class "Default")
      (node (ref "CF12.1") (pin "17") (pinfunction "17_17") (pintype "passive"))
      (node (ref "CF12.1") (pin "18") (pinfunction "18_18") (pintype "passive"))
      (node (ref "CF13.1") (pin "17") (pinfunction "17_17") (pintype "passive"))
      (node (ref "CF13.1") (pin "18") (pinfunction "18_18") (pintype "passive"))
      (node (ref "CF14.1") (pin "17") (pinfunction "17_17") (pintype "passive"))
      (node (ref "CF14.1") (pin "18") (pinfunction "18_18") (pintype "passive"))
      (node (ref "CF15.1") (pin "17") (pinfunction "17_17") (pintype "passive"))
      (node (ref "CF15.1") (pin "18") (pinfunction "18_18") (pintype "passive"))
      (node (ref "CF16.1") (pin "17") (pinfunction "17_17") (pintype "passive"))
      (node (ref "CF16.1") (pin "18") (pinfunction "18_18") (pintype "passive"))
      (node (ref "CF17.1") (pin "17") (pinfunction "17_17") (pintype "passive"))
      (node (ref "CF17.1") (pin "18") (pinfunction "18_18") (pintype "passive"))
      (node (ref "CF18.1") (pin "17") (pinfunction "17_17") (pintype "passive"))
      (node (ref "CF18.1") (pin "18") (pinfunction "18_18") (pintype "passive"))
      (node (ref "CF19.1") (pin "17") (pinfunction "17_17") (pintype "passive"))
      (node (ref "CF19.1") (pin "18") (pinfunction "18_18") (pintype "passive"))
      (node (ref "CF2.1") (pin "17") (pinfunction "17_17") (pintype "passive"))
      (node (ref "CF2.1") (pin "18") (pinfunction "18_18") (pintype "passive"))
      (node (ref "CF3.1") (pin "17") (pinfunction "17_17") (pintype "passive"))
      (node (ref "CF3.1") (pin "18") (pinfunction "18_18") (pintype "passive"))
      (node (ref "CF4.1") (pin "17") (pinfunction "17_17") (pintype "passive"))
      (node (ref "CF4.1") (pin "18") (pinfunction "18_18") (pintype "passive"))
      (node (ref "CF5.1") (pin "17") (pinfunction "17_17") (pintype "passive"))
      (node (ref "CF5.1") (pin "18") (pinfunction "18_18") (pintype "passive"))
      (node (ref "CF6.1") (pin "17") (pinfunction "17_17") (pintype "passive"))
      (node (ref "CF6.1") (pin "18") (pinfunction "18_18") (pintype "passive"))
      (node (ref "CF7.1") (pin "17") (pinfunction "17_17") (pintype "passive"))
      (node (ref "CF7.1") (pin "18") (pinfunction "18_18") (pintype "passive"))
      (node (ref "CF8.1") (pin "17") (pinfunction "17_17") (pintype "passive"))
      (node (ref "CF8.1") (pin "18") (pinfunction "18_18") (pintype "passive"))
    )
    (net (code "10") (name "AUX-10") (class "Default")
      (node (ref "CF12.1") (pin "19") (pinfunction "19_19") (pintype "passive"))
      (node (ref "CF12.1") (pin "20") (pinfunction "20_20") (pintype "passive"))
      (node (ref "CF13.1") (pin "19") (pinfunction "19_19") (pintype "passive"))
      (node (ref "CF13.1") (pin "20") (pinfunction "20_20") (pintype "passive"))
      (node (ref "CF14.1") (pin "19") (pinfunction "19_19") (pintype "passive"))
      (node (ref "CF14.1") (pin "20") (pinfunction "20_20") (pintype "passive"))
      (node (ref "CF15.1") (pin "19") (pinfunction "19_19") (pintype "passive"))
      (node (ref "CF15.1") (pin "20") (pinfunction "20_20") (pintype "passive"))
      (node (ref "CF16.1") (pin "19") (pinfunction "19_19") (pintype "passive"))
      (node (ref "CF16.1") (pin "20") (pinfunction "20_20") (pintype "passive"))
      (node (ref "CF17.1") (pin "19") (pinfunction "19_19") (pintype "passive"))
      (node (ref "CF17.1") (pin "20") (pinfunction "20_20") (pintype "passive"))
      (node (ref "CF18.1") (pin "19") (pinfunction "19_19") (pintype "passive"))
      (node (ref "CF18.1") (pin "20") (pinfunction "20_20") (pintype "passive"))
      (node (ref "CF19.1") (pin "19") (pinfunction "19_19") (pintype "passive"))
      (node (ref "CF19.1") (pin "20") (pinfunction "20_20") (pintype "passive"))
      (node (ref "CF2.1") (pin "19") (pinfunction "19_19") (pintype "passive"))
      (node (ref "CF2.1") (pin "20") (pinfunction "20_20") (pintype "passive"))
      (node (ref "CF3.1") (pin "19") (pinfunction "19_19") (pintype "passive"))
      (node (ref "CF3.1") (pin "20") (pinfunction "20_20") (pintype "passive"))
      (node (ref "CF4.1") (pin "19") (pinfunction "19_19") (pintype "passive"))
      (node (ref "CF4.1") (pin "20") (pinfunction "20_20") (pintype "passive"))
      (node (ref "CF5.1") (pin "19") (pinfunction "19_19") (pintype "passive"))
      (node (ref "CF5.1") (pin "20") (pinfunction "20_20") (pintype "passive"))
      (node (ref "CF6.1") (pin "19") (pinfunction "19_19") (pintype "passive"))
      (node (ref "CF6.1") (pin "20") (pinfunction "20_20") (pintype "passive"))
      (node (ref "CF7.1") (pin "19") (pinfunction "19_19") (pintype "passive"))
      (node (ref "CF7.1") (pin "20") (pinfunction "20_20") (pintype "passive"))
      (node (ref "CF8.1") (pin "19") (pinfunction "19_19") (pintype "passive"))
      (node (ref "CF8.1") (pin "20") (pinfunction "20_20") (pintype "passive"))
    )
    (net (code "11") (name "CAN1_H") (class "Default")
      (node (ref "CF12.2") (pin "33") (pinfunction "33_33") (pintype "passive"))
      (node (ref "CF12.2") (pin "34") (pinfunction "34_34") (pintype "passive"))
      (node (ref "CF13.2") (pin "33") (pinfunction "33_33") (pintype "passive"))
      (node (ref "CF13.2") (pin "34") (pinfunction "34_34") (pintype "passive"))
      (node (ref "CF14.2") (pin "33") (pinfunction "33_33") (pintype "passive"))
      (node (ref "CF14.2") (pin "34") (pinfunction "34_34") (pintype "passive"))
      (node (ref "CF15.2") (pin "33") (pinfunction "33_33") (pintype "passive"))
      (node (ref "CF15.2") (pin "34") (pinfunction "34_34") (pintype "passive"))
      (node (ref "CF16.2") (pin "33") (pinfunction "33_33") (pintype "passive"))
      (node (ref "CF16.2") (pin "34") (pinfunction "34_34") (pintype "passive"))
      (node (ref "CF17.2") (pin "33") (pinfunction "33_33") (pintype "passive"))
      (node (ref "CF17.2") (pin "34") (pinfunction "34_34") (pintype "passive"))
      (node (ref "CF18.2") (pin "33") (pinfunction "33_33") (pintype "passive"))
      (node (ref "CF18.2") (pin "34") (pinfunction "34_34") (pintype "passive"))
      (node (ref "CF19.2") (pin "33") (pinfunction "33_33") (pintype "passive"))
      (node (ref "CF19.2") (pin "34") (pinfunction "34_34") (pintype "passive"))
      (node (ref "CF2.2") (pin "33") (pinfunction "33_33") (pintype "passive"))
      (node (ref "CF2.2") (pin "34") (pinfunction "34_34") (pintype "passive"))
      (node (ref "CF2.3") (pin "33") (pinfunction "33_33") (pintype "passive"))
      (node (ref "CF2.3") (pin "34") (pinfunction "34_34") (pintype "passive"))
      (node (ref "CF2.4") (pin "33") (pinfunction "33_33") (pintype "passive"))
      (node (ref "CF2.4") (pin "34") (pinfunction "34_34") (pintype "passive"))
      (node (ref "CF3.2") (pin "33") (pinfunction "33_33") (pintype "passive"))
      (node (ref "CF3.2") (pin "34") (pinfunction "34_34") (pintype "passive"))
      (node (ref "CF4.2") (pin "33") (pinfunction "33_33") (pintype "passive"))
      (node (ref "CF4.2") (pin "34") (pinfunction "34_34") (pintype "passive"))
      (node (ref "CF5.2") (pin "33") (pinfunction "33_33") (pintype "passive"))
      (node (ref "CF5.2") (pin "34") (pinfunction "34_34") (pintype "passive"))
      (node (ref "CF6.2") (pin "33") (pinfunction "33_33") (pintype "passive"))
      (node (ref "CF6.2") (pin "34") (pinfunction "34_34") (pintype "passive"))
      (node (ref "CF7.2") (pin "33") (pinfunction "33_33") (pintype "passive"))
      (node (ref "CF7.2") (pin "34") (pinfunction "34_34") (pintype "passive"))
      (node (ref "CF8.2") (pin "33") (pinfunction "33_33") (pintype "passive"))
      (node (ref "CF8.2") (pin "34") (pinfunction "34_34") (pintype "passive"))
      (node (ref "R1") (pin "1") (pinfunction "1_1") (pintype "passive"))
      (node (ref "R5") (pin "1") (pinfunction "1_1") (pintype "passive"))
    )
    (net (code "12") (name "CAN1_L") (class "Default")
      (node (ref "CF12.2") (pin "35") (pinfunction "35_35") (pintype "passive"))
      (node (ref "CF12.2") (pin "36") (pinfunction "36_36") (pintype "passive"))
      (node (ref "CF13.2") (pin "35") (pinfunction "35_35") (pintype "passive"))
      (node (ref "CF13.2") (pin "36") (pinfunction "36_36") (pintype "passive"))
      (node (ref "CF14.2") (pin "35") (pinfunction "35_35") (pintype "passive"))
      (node (ref "CF14.2") (pin "36") (pinfunction "36_36") (pintype "passive"))
      (node (ref "CF15.2") (pin "35") (pinfunction "35_35") (pintype "passive"))
      (node (ref "CF15.2") (pin "36") (pinfunction "36_36") (pintype "passive"))
      (node (ref "CF16.2") (pin "35") (pinfunction "35_35") (pintype "passive"))
      (node (ref "CF16.2") (pin "36") (pinfunction "36_36") (pintype "passive"))
      (node (ref "CF17.2") (pin "35") (pinfunction "35_35") (pintype "passive"))
      (node (ref "CF17.2") (pin "36") (pinfunction "36_36") (pintype "passive"))
      (node (ref "CF18.2") (pin "35") (pinfunction "35_35") (pintype "passive"))
      (node (ref "CF18.2") (pin "36") (pinfunction "36_36") (pintype "passive"))
      (node (ref "CF19.2") (pin "35") (pinfunction "35_35") (pintype "passive"))
      (node (ref "CF19.2") (pin "36") (pinfunction "36_36") (pintype "passive"))
      (node (ref "CF2.2") (pin "35") (pinfunction "35_35") (pintype "passive"))
      (node (ref "CF2.2") (pin "36") (pinfunction "36_36") (pintype "passive"))
      (node (ref "CF2.3") (pin "35") (pinfunction "35_35") (pintype "passive"))
      (node (ref "CF2.3") (pin "36") (pinfunction "36_36") (pintype "passive"))
      (node (ref "CF2.4") (pin "35") (pinfunction "35_35") (pintype "passive"))
      (node (ref "CF2.4") (pin "36") (pinfunction "36_36") (pintype "passive"))
      (node (ref "CF3.2") (pin "35") (pinfunction "35_35") (pintype "passive"))
      (node (ref "CF3.2") (pin "36") (pinfunction "36_36") (pintype "passive"))
      (node (ref "CF4.2") (pin "35") (pinfunction "35_35") (pintype "passive"))
      (node (ref "CF4.2") (pin "36") (pinfunction "36_36") (pintype "passive"))
      (node (ref "CF5.2") (pin "35") (pinfunction "35_35") (pintype "passive"))
      (node (ref "CF5.2") (pin "36") (pinfunction "36_36") (pintype "passive"))
      (node (ref "CF6.2") (pin "35") (pinfunction "35_35") (pintype "passive"))
      (node (ref "CF6.2") (pin "36") (pinfunction "36_36") (pintype "passive"))
      (node (ref "CF7.2") (pin "35") (pinfunction "35_35") (pintype "passive"))
      (node (ref "CF7.2") (pin "36") (pinfunction "36_36") (pintype "passive"))
      (node (ref "CF8.2") (pin "35") (pinfunction "35_35") (pintype "passive"))
      (node (ref "CF8.2") (pin "36") (pinfunction "36_36") (pintype "passive"))
      (node (ref "R2") (pin "1") (pinfunction "1_1") (pintype "passive"))
      (node (ref "R6") (pin "1") (pinfunction "1_1") (pintype "passive"))
    )
    (net (code "13") (name "CAN2_H") (class "Default")
      (node (ref "CF12.2") (pin "17") (pinfunction "17_17") (pintype "passive"))
      (node (ref "CF12.2") (pin "18") (pinfunction "18_18") (pintype "passive"))
      (node (ref "CF13.2") (pin "17") (pinfunction "17_17") (pintype "passive"))
      (node (ref "CF13.2") (pin "18") (pinfunction "18_18") (pintype "passive"))
      (node (ref "CF14.2") (pin "17") (pinfunction "17_17") (pintype "passive"))
      (node (ref "CF14.2") (pin "18") (pinfunction "18_18") (pintype "passive"))
      (node (ref "CF15.2") (pin "17") (pinfunction "17_17") (pintype "passive"))
      (node (ref "CF15.2") (pin "18") (pinfunction "18_18") (pintype "passive"))
      (node (ref "CF16.2") (pin "17") (pinfunction "17_17") (pintype "passive"))
      (node (ref "CF16.2") (pin "18") (pinfunction "18_18") (pintype "passive"))
      (node (ref "CF17.2") (pin "17") (pinfunction "17_17") (pintype "passive"))
      (node (ref "CF17.2") (pin "18") (pinfunction "18_18") (pintype "passive"))
      (node (ref "CF18.2") (pin "17") (pinfunction "17_17") (pintype "passive"))
      (node (ref "CF18.2") (pin "18") (pinfunction "18_18") (pintype "passive"))
      (node (ref "CF19.2") (pin "17") (pinfunction "17_17") (pintype "passive"))
      (node (ref "CF19.2") (pin "18") (pinfunction "18_18") (pintype "passive"))
      (node (ref "CF2.2") (pin "17") (pinfunction "17_17") (pintype "passive"))
      (node (ref "CF2.2") (pin "18") (pinfunction "18_18") (pintype "passive"))
      (node (ref "CF2.3") (pin "17") (pinfunction "17_17") (pintype "passive"))
      (node (ref "CF2.3") (pin "18") (pinfunction "18_18") (pintype "passive"))
      (node (ref "CF2.4") (pin "17") (pinfunction "17_17") (pintype "passive"))
      (node (ref "CF2.4") (pin "18") (pinfunction "18_18") (pintype "passive"))
      (node (ref "CF3.2") (pin "17") (pinfunction "17_17") (pintype "passive"))
      (node (ref "CF3.2") (pin "18") (pinfunction "18_18") (pintype "passive"))
      (node (ref "CF4.2") (pin "17") (pinfunction "17_17") (pintype "passive"))
      (node (ref "CF4.2") (pin "18") (pinfunction "18_18") (pintype "passive"))
      (node (ref "CF5.2") (pin "17") (pinfunction "17_17") (pintype "passive"))
      (node (ref "CF5.2") (pin "18") (pinfunction "18_18") (pintype "passive"))
      (node (ref "CF6.2") (pin "17") (pinfunction "17_17") (pintype "passive"))
      (node (ref "CF6.2") (pin "18") (pinfunction "18_18") (pintype "passive"))
      (node (ref "CF7.2") (pin "17") (pinfunction "17_17") (pintype "passive"))
      (node (ref "CF7.2") (pin "18") (pinfunction "18_18") (pintype "passive"))
      (node (ref "CF8.2") (pin "17") (pinfunction "17_17") (pintype "passive"))
      (node (ref "CF8.2") (pin "18") (pinfunction "18_18") (pintype "passive"))
      (node (ref "R3") (pin "1") (pinfunction "1_1") (pintype "passive"))
      (node (ref "R7") (pin "1") (pinfunction "1_1") (pintype "passive"))
    )
    (net (code "14") (name "CAN2_L") (class "Default")
      (node (ref "CF12.2") (pin "19") (pinfunction "19_19") (pintype "passive"))
      (node (ref "CF12.2") (pin "20") (pinfunction "20_20") (pintype "passive"))
      (node (ref "CF13.2") (pin "19") (pinfunction "19_19") (pintype "passive"))
      (node (ref "CF13.2") (pin "20") (pinfunction "20_20") (pintype "passive"))
      (node (ref "CF14.2") (pin "19") (pinfunction "19_19") (pintype "passive"))
      (node (ref "CF14.2") (pin "20") (pinfunction "20_20") (pintype "passive"))
      (node (ref "CF15.2") (pin "19") (pinfunction "19_19") (pintype "passive"))
      (node (ref "CF15.2") (pin "20") (pinfunction "20_20") (pintype "passive"))
      (node (ref "CF16.2") (pin "19") (pinfunction "19_19") (pintype "passive"))
      (node (ref "CF16.2") (pin "20") (pinfunction "20_20") (pintype "passive"))
      (node (ref "CF17.2") (pin "19") (pinfunction "19_19") (pintype "passive"))
      (node (ref "CF17.2") (pin "20") (pinfunction "20_20") (pintype "passive"))
      (node (ref "CF18.2") (pin "19") (pinfunction "19_19") (pintype "passive"))
      (node (ref "CF18.2") (pin "20") (pinfunction "20_20") (pintype "passive"))
      (node (ref "CF19.2") (pin "19") (pinfunction "19_19") (pintype "passive"))
      (node (ref "CF19.2") (pin "20") (pinfunction "20_20") (pintype "passive"))
      (node (ref "CF2.2") (pin "19") (pinfunction "19_19") (pintype "passive"))
      (node (ref "CF2.2") (pin "20") (pinfunction "20_20") (pintype "passive"))
      (node (ref "CF2.3") (pin "19") (pinfunction "19_19") (pintype "passive"))
      (node (ref "CF2.3") (pin "20") (pinfunction "20_20") (pintype "passive"))
      (node (ref "CF2.4") (pin "19") (pinfunction "19_19") (pintype "passive"))
      (node (ref "CF2.4") (pin "20") (pinfunction "20_20") (pintype "passive"))
      (node (ref "CF3.2") (pin "19") (pinfunction "19_19") (pintype "passive"))
      (node (ref "CF3.2") (pin "20") (pinfunction "20_20") (pintype "passive"))
      (node (ref "CF4.2") (pin "19") (pinfunction "19_19") (pintype "passive"))
      (node (ref "CF4.2") (pin "20") (pinfunction "20_20") (pintype "passive"))
      (node (ref "CF5.2") (pin "19") (pinfunction "19_19") (pintype "passive"))
      (node (ref "CF5.2") (pin "20") (pinfunction "20_20") (pintype "passive"))
      (node (ref "CF6.2") (pin "19") (pinfunction "19_19") (pintype "passive"))
      (node (ref "CF6.2") (pin "20") (pinfunction "20_20") (pintype "passive"))
      (node (ref "CF7.2") (pin "19") (pinfunction "19_19") (pintype "passive"))
      (node (ref "CF7.2") (pin "20") (pinfunction "20_20") (pintype "passive"))
      (node (ref "CF8.2") (pin "19") (pinfunction "19_19") (pintype "passive"))
      (node (ref "CF8.2") (pin "20") (pinfunction "20_20") (pintype "passive"))
      (node (ref "R4") (pin "1") (pinfunction "1_1") (pintype "passive"))
      (node (ref "R8") (pin "1") (pinfunction "1_1") (pintype "passive"))
    )
    (net (code "15") (name "GND") (class "Default")
      (node (ref "C1") (pin "2") (pinfunction "2_2") (pintype "passive"))
      (node (ref "C2") (pin "2") (pinfunction "2_2") (pintype "passive"))
      (node (ref "C3") (pin "2") (pinfunction "2_2") (pintype "passive"))
      (node (ref "C4") (pin "2") (pinfunction "2_2") (pintype "passive"))
      (node (ref "CF12.1") (pin "LC1") (pinfunction "LC1_LC1") (pintype "passive"))
      (node (ref "CF12.1") (pin "LC2") (pinfunction "LC2_LC2") (pintype "passive"))
      (node (ref "CF12.2") (pin "27") (pinfunction "27_27") (pintype "passive"))
      (node (ref "CF12.2") (pin "28") (pinfunction "28_28") (pintype "passive"))
      (node (ref "CF12.2") (pin "29") (pinfunction "29_29") (pintype "passive"))
      (node (ref "CF12.2") (pin "30") (pinfunction "30_30") (pintype "passive"))
      (node (ref "CF12.2") (pin "31") (pinfunction "31_31") (pintype "passive"))
      (node (ref "CF12.2") (pin "32") (pinfunction "32_32") (pintype "passive"))
      (node (ref "CF12.2") (pin "37") (pinfunction "37_37") (pintype "passive"))
      (node (ref "CF12.2") (pin "38") (pinfunction "38_38") (pintype "passive"))
      (node (ref "CF12.2") (pin "LC1") (pinfunction "LC1_LC1") (pintype "passive"))
      (node (ref "CF12.2") (pin "LC2") (pinfunction "LC2_LC2") (pintype "passive"))
      (node (ref "CF13.1") (pin "LC1") (pinfunction "LC1_LC1") (pintype "passive"))
      (node (ref "CF13.1") (pin "LC2") (pinfunction "LC2_LC2") (pintype "passive"))
      (node (ref "CF13.2") (pin "27") (pinfunction "27_27") (pintype "passive"))
      (node (ref "CF13.2") (pin "28") (pinfunction "28_28") (pintype "passive"))
      (node (ref "CF13.2") (pin "29") (pinfunction "29_29") (pintype "passive"))
      (node (ref "CF13.2") (pin "30") (pinfunction "30_30") (pintype "passive"))
      (node (ref "CF13.2") (pin "31") (pinfunction "31_31") (pintype "passive"))
      (node (ref "CF13.2") (pin "32") (pinfunction "32_32") (pintype "passive"))
      (node (ref "CF13.2") (pin "37") (pinfunction "37_37") (pintype "passive"))
      (node (ref "CF13.2") (pin "38") (pinfunction "38_38") (pintype "passive"))
      (node (ref "CF13.2") (pin "LC1") (pinfunction "LC1_LC1") (pintype "passive"))
      (node (ref "CF13.2") (pin "LC2") (pinfunction "LC2_LC2") (pintype "passive"))
      (node (ref "CF14.1") (pin "LC1") (pinfunction "LC1_LC1") (pintype "passive"))
      (node (ref "CF14.1") (pin "LC2") (pinfunction "LC2_LC2") (pintype "passive"))
      (node (ref "CF14.2") (pin "27") (pinfunction "27_27") (pintype "passive"))
      (node (ref "CF14.2") (pin "28") (pinfunction "28_28") (pintype "passive"))
      (node (ref "CF14.2") (pin "29") (pinfunction "29_29") (pintype "passive"))
      (node (ref "CF14.2") (pin "30") (pinfunction "30_30") (pintype "passive"))
      (node (ref "CF14.2") (pin "31") (pinfunction "31_31") (pintype "passive"))
      (node (ref "CF14.2") (pin "32") (pinfunction "32_32") (pintype "passive"))
      (node (ref "CF14.2") (pin "37") (pinfunction "37_37") (pintype "passive"))
      (node (ref "CF14.2") (pin "38") (pinfunction "38_38") (pintype "passive"))
      (node (ref "CF14.2") (pin "LC1") (pinfunction "LC1_LC1") (pintype "passive"))
      (node (ref "CF14.2") (pin "LC2") (pinfunction "LC2_LC2") (pintype "passive"))
      (node (ref "CF15.1") (pin "LC1") (pinfunction "LC1_LC1") (pintype "passive"))
      (node (ref "CF15.1") (pin "LC2") (pinfunction "LC2_LC2") (pintype "passive"))
      (node (ref "CF15.2") (pin "27") (pinfunction "27_27") (pintype "passive"))
      (node (ref "CF15.2") (pin "28") (pinfunction "28_28") (pintype "passive"))
      (node (ref "CF15.2") (pin "29") (pinfunction "29_29") (pintype "passive"))
      (node (ref "CF15.2") (pin "30") (pinfunction "30_30") (pintype "passive"))
      (node (ref "CF15.2") (pin "31") (pinfunction "31_31") (pintype "passive"))
      (node (ref "CF15.2") (pin "32") (pinfunction "32_32") (pintype "passive"))
      (node (ref "CF15.2") (pin "37") (pinfunction "37_37") (pintype "passive"))
      (node (ref "CF15.2") (pin "38") (pinfunction "38_38") (pintype "passive"))
      (node (ref "CF15.2") (pin "LC1") (pinfunction "LC1_LC1") (pintype "passive"))
      (node (ref "CF15.2") (pin "LC2") (pinfunction "LC2_LC2") (pintype "passive"))
      (node (ref "CF16.1") (pin "LC1") (pinfunction "LC1_LC1") (pintype "passive"))
      (node (ref "CF16.1") (pin "LC2") (pinfunction "LC2_LC2") (pintype "passive"))
      (node (ref "CF16.2") (pin "27") (pinfunction "27_27") (pintype "passive"))
      (node (ref "CF16.2") (pin "28") (pinfunction "28_28") (pintype "passive"))
      (node (ref "CF16.2") (pin "29") (pinfunction "29_29") (pintype "passive"))
      (node (ref "CF16.2") (pin "30") (pinfunction "30_30") (pintype "passive"))
      (node (ref "CF16.2") (pin "31") (pinfunction "31_31") (pintype "passive"))
      (node (ref "CF16.2") (pin "32") (pinfunction "32_32") (pintype "passive"))
      (node (ref "CF16.2") (pin "37") (pinfunction "37_37") (pintype "passive"))
      (node (ref "CF16.2") (pin "38") (pinfunction "38_38") (pintype "passive"))
      (node (ref "CF16.2") (pin "LC1") (pinfunction "LC1_LC1") (pintype "passive"))
      (node (ref "CF16.2") (pin "LC2") (pinfunction "LC2_LC2") (pintype "passive"))
      (node (ref "CF17.1") (pin "LC1") (pinfunction "LC1_LC1") (pintype "passive"))
      (node (ref "CF17.1") (pin "LC2") (pinfunction "LC2_LC2") (pintype "passive"))
      (node (ref "CF17.2") (pin "27") (pinfunction "27_27") (pintype "passive"))
      (node (ref "CF17.2") (pin "28") (pinfunction "28_28") (pintype "passive"))
      (node (ref "CF17.2") (pin "29") (pinfunction "29_29") (pintype "passive"))
      (node (ref "CF17.2") (pin "30") (pinfunction "30_30") (pintype "passive"))
      (node (ref "CF17.2") (pin "31") (pinfunction "31_31") (pintype "passive"))
      (node (ref "CF17.2") (pin "32") (pinfunction "32_32") (pintype "passive"))
      (node (ref "CF17.2") (pin "37") (pinfunction "37_37") (pintype "passive"))
      (node (ref "CF17.2") (pin "38") (pinfunction "38_38") (pintype "passive"))
      (node (ref "CF17.2") (pin "LC1") (pinfunction "LC1_LC1") (pintype "passive"))
      (node (ref "CF17.2") (pin "LC2") (pinfunction "LC2_LC2") (pintype "passive"))
      (node (ref "CF18.1") (pin "LC1") (pinfunction "LC1_LC1") (pintype "passive"))
      (node (ref "CF18.1") (pin "LC2") (pinfunction "LC2_LC2") (pintype "passive"))
      (node (ref "CF18.2") (pin "27") (pinfunction "27_27") (pintype "passive"))
      (node (ref "CF18.2") (pin "28") (pinfunction "28_28") (pintype "passive"))
      (node (ref "CF18.2") (pin "29") (pinfunction "29_29") (pintype "passive"))
      (node (ref "CF18.2") (pin "30") (pinfunction "30_30") (pintype "passive"))
      (node (ref "CF18.2") (pin "31") (pinfunction "31_31") (pintype "passive"))
      (node (ref "CF18.2") (pin "32") (pinfunction "32_32") (pintype "passive"))
      (node (ref "CF18.2") (pin "37") (pinfunction "37_37") (pintype "passive"))
      (node (ref "CF18.2") (pin "38") (pinfunction "38_38") (pintype "passive"))
      (node (ref "CF18.2") (pin "LC1") (pinfunction "LC1_LC1") (pintype "passive"))
      (node (ref "CF18.2") (pin "LC2") (pinfunction "LC2_LC2") (pintype "passive"))
      (node (ref "CF19.1") (pin "LC1") (pinfunction "LC1_LC1") (pintype "passive"))
      (node (ref "CF19.1") (pin "LC2") (pinfunction "LC2_LC2") (pintype "passive"))
      (node (ref "CF19.2") (pin "27") (pinfunction "27_27") (pintype "passive"))
      (node (ref "CF19.2") (pin "28") (pinfunction "28_28") (pintype "passive"))
      (node (ref "CF19.2") (pin "29") (pinfunction "29_29") (pintype "passive"))
      (node (ref "CF19.2") (pin "30") (pinfunction "30_30") (pintype "passive"))
      (node (ref "CF19.2") (pin "31") (pinfunction "31_31") (pintype "passive"))
      (node (ref "CF19.2") (pin "32") (pinfunction "32_32") (pintype "passive"))
      (node (ref "CF19.2") (pin "37") (pinfunction "37_37") (pintype "passive"))
      (node (ref "CF19.2") (pin "38") (pinfunction "38_38") (pintype "passive"))
      (node (ref "CF19.2") (pin "LC1") (pinfunction "LC1_LC1") (pintype "passive"))
      (node (ref "CF19.2") (pin "LC2") (pinfunction "LC2_LC2") (pintype "passive"))
      (node (ref "CF2.1") (pin "LC1") (pinfunction "LC1_LC1") (pintype "passive"))
      (node (ref "CF2.1") (pin "LC2") (pinfunction "LC2_LC2") (pintype "passive"))
      (node (ref "CF2.2") (pin "27") (pinfunction "27_27") (pintype "passive"))
      (node (ref "CF2.2") (pin "28") (pinfunction "28_28") (pintype "passive"))
      (node (ref "CF2.2") (pin "29") (pinfunction "29_29") (pintype "passive"))
      (node (ref "CF2.2") (pin "30") (pinfunction "30_30") (pintype "passive"))
      (node (ref "CF2.2") (pin "31") (pinfunction "31_31") (pintype "passive"))
      (node (ref "CF2.2") (pin "32") (pinfunction "32_32") (pintype "passive"))
      (node (ref "CF2.2") (pin "37") (pinfunction "37_37") (pintype "passive"))
      (node (ref "CF2.2") (pin "38") (pinfunction "38_38") (pintype "passive"))
      (node (ref "CF2.2") (pin "LC1") (pinfunction "LC1_LC1") (pintype "passive"))
      (node (ref "CF2.2") (pin "LC2") (pinfunction "LC2_LC2") (pintype "passive"))
      (node (ref "CF2.3") (pin "27") (pinfunction "27_27") (pintype "passive"))
      (node (ref "CF2.3") (pin "28") (pinfunction "28_28") (pintype "passive"))
      (node (ref "CF2.3") (pin "29") (pinfunction "29_29") (pintype "passive"))
      (node (ref "CF2.3") (pin "30") (pinfunction "30_30") (pintype "passive"))
      (node (ref "CF2.3") (pin "31") (pinfunction "31_31") (pintype "passive"))
      (node (ref "CF2.3") (pin "32") (pinfunction "32_32") (pintype "passive"))
      (node (ref "CF2.3") (pin "37") (pinfunction "37_37") (pintype "passive"))
      (node (ref "CF2.3") (pin "38") (pinfunction "38_38") (pintype "passive"))
      (node (ref "CF2.3") (pin "LC1") (pinfunction "LC1_LC1") (pintype "passive"))
      (node (ref "CF2.3") (pin "LC2") (pinfunction "LC2_LC2") (pintype "passive"))
      (node (ref "CF2.4") (pin "27") (pinfunction "27_27") (pintype "passive"))
      (node (ref "CF2.4") (pin "28") (pinfunction "28_28") (pintype "passive"))
      (node (ref "CF2.4") (pin "29") (pinfunction "29_29") (pintype "passive"))
      (node (ref "CF2.4") (pin "30") (pinfunction "30_30") (pintype "passive"))
      (node (ref "CF2.4") (pin "31") (pinfunction "31_31") (pintype "passive"))
      (node (ref "CF2.4") (pin "32") (pinfunction "32_32") (pintype "passive"))
      (node (ref "CF2.4") (pin "37") (pinfunction "37_37") (pintype "passive"))
      (node (ref "CF2.4") (pin "38") (pinfunction "38_38") (pintype "passive"))
      (node (ref "CF2.4") (pin "LC1") (pinfunction "LC1_LC1") (pintype "passive"))
      (node (ref "CF2.4") (pin "LC2") (pinfunction "LC2_LC2") (pintype "passive"))
      (node (ref "CF3.1") (pin "LC1") (pinfunction "LC1_LC1") (pintype "passive"))
      (node (ref "CF3.1") (pin "LC2") (pinfunction "LC2_LC2") (pintype "passive"))
      (node (ref "CF3.2") (pin "27") (pinfunction "27_27") (pintype "passive"))
      (node (ref "CF3.2") (pin "28") (pinfunction "28_28") (pintype "passive"))
      (node (ref "CF3.2") (pin "29") (pinfunction "29_29") (pintype "passive"))
      (node (ref "CF3.2") (pin "30") (pinfunction "30_30") (pintype "passive"))
      (node (ref "CF3.2") (pin "31") (pinfunction "31_31") (pintype "passive"))
      (node (ref "CF3.2") (pin "32") (pinfunction "32_32") (pintype "passive"))
      (node (ref "CF3.2") (pin "37") (pinfunction "37_37") (pintype "passive"))
      (node (ref "CF3.2") (pin "38") (pinfunction "38_38") (pintype "passive"))
      (node (ref "CF3.2") (pin "LC1") (pinfunction "LC1_LC1") (pintype "passive"))
      (node (ref "CF3.2") (pin "LC2") (pinfunction "LC2_LC2") (pintype "passive"))
      (node (ref "CF4.1") (pin "LC1") (pinfunction "LC1_LC1") (pintype "passive"))
      (node (ref "CF4.1") (pin "LC2") (pinfunction "LC2_LC2") (pintype "passive"))
      (node (ref "CF4.2") (pin "27") (pinfunction "27_27") (pintype "passive"))
      (node (ref "CF4.2") (pin "28") (pinfunction "28_28") (pintype "passive"))
      (node (ref "CF4.2") (pin "29") (pinfunction "29_29") (pintype "passive"))
      (node (ref "CF4.2") (pin "30") (pinfunction "30_30") (pintype "passive"))
      (node (ref "CF4.2") (pin "31") (pinfunction "31_31") (pintype "passive"))
      (node (ref "CF4.2") (pin "32") (pinfunction "32_32") (pintype "passive"))
      (node (ref "CF4.2") (pin "37") (pinfunction "37_37") (pintype "passive"))
      (node (ref "CF4.2") (pin "38") (pinfunction "38_38") (pintype "passive"))
      (node (ref "CF4.2") (pin "LC1") (pinfunction "LC1_LC1") (pintype "passive"))
      (node (ref "CF4.2") (pin "LC2") (pinfunction "LC2_LC2") (pintype "passive"))
      (node (ref "CF5.1") (pin "LC1") (pinfunction "LC1_LC1") (pintype "passive"))
      (node (ref "CF5.1") (pin "LC2") (pinfunction "LC2_LC2") (pintype "passive"))
      (node (ref "CF5.2") (pin "27") (pinfunction "27_27") (pintype "passive"))
      (node (ref "CF5.2") (pin "28") (pinfunction "28_28") (pintype "passive"))
      (node (ref "CF5.2") (pin "29") (pinfunction "29_29") (pintype "passive"))
      (node (ref "CF5.2") (pin "30") (pinfunction "30_30") (pintype "passive"))
      (node (ref "CF5.2") (pin "31") (pinfunction "31_31") (pintype "passive"))
      (node (ref "CF5.2") (pin "32") (pinfunction "32_32") (pintype "passive"))
      (node (ref "CF5.2") (pin "37") (pinfunction "37_37") (pintype "passive"))
      (node (ref "CF5.2") (pin "38") (pinfunction "38_38") (pintype "passive"))
      (node (ref "CF5.2") (pin "LC1") (pinfunction "LC1_LC1") (pintype "passive"))
      (node (ref "CF5.2") (pin "LC2") (pinfunction "LC2_LC2") (pintype "passive"))
      (node (ref "CF6.1") (pin "LC1") (pinfunction "LC1_LC1") (pintype "passive"))
      (node (ref "CF6.1") (pin "LC2") (pinfunction "LC2_LC2") (pintype "passive"))
      (node (ref "CF6.2") (pin "27") (pinfunction "27_27") (pintype "passive"))
      (node (ref "CF6.2") (pin "28") (pinfunction "28_28") (pintype "passive"))
      (node (ref "CF6.2") (pin "29") (pinfunction "29_29") (pintype "passive"))
      (node (ref "CF6.2") (pin "30") (pinfunction "30_30") (pintype "passive"))
      (node (ref "CF6.2") (pin "31") (pinfunction "31_31") (pintype "passive"))
      (node (ref "CF6.2") (pin "32") (pinfunction "32_32") (pintype "passive"))
      (node (ref "CF6.2") (pin "37") (pinfunction "37_37") (pintype "passive"))
      (node (ref "CF6.2") (pin "38") (pinfunction "38_38") (pintype "passive"))
      (node (ref "CF6.2") (pin "LC1") (pinfunction "LC1_LC1") (pintype "passive"))
      (node (ref "CF6.2") (pin "LC2") (pinfunction "LC2_LC2") (pintype "passive"))
      (node (ref "CF7.1") (pin "LC1") (pinfunction "LC1_LC1") (pintype "passive"))
      (node (ref "CF7.1") (pin "LC2") (pinfunction "LC2_LC2") (pintype "passive"))
      (node (ref "CF7.2") (pin "27") (pinfunction "27_27") (pintype "passive"))
      (node (ref "CF7.2") (pin "28") (pinfunction "28_28") (pintype "passive"))
      (node (ref "CF7.2") (pin "29") (pinfunction "29_29") (pintype "passive"))
      (node (ref "CF7.2") (pin "30") (pinfunction "30_30") (pintype "passive"))
      (node (ref "CF7.2") (pin "31") (pinfunction "31_31") (pintype "passive"))
      (node (ref "CF7.2") (pin "32") (pinfunction "32_32") (pintype "passive"))
      (node (ref "CF7.2") (pin "37") (pinfunction "37_37") (pintype "passive"))
      (node (ref "CF7.2") (pin "38") (pinfunction "38_38") (pintype "passive"))
      (node (ref "CF7.2") (pin "LC1") (pinfunction "LC1_LC1") (pintype "passive"))
      (node (ref "CF7.2") (pin "LC2") (pinfunction "LC2_LC2") (pintype "passive"))
      (node (ref "CF8.1") (pin "LC1") (pinfunction "LC1_LC1") (pintype "passive"))
      (node (ref "CF8.1") (pin "LC2") (pinfunction "LC2_LC2") (pintype "passive"))
      (node (ref "CF8.2") (pin "27") (pinfunction "27_27") (pintype "passive"))
      (node (ref "CF8.2") (pin "28") (pinfunction "28_28") (pintype "passive"))
      (node (ref "CF8.2") (pin "29") (pinfunction "29_29") (pintype "passive"))
      (node (ref "CF8.2") (pin "30") (pinfunction "30_30") (pintype "passive"))
      (node (ref "CF8.2") (pin "31") (pinfunction "31_31") (pintype "passive"))
      (node (ref "CF8.2") (pin "32") (pinfunction "32_32") (pintype "passive"))
      (node (ref "CF8.2") (pin "37") (pinfunction "37_37") (pintype "passive"))
      (node (ref "CF8.2") (pin "38") (pinfunction "38_38") (pintype "passive"))
      (node (ref "CF8.2") (pin "LC1") (pinfunction "LC1_LC1") (pintype "passive"))
      (node (ref "CF8.2") (pin "LC2") (pinfunction "LC2_LC2") (pintype "passive"))
      (node (ref "CM1.1") (pin "P$1") (pinfunction "SHIELD1_P$1") (pintype "passive"))
      (node (ref "CM1.1") (pin "P$2") (pinfunction "SHIELD1_P$2") (pintype "passive"))
      (node (ref "CM1.1") (pin "P$3") (pinfunction "SHIELD1_P$3") (pintype "passive"))
      (node (ref "CM1.1") (pin "P$4") (pinfunction "SHIELD1_P$4") (pintype "passive"))
      (node (ref "CM2.1") (pin "P$1") (pinfunction "SHIELD1_P$1") (pintype "passive"))
      (node (ref "CM2.1") (pin "P$2") (pinfunction "SHIELD1_P$2") (pintype "passive"))
      (node (ref "CM2.1") (pin "P$3") (pinfunction "SHIELD1_P$3") (pintype "passive"))
      (node (ref "CM2.1") (pin "P$4") (pinfunction "SHIELD1_P$4") (pintype "passive"))
      (node (ref "CM2.2") (pin "P$1") (pinfunction "SHIELD1_P$1") (pintype "passive"))
      (node (ref "CM2.2") (pin "P$2") (pinfunction "SHIELD1_P$2") (pintype "passive"))
      (node (ref "CM2.2") (pin "P$3") (pinfunction "SHIELD1_P$3") (pintype "passive"))
      (node (ref "CM2.2") (pin "P$4") (pinfunction "SHIELD1_P$4") (pintype "passive"))
      (node (ref "CM20.1") (pin "P$1") (pinfunction "SHIELD1_P$1") (pintype "passive"))
      (node (ref "CM20.1") (pin "P$2") (pinfunction "SHIELD1_P$2") (pintype "passive"))
      (node (ref "CM20.1") (pin "P$3") (pinfunction "SHIELD1_P$3") (pintype "passive"))
      (node (ref "CM20.1") (pin "P$4") (pinfunction "SHIELD1_P$4") (pintype "passive"))
      (node (ref "CM20.2") (pin "P$1") (pinfunction "SHIELD1_P$1") (pintype "passive"))
      (node (ref "CM20.2") (pin "P$2") (pinfunction "SHIELD1_P$2") (pintype "passive"))
      (node (ref "CM20.2") (pin "P$3") (pinfunction "SHIELD1_P$3") (pintype "passive"))
      (node (ref "CM20.2") (pin "P$4") (pinfunction "SHIELD1_P$4") (pintype "passive"))
      (node (ref "CM20.3") (pin "P$1") (pinfunction "SHIELD1_P$1") (pintype "passive"))
      (node (ref "CM20.3") (pin "P$2") (pinfunction "SHIELD1_P$2") (pintype "passive"))
      (node (ref "CM20.3") (pin "P$3") (pinfunction "SHIELD1_P$3") (pintype "passive"))
      (node (ref "CM20.3") (pin "P$4") (pinfunction "SHIELD1_P$4") (pintype "passive"))
      (node (ref "CM20.4") (pin "P$1") (pinfunction "SHIELD1_P$1") (pintype "passive"))
      (node (ref "CM20.4") (pin "P$2") (pinfunction "SHIELD1_P$2") (pintype "passive"))
      (node (ref "CM20.4") (pin "P$3") (pinfunction "SHIELD1_P$3") (pintype "passive"))
      (node (ref "CM20.4") (pin "P$4") (pinfunction "SHIELD1_P$4") (pintype "passive"))
      (node (ref "CM20.5") (pin "P$1") (pinfunction "SHIELD1_P$1") (pintype "passive"))
      (node (ref "CM20.5") (pin "P$2") (pinfunction "SHIELD1_P$2") (pintype "passive"))
      (node (ref "CM20.5") (pin "P$3") (pinfunction "SHIELD1_P$3") (pintype "passive"))
      (node (ref "CM20.5") (pin "P$4") (pinfunction "SHIELD1_P$4") (pintype "passive"))
      (node (ref "CM20.6") (pin "P$1") (pinfunction "SHIELD1_P$1") (pintype "passive"))
      (node (ref "CM20.6") (pin "P$2") (pinfunction "SHIELD1_P$2") (pintype "passive"))
      (node (ref "CM20.6") (pin "P$3") (pinfunction "SHIELD1_P$3") (pintype "passive"))
      (node (ref "CM20.6") (pin "P$4") (pinfunction "SHIELD1_P$4") (pintype "passive"))
      (node (ref "CM20.7") (pin "P$1") (pinfunction "SHIELD1_P$1") (pintype "passive"))
      (node (ref "CM20.7") (pin "P$2") (pinfunction "SHIELD1_P$2") (pintype "passive"))
      (node (ref "CM20.7") (pin "P$3") (pinfunction "SHIELD1_P$3") (pintype "passive"))
      (node (ref "CM20.7") (pin "P$4") (pinfunction "SHIELD1_P$4") (pintype "passive"))
    )
    (net (code "16") (name "L-GPS") (class "Default")
      (node (ref "CM20.4") (pin "RF-DOWN") (pinfunction "RF_RF-DOWN") (pintype "passive"))
      (node (ref "CM20.7") (pin "RF-DOWN") (pinfunction "RF_RF-DOWN") (pintype "passive"))
    )
    (net (code "17") (name "L-TURNSTILE") (class "Default")
      (node (ref "CM20.2") (pin "RF-DOWN") (pinfunction "RF_RF-DOWN") (pintype "passive"))
      (node (ref "CM20.5") (pin "RF-DOWN") (pinfunction "RF_RF-DOWN") (pintype "passive"))
    )
    (net (code "18") (name "Net-(C1-Pad1)") (class "Default")
      (node (ref "C1") (pin "1") (pinfunction "1_1") (pintype "passive"))
      (node (ref "R1") (pin "2") (pinfunction "2_2") (pintype "passive"))
      (node (ref "R2") (pin "2") (pinfunction "2_2") (pintype "passive"))
    )
    (net (code "19") (name "Net-(C2-Pad1)") (class "Default")
      (node (ref "C2") (pin "1") (pinfunction "1_1") (pintype "passive"))
      (node (ref "R3") (pin "2") (pinfunction "2_2") (pintype "passive"))
      (node (ref "R4") (pin "2") (pinfunction "2_2") (pintype "passive"))
    )
    (net (code "20") (name "Net-(C3-Pad1)") (class "Default")
      (node (ref "C3") (pin "1") (pinfunction "1_1") (pintype "passive"))
      (node (ref "R5") (pin "2") (pinfunction "2_2") (pintype "passive"))
      (node (ref "R6") (pin "2") (pinfunction "2_2") (pintype "passive"))
    )
    (net (code "21") (name "Net-(C4-Pad1)") (class "Default")
      (node (ref "C4") (pin "1") (pinfunction "1_1") (pintype "passive"))
      (node (ref "R7") (pin "2") (pinfunction "2_2") (pintype "passive"))
      (node (ref "R8") (pin "2") (pinfunction "2_2") (pintype "passive"))
    )
    (net (code "22") (name "OPD_PWR") (class "Default")
      (node (ref "CF12.2") (pin "15") (pinfunction "15_15") (pintype "passive"))
      (node (ref "CF12.2") (pin "16") (pinfunction "16_16") (pintype "passive"))
      (node (ref "CF13.2") (pin "15") (pinfunction "15_15") (pintype "passive"))
      (node (ref "CF13.2") (pin "16") (pinfunction "16_16") (pintype "passive"))
      (node (ref "CF14.2") (pin "15") (pinfunction "15_15") (pintype "passive"))
      (node (ref "CF14.2") (pin "16") (pinfunction "16_16") (pintype "passive"))
      (node (ref "CF15.2") (pin "15") (pinfunction "15_15") (pintype "passive"))
      (node (ref "CF15.2") (pin "16") (pinfunction "16_16") (pintype "passive"))
      (node (ref "CF16.2") (pin "15") (pinfunction "15_15") (pintype "passive"))
      (node (ref "CF16.2") (pin "16") (pinfunction "16_16") (pintype "passive"))
      (node (ref "CF17.2") (pin "15") (pinfunction "15_15") (pintype "passive"))
      (node (ref "CF17.2") (pin "16") (pinfunction "16_16") (pintype "passive"))
      (node (ref "CF18.2") (pin "15") (pinfunction "15_15") (pintype "passive"))
      (node (ref "CF18.2") (pin "16") (pinfunction "16_16") (pintype "passive"))
      (node (ref "CF19.2") (pin "15") (pinfunction "15_15") (pintype "passive"))
      (node (ref "CF19.2") (pin "16") (pinfunction "16_16") (pintype "passive"))
      (node (ref "CF2.2") (pin "15") (pinfunction "15_15") (pintype "passive"))
      (node (ref "CF2.2") (pin "16") (pinfunction "16_16") (pintype "passive"))
      (node (ref "CF2.3") (pin "15") (pinfunction "15_15") (pintype "passive"))
      (node (ref "CF2.3") (pin "16") (pinfunction "16_16") (pintype "passive"))
      (node (ref "CF2.4") (pin "15") (pinfunction "15_15") (pintype "passive"))
      (node (ref "CF2.4") (pin "16") (pinfunction "16_16") (pintype "passive"))
      (node (ref "CF3.2") (pin "15") (pinfunction "15_15") (pintype "passive"))
      (node (ref "CF3.2") (pin "16") (pinfunction "16_16") (pintype "passive"))
      (node (ref "CF4.2") (pin "15") (pinfunction "15_15") (pintype "passive"))
      (node (ref "CF4.2") (pin "16") (pinfunction "16_16") (pintype "passive"))
      (node (ref "CF5.2") (pin "15") (pinfunction "15_15") (pintype "passive"))
      (node (ref "CF5.2") (pin "16") (pinfunction "16_16") (pintype "passive"))
      (node (ref "CF6.2") (pin "15") (pinfunction "15_15") (pintype "passive"))
      (node (ref "CF6.2") (pin "16") (pinfunction "16_16") (pintype "passive"))
      (node (ref "CF7.2") (pin "15") (pinfunction "15_15") (pintype "passive"))
      (node (ref "CF7.2") (pin "16") (pinfunction "16_16") (pintype "passive"))
      (node (ref "CF8.2") (pin "15") (pinfunction "15_15") (pintype "passive"))
      (node (ref "CF8.2") (pin "16") (pinfunction "16_16") (pintype "passive"))
    )
    (net (code "23") (name "OPD_SCL") (class "Default")
      (node (ref "CF12.2") (pin "13") (pinfunction "13_13") (pintype "passive"))
      (node (ref "CF12.2") (pin "14") (pinfunction "14_14") (pintype "passive"))
      (node (ref "CF13.2") (pin "13") (pinfunction "13_13") (pintype "passive"))
      (node (ref "CF13.2") (pin "14") (pinfunction "14_14") (pintype "passive"))
      (node (ref "CF14.2") (pin "13") (pinfunction "13_13") (pintype "passive"))
      (node (ref "CF14.2") (pin "14") (pinfunction "14_14") (pintype "passive"))
      (node (ref "CF15.2") (pin "13") (pinfunction "13_13") (pintype "passive"))
      (node (ref "CF15.2") (pin "14") (pinfunction "14_14") (pintype "passive"))
      (node (ref "CF16.2") (pin "13") (pinfunction "13_13") (pintype "passive"))
      (node (ref "CF16.2") (pin "14") (pinfunction "14_14") (pintype "passive"))
      (node (ref "CF17.2") (pin "13") (pinfunction "13_13") (pintype "passive"))
      (node (ref "CF17.2") (pin "14") (pinfunction "14_14") (pintype "passive"))
      (node (ref "CF18.2") (pin "13") (pinfunction "13_13") (pintype "passive"))
      (node (ref "CF18.2") (pin "14") (pinfunction "14_14") (pintype "passive"))
      (node (ref "CF19.2") (pin "13") (pinfunction "13_13") (pintype "passive"))
      (node (ref "CF19.2") (pin "14") (pinfunction "14_14") (pintype "passive"))
      (node (ref "CF2.2") (pin "13") (pinfunction "13_13") (pintype "passive"))
      (node (ref "CF2.2") (pin "14") (pinfunction "14_14") (pintype "passive"))
      (node (ref "CF2.3") (pin "13") (pinfunction "13_13") (pintype "passive"))
      (node (ref "CF2.3") (pin "14") (pinfunction "14_14") (pintype "passive"))
      (node (ref "CF2.4") (pin "13") (pinfunction "13_13") (pintype "passive"))
      (node (ref "CF2.4") (pin "14") (pinfunction "14_14") (pintype "passive"))
      (node (ref "CF3.2") (pin "13") (pinfunction "13_13") (pintype "passive"))
      (node (ref "CF3.2") (pin "14") (pinfunction "14_14") (pintype "passive"))
      (node (ref "CF4.2") (pin "13") (pinfunction "13_13") (pintype "passive"))
      (node (ref "CF4.2") (pin "14") (pinfunction "14_14") (pintype "passive"))
      (node (ref "CF5.2") (pin "13") (pinfunction "13_13") (pintype "passive"))
      (node (ref "CF5.2") (pin "14") (pinfunction "14_14") (pintype "passive"))
      (node (ref "CF6.2") (pin "13") (pinfunction "13_13") (pintype "passive"))
      (node (ref "CF6.2") (pin "14") (pinfunction "14_14") (pintype "passive"))
      (node (ref "CF7.2") (pin "13") (pinfunction "13_13") (pintype "passive"))
      (node (ref "CF7.2") (pin "14") (pinfunction "14_14") (pintype "passive"))
      (node (ref "CF8.2") (pin "13") (pinfunction "13_13") (pintype "passive"))
      (node (ref "CF8.2") (pin "14") (pinfunction "14_14") (pintype "passive"))
    )
    (net (code "24") (name "OPD_SDA") (class "Default")
      (node (ref "CF12.2") (pin "11") (pinfunction "11_11") (pintype "passive"))
      (node (ref "CF12.2") (pin "12") (pinfunction "12_12") (pintype "passive"))
      (node (ref "CF13.2") (pin "11") (pinfunction "11_11") (pintype "passive"))
      (node (ref "CF13.2") (pin "12") (pinfunction "12_12") (pintype "passive"))
      (node (ref "CF14.2") (pin "11") (pinfunction "11_11") (pintype "passive"))
      (node (ref "CF14.2") (pin "12") (pinfunction "12_12") (pintype "passive"))
      (node (ref "CF15.2") (pin "11") (pinfunction "11_11") (pintype "passive"))
      (node (ref "CF15.2") (pin "12") (pinfunction "12_12") (pintype "passive"))
      (node (ref "CF16.2") (pin "11") (pinfunction "11_11") (pintype "passive"))
      (node (ref "CF16.2") (pin "12") (pinfunction "12_12") (pintype "passive"))
      (node (ref "CF17.2") (pin "11") (pinfunction "11_11") (pintype "passive"))
      (node (ref "CF17.2") (pin "12") (pinfunction "12_12") (pintype "passive"))
      (node (ref "CF18.2") (pin "11") (pinfunction "11_11") (pintype "passive"))
      (node (ref "CF18.2") (pin "12") (pinfunction "12_12") (pintype "passive"))
      (node (ref "CF19.2") (pin "11") (pinfunction "11_11") (pintype "passive"))
      (node (ref "CF19.2") (pin "12") (pinfunction "12_12") (pintype "passive"))
      (node (ref "CF2.2") (pin "11") (pinfunction "11_11") (pintype "passive"))
      (node (ref "CF2.2") (pin "12") (pinfunction "12_12") (pintype "passive"))
      (node (ref "CF2.3") (pin "11") (pinfunction "11_11") (pintype "passive"))
      (node (ref "CF2.3") (pin "12") (pinfunction "12_12") (pintype "passive"))
      (node (ref "CF2.4") (pin "11") (pinfunction "11_11") (pintype "passive"))
      (node (ref "CF2.4") (pin "12") (pinfunction "12_12") (pintype "passive"))
      (node (ref "CF3.2") (pin "11") (pinfunction "11_11") (pintype "passive"))
      (node (ref "CF3.2") (pin "12") (pinfunction "12_12") (pintype "passive"))
      (node (ref "CF4.2") (pin "11") (pinfunction "11_11") (pintype "passive"))
      (node (ref "CF4.2") (pin "12") (pinfunction "12_12") (pintype "passive"))
      (node (ref "CF5.2") (pin "11") (pinfunction "11_11") (pintype "passive"))
      (node (ref "CF5.2") (pin "12") (pinfunction "12_12") (pintype "passive"))
      (node (ref "CF6.2") (pin "11") (pinfunction "11_11") (pintype "passive"))
      (node (ref "CF6.2") (pin "12") (pinfunction "12_12") (pintype "passive"))
      (node (ref "CF7.2") (pin "11") (pinfunction "11_11") (pintype "passive"))
      (node (ref "CF7.2") (pin "12") (pinfunction "12_12") (pintype "passive"))
      (node (ref "CF8.2") (pin "11") (pinfunction "11_11") (pintype "passive"))
      (node (ref "CF8.2") (pin "12") (pinfunction "12_12") (pintype "passive"))
    )
    (net (code "25") (name "S-HELICAL") (class "Default")
      (node (ref "CM1.1") (pin "RF-DOWN") (pinfunction "RF_RF-DOWN") (pintype "passive"))
      (node (ref "CM2.1") (pin "RF-DOWN") (pinfunction "RF_RF-DOWN") (pintype "passive"))
    )
    (net (code "26") (name "S-TURNSTILE") (class "Default")
      (node (ref "CM2.2") (pin "RF-DOWN") (pinfunction "RF_RF-DOWN") (pintype "passive"))
      (node (ref "CM20.3") (pin "RF-DOWN") (pinfunction "RF_RF-DOWN") (pintype "passive"))
    )
    (net (code "27") (name "SPARE1") (class "Default")
      (node (ref "CF12.2") (pin "10") (pinfunction "10_10") (pintype "passive"))
      (node (ref "CF12.2") (pin "9") (pinfunction "9_9") (pintype "passive"))
      (node (ref "CF13.2") (pin "10") (pinfunction "10_10") (pintype "passive"))
      (node (ref "CF13.2") (pin "9") (pinfunction "9_9") (pintype "passive"))
      (node (ref "CF14.2") (pin "10") (pinfunction "10_10") (pintype "passive"))
      (node (ref "CF14.2") (pin "9") (pinfunction "9_9") (pintype "passive"))
      (node (ref "CF15.2") (pin "10") (pinfunction "10_10") (pintype "passive"))
      (node (ref "CF15.2") (pin "9") (pinfunction "9_9") (pintype "passive"))
      (node (ref "CF16.2") (pin "10") (pinfunction "10_10") (pintype "passive"))
      (node (ref "CF16.2") (pin "9") (pinfunction "9_9") (pintype "passive"))
      (node (ref "CF17.2") (pin "10") (pinfunction "10_10") (pintype "passive"))
      (node (ref "CF17.2") (pin "9") (pinfunction "9_9") (pintype "passive"))
      (node (ref "CF18.2") (pin "10") (pinfunction "10_10") (pintype "passive"))
      (node (ref "CF18.2") (pin "9") (pinfunction "9_9") (pintype "passive"))
      (node (ref "CF19.2") (pin "10") (pinfunction "10_10") (pintype "passive"))
      (node (ref "CF19.2") (pin "9") (pinfunction "9_9") (pintype "passive"))
      (node (ref "CF2.2") (pin "10") (pinfunction "10_10") (pintype "passive"))
      (node (ref "CF2.2") (pin "9") (pinfunction "9_9") (pintype "passive"))
      (node (ref "CF2.3") (pin "10") (pinfunction "10_10") (pintype "passive"))
      (node (ref "CF2.3") (pin "9") (pinfunction "9_9") (pintype "passive"))
      (node (ref "CF2.4") (pin "10") (pinfunction "10_10") (pintype "passive"))
      (node (ref "CF2.4") (pin "9") (pinfunction "9_9") (pintype "passive"))
      (node (ref "CF3.2") (pin "10") (pinfunction "10_10") (pintype "passive"))
      (node (ref "CF3.2") (pin "9") (pinfunction "9_9") (pintype "passive"))
      (node (ref "CF4.2") (pin "10") (pinfunction "10_10") (pintype "passive"))
      (node (ref "CF4.2") (pin "9") (pinfunction "9_9") (pintype "passive"))
      (node (ref "CF5.2") (pin "10") (pinfunction "10_10") (pintype "passive"))
      (node (ref "CF5.2") (pin "9") (pinfunction "9_9") (pintype "passive"))
      (node (ref "CF6.2") (pin "10") (pinfunction "10_10") (pintype "passive"))
      (node (ref "CF6.2") (pin "9") (pinfunction "9_9") (pintype "passive"))
      (node (ref "CF7.2") (pin "10") (pinfunction "10_10") (pintype "passive"))
      (node (ref "CF7.2") (pin "9") (pinfunction "9_9") (pintype "passive"))
      (node (ref "CF8.2") (pin "10") (pinfunction "10_10") (pintype "passive"))
      (node (ref "CF8.2") (pin "9") (pinfunction "9_9") (pintype "passive"))
    )
    (net (code "28") (name "SPARE2") (class "Default")
      (node (ref "CF12.2") (pin "7") (pinfunction "7_7") (pintype "passive"))
      (node (ref "CF12.2") (pin "8") (pinfunction "8_8") (pintype "passive"))
      (node (ref "CF13.2") (pin "7") (pinfunction "7_7") (pintype "passive"))
      (node (ref "CF13.2") (pin "8") (pinfunction "8_8") (pintype "passive"))
      (node (ref "CF14.2") (pin "7") (pinfunction "7_7") (pintype "passive"))
      (node (ref "CF14.2") (pin "8") (pinfunction "8_8") (pintype "passive"))
      (node (ref "CF15.2") (pin "7") (pinfunction "7_7") (pintype "passive"))
      (node (ref "CF15.2") (pin "8") (pinfunction "8_8") (pintype "passive"))
      (node (ref "CF16.2") (pin "7") (pinfunction "7_7") (pintype "passive"))
      (node (ref "CF16.2") (pin "8") (pinfunction "8_8") (pintype "passive"))
      (node (ref "CF17.2") (pin "7") (pinfunction "7_7") (pintype "passive"))
      (node (ref "CF17.2") (pin "8") (pinfunction "8_8") (pintype "passive"))
      (node (ref "CF18.2") (pin "7") (pinfunction "7_7") (pintype "passive"))
      (node (ref "CF18.2") (pin "8") (pinfunction "8_8") (pintype "passive"))
      (node (ref "CF19.2") (pin "7") (pinfunction "7_7") (pintype "passive"))
      (node (ref "CF19.2") (pin "8") (pinfunction "8_8") (pintype "passive"))
      (node (ref "CF2.2") (pin "7") (pinfunction "7_7") (pintype "passive"))
      (node (ref "CF2.2") (pin "8") (pinfunction "8_8") (pintype "passive"))
      (node (ref "CF2.3") (pin "7") (pinfunction "7_7") (pintype "passive"))
      (node (ref "CF2.3") (pin "8") (pinfunction "8_8") (pintype "passive"))
      (node (ref "CF2.4") (pin "7") (pinfunction "7_7") (pintype "passive"))
      (node (ref "CF2.4") (pin "8") (pinfunction "8_8") (pintype "passive"))
      (node (ref "CF3.2") (pin "7") (pinfunction "7_7") (pintype "passive"))
      (node (ref "CF3.2") (pin "8") (pinfunction "8_8") (pintype "passive"))
      (node (ref "CF4.2") (pin "7") (pinfunction "7_7") (pintype "passive"))
      (node (ref "CF4.2") (pin "8") (pinfunction "8_8") (pintype "passive"))
      (node (ref "CF5.2") (pin "7") (pinfunction "7_7") (pintype "passive"))
      (node (ref "CF5.2") (pin "8") (pinfunction "8_8") (pintype "passive"))
      (node (ref "CF6.2") (pin "7") (pinfunction "7_7") (pintype "passive"))
      (node (ref "CF6.2") (pin "8") (pinfunction "8_8") (pintype "passive"))
      (node (ref "CF7.2") (pin "7") (pinfunction "7_7") (pintype "passive"))
      (node (ref "CF7.2") (pin "8") (pinfunction "8_8") (pintype "passive"))
      (node (ref "CF8.2") (pin "7") (pinfunction "7_7") (pintype "passive"))
      (node (ref "CF8.2") (pin "8") (pinfunction "8_8") (pintype "passive"))
    )
    (net (code "29") (name "SPARE3") (class "Default")
      (node (ref "CF12.2") (pin "5") (pinfunction "5_5") (pintype "passive"))
      (node (ref "CF12.2") (pin "6") (pinfunction "6_6") (pintype "passive"))
      (node (ref "CF13.2") (pin "5") (pinfunction "5_5") (pintype "passive"))
      (node (ref "CF13.2") (pin "6") (pinfunction "6_6") (pintype "passive"))
      (node (ref "CF14.2") (pin "5") (pinfunction "5_5") (pintype "passive"))
      (node (ref "CF14.2") (pin "6") (pinfunction "6_6") (pintype "passive"))
      (node (ref "CF15.2") (pin "5") (pinfunction "5_5") (pintype "passive"))
      (node (ref "CF15.2") (pin "6") (pinfunction "6_6") (pintype "passive"))
      (node (ref "CF16.2") (pin "5") (pinfunction "5_5") (pintype "passive"))
      (node (ref "CF16.2") (pin "6") (pinfunction "6_6") (pintype "passive"))
      (node (ref "CF17.2") (pin "5") (pinfunction "5_5") (pintype "passive"))
      (node (ref "CF17.2") (pin "6") (pinfunction "6_6") (pintype "passive"))
      (node (ref "CF18.2") (pin "5") (pinfunction "5_5") (pintype "passive"))
      (node (ref "CF18.2") (pin "6") (pinfunction "6_6") (pintype "passive"))
      (node (ref "CF19.2") (pin "5") (pinfunction "5_5") (pintype "passive"))
      (node (ref "CF19.2") (pin "6") (pinfunction "6_6") (pintype "passive"))
      (node (ref "CF2.2") (pin "5") (pinfunction "5_5") (pintype "passive"))
      (node (ref "CF2.2") (pin "6") (pinfunction "6_6") (pintype "passive"))
      (node (ref "CF2.3") (pin "5") (pinfunction "5_5") (pintype "passive"))
      (node (ref "CF2.3") (pin "6") (pinfunction "6_6") (pintype "passive"))
      (node (ref "CF2.4") (pin "5") (pinfunction "5_5") (pintype "passive"))
      (node (ref "CF2.4") (pin "6") (pinfunction "6_6") (pintype "passive"))
      (node (ref "CF3.2") (pin "5") (pinfunction "5_5") (pintype "passive"))
      (node (ref "CF3.2") (pin "6") (pinfunction "6_6") (pintype "passive"))
      (node (ref "CF4.2") (pin "5") (pinfunction "5_5") (pintype "passive"))
      (node (ref "CF4.2") (pin "6") (pinfunction "6_6") (pintype "passive"))
      (node (ref "CF5.2") (pin "5") (pinfunction "5_5") (pintype "passive"))
      (node (ref "CF5.2") (pin "6") (pinfunction "6_6") (pintype "passive"))
      (node (ref "CF6.2") (pin "5") (pinfunction "5_5") (pintype "passive"))
      (node (ref "CF6.2") (pin "6") (pinfunction "6_6") (pintype "passive"))
      (node (ref "CF7.2") (pin "5") (pinfunction "5_5") (pintype "passive"))
      (node (ref "CF7.2") (pin "6") (pinfunction "6_6") (pintype "passive"))
      (node (ref "CF8.2") (pin "5") (pinfunction "5_5") (pintype "passive"))
      (node (ref "CF8.2") (pin "6") (pinfunction "6_6") (pintype "passive"))
    )
    (net (code "30") (name "SPARE4") (class "Default")
      (node (ref "CF12.2") (pin "3") (pinfunction "3_3") (pintype "passive"))
      (node (ref "CF12.2") (pin "4") (pinfunction "4_4") (pintype "passive"))
      (node (ref "CF13.2") (pin "3") (pinfunction "3_3") (pintype "passive"))
      (node (ref "CF13.2") (pin "4") (pinfunction "4_4") (pintype "passive"))
      (node (ref "CF14.2") (pin "3") (pinfunction "3_3") (pintype "passive"))
      (node (ref "CF14.2") (pin "4") (pinfunction "4_4") (pintype "passive"))
      (node (ref "CF15.2") (pin "3") (pinfunction "3_3") (pintype "passive"))
      (node (ref "CF15.2") (pin "4") (pinfunction "4_4") (pintype "passive"))
      (node (ref "CF16.2") (pin "3") (pinfunction "3_3") (pintype "passive"))
      (node (ref "CF16.2") (pin "4") (pinfunction "4_4") (pintype "passive"))
      (node (ref "CF17.2") (pin "3") (pinfunction "3_3") (pintype "passive"))
      (node (ref "CF17.2") (pin "4") (pinfunction "4_4") (pintype "passive"))
      (node (ref "CF18.2") (pin "3") (pinfunction "3_3") (pintype "passive"))
      (node (ref "CF18.2") (pin "4") (pinfunction "4_4") (pintype "passive"))
      (node (ref "CF19.2") (pin "3") (pinfunction "3_3") (pintype "passive"))
      (node (ref "CF19.2") (pin "4") (pinfunction "4_4") (pintype "passive"))
      (node (ref "CF2.2") (pin "3") (pinfunction "3_3") (pintype "passive"))
      (node (ref "CF2.2") (pin "4") (pinfunction "4_4") (pintype "passive"))
      (node (ref "CF2.3") (pin "3") (pinfunction "3_3") (pintype "passive"))
      (node (ref "CF2.3") (pin "4") (pinfunction "4_4") (pintype "passive"))
      (node (ref "CF2.4") (pin "3") (pinfunction "3_3") (pintype "passive"))
      (node (ref "CF2.4") (pin "4") (pinfunction "4_4") (pintype "passive"))
      (node (ref "CF3.2") (pin "3") (pinfunction "3_3") (pintype "passive"))
      (node (ref "CF3.2") (pin "4") (pinfunction "4_4") (pintype "passive"))
      (node (ref "CF4.2") (pin "3") (pinfunction "3_3") (pintype "passive"))
      (node (ref "CF4.2") (pin "4") (pinfunction "4_4") (pintype "passive"))
      (node (ref "CF5.2") (pin "3") (pinfunction "3_3") (pintype "passive"))
      (node (ref "CF5.2") (pin "4") (pinfunction "4_4") (pintype "passive"))
      (node (ref "CF6.2") (pin "3") (pinfunction "3_3") (pintype "passive"))
      (node (ref "CF6.2") (pin "4") (pinfunction "4_4") (pintype "passive"))
      (node (ref "CF7.2") (pin "3") (pinfunction "3_3") (pintype "passive"))
      (node (ref "CF7.2") (pin "4") (pinfunction "4_4") (pintype "passive"))
      (node (ref "CF8.2") (pin "3") (pinfunction "3_3") (pintype "passive"))
      (node (ref "CF8.2") (pin "4") (pinfunction "4_4") (pintype "passive"))
    )
    (net (code "31") (name "SPARE5") (class "Default")
      (node (ref "CF12.2") (pin "1") (pinfunction "1_1") (pintype "passive"))
      (node (ref "CF12.2") (pin "2") (pinfunction "2_2") (pintype "passive"))
      (node (ref "CF13.2") (pin "1") (pinfunction "1_1") (pintype "passive"))
      (node (ref "CF13.2") (pin "2") (pinfunction "2_2") (pintype "passive"))
      (node (ref "CF14.2") (pin "1") (pinfunction "1_1") (pintype "passive"))
      (node (ref "CF14.2") (pin "2") (pinfunction "2_2") (pintype "passive"))
      (node (ref "CF15.2") (pin "1") (pinfunction "1_1") (pintype "passive"))
      (node (ref "CF15.2") (pin "2") (pinfunction "2_2") (pintype "passive"))
      (node (ref "CF16.2") (pin "1") (pinfunction "1_1") (pintype "passive"))
      (node (ref "CF16.2") (pin "2") (pinfunction "2_2") (pintype "passive"))
      (node (ref "CF17.2") (pin "1") (pinfunction "1_1") (pintype "passive"))
      (node (ref "CF17.2") (pin "2") (pinfunction "2_2") (pintype "passive"))
      (node (ref "CF18.2") (pin "1") (pinfunction "1_1") (pintype "passive"))
      (node (ref "CF18.2") (pin "2") (pinfunction "2_2") (pintype "passive"))
      (node (ref "CF19.2") (pin "1") (pinfunction "1_1") (pintype "passive"))
      (node (ref "CF19.2") (pin "2") (pinfunction "2_2") (pintype "passive"))
      (node (ref "CF2.2") (pin "1") (pinfunction "1_1") (pintype "passive"))
      (node (ref "CF2.2") (pin "2") (pinfunction "2_2") (pintype "passive"))
      (node (ref "CF2.3") (pin "1") (pinfunction "1_1") (pintype "passive"))
      (node (ref "CF2.3") (pin "2") (pinfunction "2_2") (pintype "passive"))
      (node (ref "CF2.4") (pin "1") (pinfunction "1_1") (pintype "passive"))
      (node (ref "CF2.4") (pin "2") (pinfunction "2_2") (pintype "passive"))
      (node (ref "CF3.2") (pin "1") (pinfunction "1_1") (pintype "passive"))
      (node (ref "CF3.2") (pin "2") (pinfunction "2_2") (pintype "passive"))
      (node (ref "CF4.2") (pin "1") (pinfunction "1_1") (pintype "passive"))
      (node (ref "CF4.2") (pin "2") (pinfunction "2_2") (pintype "passive"))
      (node (ref "CF5.2") (pin "1") (pinfunction "1_1") (pintype "passive"))
      (node (ref "CF5.2") (pin "2") (pinfunction "2_2") (pintype "passive"))
      (node (ref "CF6.2") (pin "1") (pinfunction "1_1") (pintype "passive"))
      (node (ref "CF6.2") (pin "2") (pinfunction "2_2") (pintype "passive"))
      (node (ref "CF7.2") (pin "1") (pinfunction "1_1") (pintype "passive"))
      (node (ref "CF7.2") (pin "2") (pinfunction "2_2") (pintype "passive"))
      (node (ref "CF8.2") (pin "1") (pinfunction "1_1") (pintype "passive"))
      (node (ref "CF8.2") (pin "2") (pinfunction "2_2") (pintype "passive"))
    )
    (net (code "32") (name "VBUS") (class "Default")
      (node (ref "CF12.2") (pin "21") (pinfunction "21_21") (pintype "passive"))
      (node (ref "CF12.2") (pin "22") (pinfunction "22_22") (pintype "passive"))
      (node (ref "CF12.2") (pin "23") (pinfunction "23_23") (pintype "passive"))
      (node (ref "CF12.2") (pin "24") (pinfunction "24_24") (pintype "passive"))
      (node (ref "CF12.2") (pin "25") (pinfunction "25_25") (pintype "passive"))
      (node (ref "CF12.2") (pin "26") (pinfunction "26_26") (pintype "passive"))
      (node (ref "CF13.2") (pin "21") (pinfunction "21_21") (pintype "passive"))
      (node (ref "CF13.2") (pin "22") (pinfunction "22_22") (pintype "passive"))
      (node (ref "CF13.2") (pin "23") (pinfunction "23_23") (pintype "passive"))
      (node (ref "CF13.2") (pin "24") (pinfunction "24_24") (pintype "passive"))
      (node (ref "CF13.2") (pin "25") (pinfunction "25_25") (pintype "passive"))
      (node (ref "CF13.2") (pin "26") (pinfunction "26_26") (pintype "passive"))
      (node (ref "CF14.2") (pin "21") (pinfunction "21_21") (pintype "passive"))
      (node (ref "CF14.2") (pin "22") (pinfunction "22_22") (pintype "passive"))
      (node (ref "CF14.2") (pin "23") (pinfunction "23_23") (pintype "passive"))
      (node (ref "CF14.2") (pin "24") (pinfunction "24_24") (pintype "passive"))
      (node (ref "CF14.2") (pin "25") (pinfunction "25_25") (pintype "passive"))
      (node (ref "CF14.2") (pin "26") (pinfunction "26_26") (pintype "passive"))
      (node (ref "CF15.2") (pin "21") (pinfunction "21_21") (pintype "passive"))
      (node (ref "CF15.2") (pin "22") (pinfunction "22_22") (pintype "passive"))
      (node (ref "CF15.2") (pin "23") (pinfunction "23_23") (pintype "passive"))
      (node (ref "CF15.2") (pin "24") (pinfunction "24_24") (pintype "passive"))
      (node (ref "CF15.2") (pin "25") (pinfunction "25_25") (pintype "passive"))
      (node (ref "CF15.2") (pin "26") (pinfunction "26_26") (pintype "passive"))
      (node (ref "CF16.2") (pin "21") (pinfunction "21_21") (pintype "passive"))
      (node (ref "CF16.2") (pin "22") (pinfunction "22_22") (pintype "passive"))
      (node (ref "CF16.2") (pin "23") (pinfunction "23_23") (pintype "passive"))
      (node (ref "CF16.2") (pin "24") (pinfunction "24_24") (pintype "passive"))
      (node (ref "CF16.2") (pin "25") (pinfunction "25_25") (pintype "passive"))
      (node (ref "CF16.2") (pin "26") (pinfunction "26_26") (pintype "passive"))
      (node (ref "CF17.2") (pin "21") (pinfunction "21_21") (pintype "passive"))
      (node (ref "CF17.2") (pin "22") (pinfunction "22_22") (pintype "passive"))
      (node (ref "CF17.2") (pin "23") (pinfunction "23_23") (pintype "passive"))
      (node (ref "CF17.2") (pin "24") (pinfunction "24_24") (pintype "passive"))
      (node (ref "CF17.2") (pin "25") (pinfunction "25_25") (pintype "passive"))
      (node (ref "CF17.2") (pin "26") (pinfunction "26_26") (pintype "passive"))
      (node (ref "CF18.2") (pin "21") (pinfunction "21_21") (pintype "passive"))
      (node (ref "CF18.2") (pin "22") (pinfunction "22_22") (pintype "passive"))
      (node (ref "CF18.2") (pin "23") (pinfunction "23_23") (pintype "passive"))
      (node (ref "CF18.2") (pin "24") (pinfunction "24_24") (pintype "passive"))
      (node (ref "CF18.2") (pin "25") (pinfunction "25_25") (pintype "passive"))
      (node (ref "CF18.2") (pin "26") (pinfunction "26_26") (pintype "passive"))
      (node (ref "CF19.2") (pin "21") (pinfunction "21_21") (pintype "passive"))
      (node (ref "CF19.2") (pin "22") (pinfunction "22_22") (pintype "passive"))
      (node (ref "CF19.2") (pin "23") (pinfunction "23_23") (pintype "passive"))
      (node (ref "CF19.2") (pin "24") (pinfunction "24_24") (pintype "passive"))
      (node (ref "CF19.2") (pin "25") (pinfunction "25_25") (pintype "passive"))
      (node (ref "CF19.2") (pin "26") (pinfunction "26_26") (pintype "passive"))
      (node (ref "CF2.2") (pin "21") (pinfunction "21_21") (pintype "passive"))
      (node (ref "CF2.2") (pin "22") (pinfunction "22_22") (pintype "passive"))
      (node (ref "CF2.2") (pin "23") (pinfunction "23_23") (pintype "passive"))
      (node (ref "CF2.2") (pin "24") (pinfunction "24_24") (pintype "passive"))
      (node (ref "CF2.2") (pin "25") (pinfunction "25_25") (pintype "passive"))
      (node (ref "CF2.2") (pin "26") (pinfunction "26_26") (pintype "passive"))
      (node (ref "CF2.3") (pin "21") (pinfunction "21_21") (pintype "passive"))
      (node (ref "CF2.3") (pin "22") (pinfunction "22_22") (pintype "passive"))
      (node (ref "CF2.3") (pin "23") (pinfunction "23_23") (pintype "passive"))
      (node (ref "CF2.3") (pin "24") (pinfunction "24_24") (pintype "passive"))
      (node (ref "CF2.3") (pin "25") (pinfunction "25_25") (pintype "passive"))
      (node (ref "CF2.3") (pin "26") (pinfunction "26_26") (pintype "passive"))
      (node (ref "CF2.4") (pin "21") (pinfunction "21_21") (pintype "passive"))
      (node (ref "CF2.4") (pin "22") (pinfunction "22_22") (pintype "passive"))
      (node (ref "CF2.4") (pin "23") (pinfunction "23_23") (pintype "passive"))
      (node (ref "CF2.4") (pin "24") (pinfunction "24_24") (pintype "passive"))
      (node (ref "CF2.4") (pin "25") (pinfunction "25_25") (pintype "passive"))
      (node (ref "CF2.4") (pin "26") (pinfunction "26_26") (pintype "passive"))
      (node (ref "CF3.2") (pin "21") (pinfunction "21_21") (pintype "passive"))
      (node (ref "CF3.2") (pin "22") (pinfunction "22_22") (pintype "passive"))
      (node (ref "CF3.2") (pin "23") (pinfunction "23_23") (pintype "passive"))
      (node (ref "CF3.2") (pin "24") (pinfunction "24_24") (pintype "passive"))
      (node (ref "CF3.2") (pin "25") (pinfunction "25_25") (pintype "passive"))
      (node (ref "CF3.2") (pin "26") (pinfunction "26_26") (pintype "passive"))
      (node (ref "CF4.2") (pin "21") (pinfunction "21_21") (pintype "passive"))
      (node (ref "CF4.2") (pin "22") (pinfunction "22_22") (pintype "passive"))
      (node (ref "CF4.2") (pin "23") (pinfunction "23_23") (pintype "passive"))
      (node (ref "CF4.2") (pin "24") (pinfunction "24_24") (pintype "passive"))
      (node (ref "CF4.2") (pin "25") (pinfunction "25_25") (pintype "passive"))
      (node (ref "CF4.2") (pin "26") (pinfunction "26_26") (pintype "passive"))
      (node (ref "CF5.2") (pin "21") (pinfunction "21_21") (pintype "passive"))
      (node (ref "CF5.2") (pin "22") (pinfunction "22_22") (pintype "passive"))
      (node (ref "CF5.2") (pin "23") (pinfunction "23_23") (pintype "passive"))
      (node (ref "CF5.2") (pin "24") (pinfunction "24_24") (pintype "passive"))
      (node (ref "CF5.2") (pin "25") (pinfunction "25_25") (pintype "passive"))
      (node (ref "CF5.2") (pin "26") (pinfunction "26_26") (pintype "passive"))
      (node (ref "CF6.2") (pin "21") (pinfunction "21_21") (pintype "passive"))
      (node (ref "CF6.2") (pin "22") (pinfunction "22_22") (pintype "passive"))
      (node (ref "CF6.2") (pin "23") (pinfunction "23_23") (pintype "passive"))
      (node (ref "CF6.2") (pin "24") (pinfunction "24_24") (pintype "passive"))
      (node (ref "CF6.2") (pin "25") (pinfunction "25_25") (pintype "passive"))
      (node (ref "CF6.2") (pin "26") (pinfunction "26_26") (pintype "passive"))
      (node (ref "CF7.2") (pin "21") (pinfunction "21_21") (pintype "passive"))
      (node (ref "CF7.2") (pin "22") (pinfunction "22_22") (pintype "passive"))
      (node (ref "CF7.2") (pin "23") (pinfunction "23_23") (pintype "passive"))
      (node (ref "CF7.2") (pin "24") (pinfunction "24_24") (pintype "passive"))
      (node (ref "CF7.2") (pin "25") (pinfunction "25_25") (pintype "passive"))
      (node (ref "CF7.2") (pin "26") (pinfunction "26_26") (pintype "passive"))
      (node (ref "CF8.2") (pin "21") (pinfunction "21_21") (pintype "passive"))
      (node (ref "CF8.2") (pin "22") (pinfunction "22_22") (pintype "passive"))
      (node (ref "CF8.2") (pin "23") (pinfunction "23_23") (pintype "passive"))
      (node (ref "CF8.2") (pin "24") (pinfunction "24_24") (pintype "passive"))
      (node (ref "CF8.2") (pin "25") (pinfunction "25_25") (pintype "passive"))
      (node (ref "CF8.2") (pin "26") (pinfunction "26_26") (pintype "passive"))
    )
    (net (code "33") (name "VHF-TURNSTILE") (class "Default")
      (node (ref "CM20.1") (pin "RF-DOWN") (pinfunction "RF_RF-DOWN") (pintype "passive"))
      (node (ref "CM20.6") (pin "RF-DOWN") (pinfunction "RF_RF-DOWN") (pintype "passive"))
    )
    (net (code "34") (name "~{SD}") (class "Default")
      (node (ref "CF12.2") (pin "39") (pinfunction "39_39") (pintype "passive"))
      (node (ref "CF12.2") (pin "40") (pinfunction "40_40") (pintype "passive"))
      (node (ref "CF13.2") (pin "39") (pinfunction "39_39") (pintype "passive"))
      (node (ref "CF13.2") (pin "40") (pinfunction "40_40") (pintype "passive"))
      (node (ref "CF14.2") (pin "39") (pinfunction "39_39") (pintype "passive"))
      (node (ref "CF14.2") (pin "40") (pinfunction "40_40") (pintype "passive"))
      (node (ref "CF15.2") (pin "39") (pinfunction "39_39") (pintype "passive"))
      (node (ref "CF15.2") (pin "40") (pinfunction "40_40") (pintype "passive"))
      (node (ref "CF16.2") (pin "39") (pinfunction "39_39") (pintype "passive"))
      (node (ref "CF16.2") (pin "40") (pinfunction "40_40") (pintype "passive"))
      (node (ref "CF17.2") (pin "39") (pinfunction "39_39") (pintype "passive"))
      (node (ref "CF17.2") (pin "40") (pinfunction "40_40") (pintype "passive"))
      (node (ref "CF18.2") (pin "39") (pinfunction "39_39") (pintype "passive"))
      (node (ref "CF18.2") (pin "40") (pinfunction "40_40") (pintype "passive"))
      (node (ref "CF19.2") (pin "39") (pinfunction "39_39") (pintype "passive"))
      (node (ref "CF19.2") (pin "40") (pinfunction "40_40") (pintype "passive"))
      (node (ref "CF2.2") (pin "39") (pinfunction "39_39") (pintype "passive"))
      (node (ref "CF2.2") (pin "40") (pinfunction "40_40") (pintype "passive"))
      (node (ref "CF2.3") (pin "39") (pinfunction "39_39") (pintype "passive"))
      (node (ref "CF2.3") (pin "40") (pinfunction "40_40") (pintype "passive"))
      (node (ref "CF2.4") (pin "39") (pinfunction "39_39") (pintype "passive"))
      (node (ref "CF2.4") (pin "40") (pinfunction "40_40") (pintype "passive"))
      (node (ref "CF3.2") (pin "39") (pinfunction "39_39") (pintype "passive"))
      (node (ref "CF3.2") (pin "40") (pinfunction "40_40") (pintype "passive"))
      (node (ref "CF4.2") (pin "39") (pinfunction "39_39") (pintype "passive"))
      (node (ref "CF4.2") (pin "40") (pinfunction "40_40") (pintype "passive"))
      (node (ref "CF5.2") (pin "39") (pinfunction "39_39") (pintype "passive"))
      (node (ref "CF5.2") (pin "40") (pinfunction "40_40") (pintype "passive"))
      (node (ref "CF6.2") (pin "39") (pinfunction "39_39") (pintype "passive"))
      (node (ref "CF6.2") (pin "40") (pinfunction "40_40") (pintype "passive"))
      (node (ref "CF7.2") (pin "39") (pinfunction "39_39") (pintype "passive"))
      (node (ref "CF7.2") (pin "40") (pinfunction "40_40") (pintype "passive"))
      (node (ref "CF8.2") (pin "39") (pinfunction "39_39") (pintype "passive"))
      (node (ref "CF8.2") (pin "40") (pinfunction "40_40") (pintype "passive"))
    )
  )
)
